# SCH_ECU_Standalone_V2_1.net
KiCad netlist of a schematic drawn in EasyEDA
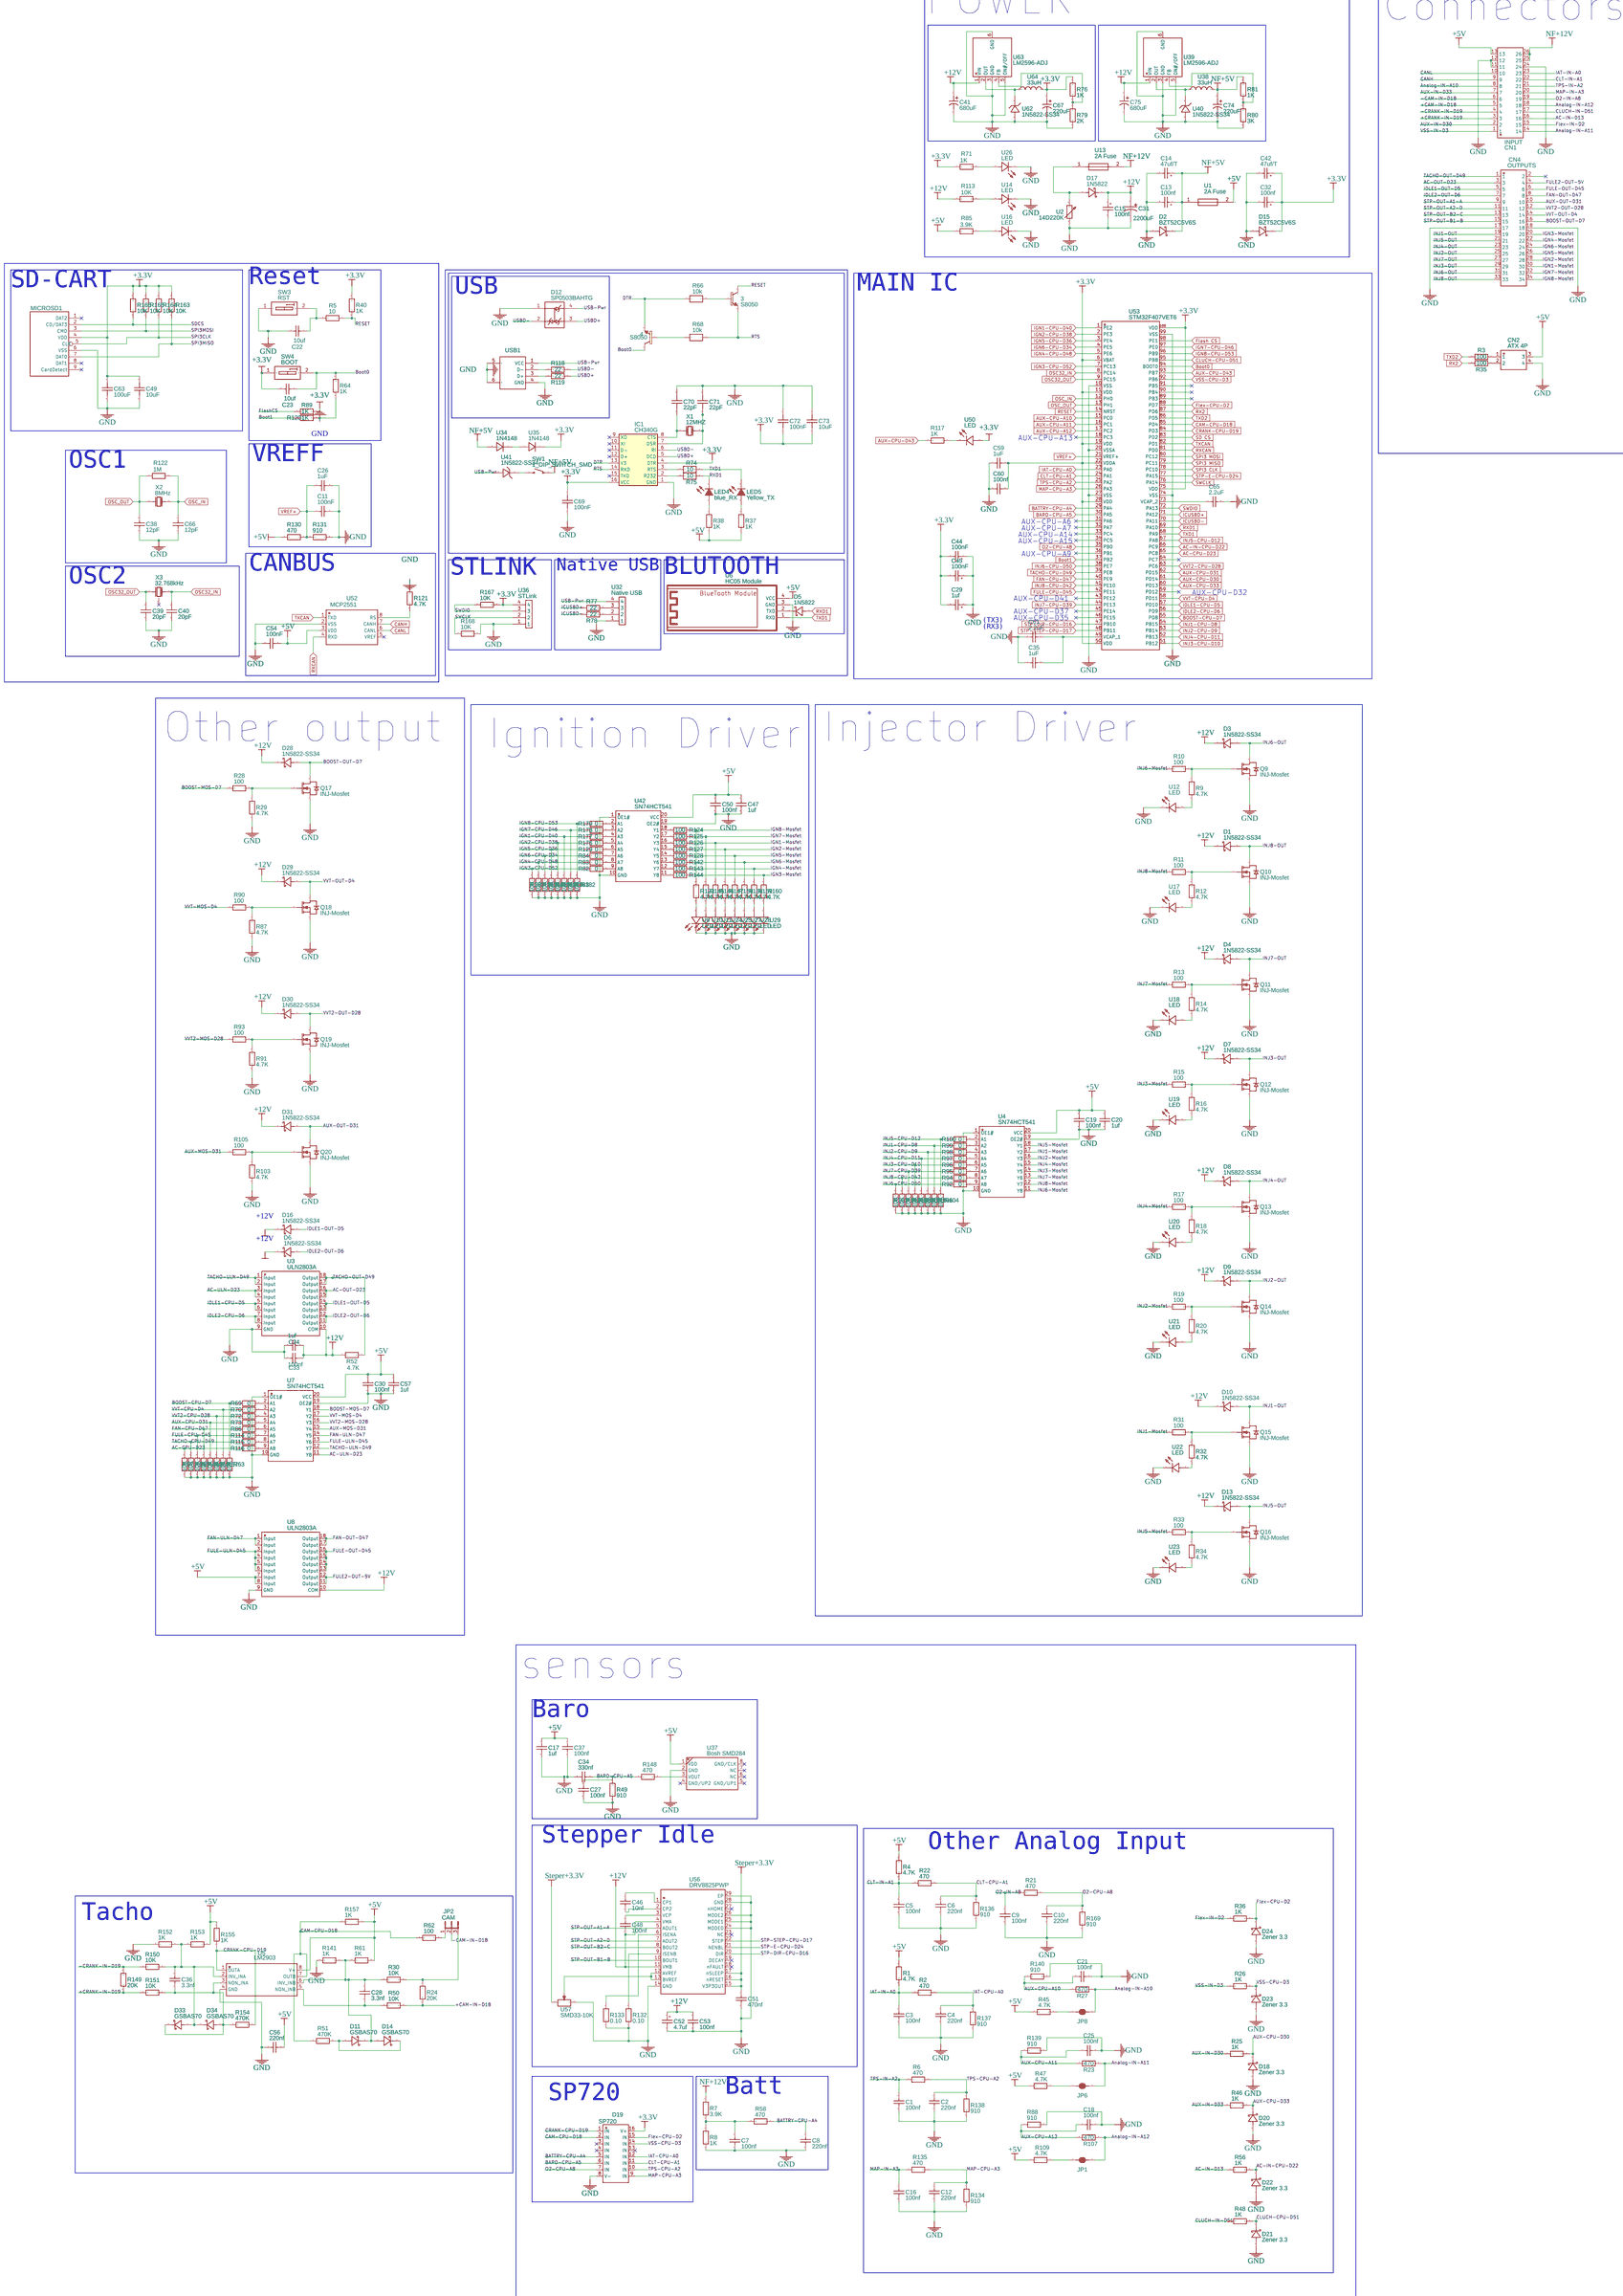
[diagram p0: schematic sheet]

(export (version "E")
  (design (tool "Eeschema 10.0.6"))
  (components
    (comp (ref "3") (value "S8050") (libsource (lib "") (part "J3Y_S8050_SMD_NPN_TRANSISTOR_1")))
    (comp (ref "4") (value "S8050") (libsource (lib "") (part "J3Y_S8050_SMD_NPN_TRANSISTOR")))
    (comp (ref "C1")
      (value "100nf")
      (fields (field (name "Manufacturer Part") "C0805X103K251T") (field (name "Manufacturer") "IHHEC(禾伸堂)"))
      (libsource (lib "") (part "C0805X103K251T"))
    )
    (comp (ref "C2")
      (value "220nf")
      (fields (field (name "Manufacturer Part") "C0805X103K251T") (field (name "Manufacturer") "IHHEC(禾伸堂)"))
      (libsource (lib "") (part "C0805X103K251T"))
    )
    (comp (ref "C3")
      (value "100nf")
      (fields (field (name "Manufacturer Part") "C0805X103K251T") (field (name "Manufacturer") "IHHEC(禾伸堂)"))
      (libsource (lib "") (part "C0805X103K251T"))
    )
    (comp (ref "C4")
      (value "220nf")
      (fields (field (name "Manufacturer Part") "C0805X103K251T") (field (name "Manufacturer") "IHHEC(禾伸堂)"))
      (libsource (lib "") (part "C0805X103K251T"))
    )
    (comp (ref "C5")
      (value "100nf")
      (fields (field (name "Manufacturer Part") "C0805X103K251T") (field (name "Manufacturer") "IHHEC(禾伸堂)"))
      (libsource (lib "") (part "C0805X103K251T"))
    )
    (comp (ref "C6")
      (value "220nf")
      (fields (field (name "Manufacturer Part") "C0805X103K251T") (field (name "Manufacturer") "IHHEC(禾伸堂)"))
      (libsource (lib "") (part "C0805X103K251T"))
    )
    (comp (ref "C7")
      (value "100nf")
      (fields (field (name "Manufacturer Part") "C0805X103K251T") (field (name "Manufacturer") "IHHEC(禾伸堂)"))
      (libsource (lib "") (part "C0805X103K251T"))
    )
    (comp (ref "C8")
      (value "220nf")
      (fields (field (name "Manufacturer Part") "C0805X103K251T") (field (name "Manufacturer") "IHHEC(禾伸堂)"))
      (libsource (lib "") (part "C0805X103K251T"))
    )
    (comp (ref "C9")
      (value "100nf")
      (fields (field (name "Manufacturer Part") "C0805X103K251T") (field (name "Manufacturer") "IHHEC(禾伸堂)"))
      (libsource (lib "") (part "C0805X103K251T"))
    )
    (comp (ref "C10")
      (value "220nf")
      (fields (field (name "Manufacturer Part") "C0805X103K251T") (field (name "Manufacturer") "IHHEC(禾伸堂)"))
      (libsource (lib "") (part "C0805X103K251T"))
    )
    (comp (ref "C11")
      (value "100nF")
      (fields (field (name "Manufacturer Part") "C0805X103K251T") (field (name "Manufacturer") "IHHEC(禾伸堂)"))
      (libsource (lib "") (part "C0805X103K251T_2"))
    )
    (comp (ref "C12")
      (value "220nf")
      (fields (field (name "Manufacturer Part") "C0805X103K251T") (field (name "Manufacturer") "IHHEC(禾伸堂)"))
      (libsource (lib "") (part "C0805X103K251T"))
    )
    (comp (ref "C13")
      (value "100nf")
      (fields (field (name "Manufacturer Part") "RMC25124.7K1%N") (field (name "Manufacturer") "Tyohm"))
      (libsource (lib "") (part "C SMD (2512 - 0805)"))
    )
    (comp (ref "C14")
      (value "47uf/T")
      (fields (field (name "Manufacturer Part") "RMC25124.7K1%N") (field (name "Manufacturer") "Tyohm"))
      (libsource (lib "") (part "C SMD (2512 - 0805)"))
    )
    (comp (ref "C15")
      (value "100nf")
      (fields (field (name "Manufacturer Part") "RMC25124.7K1%N") (field (name "Manufacturer") "Tyohm"))
      (libsource (lib "") (part "C SMD (2512 - 0805)_1"))
    )
    (comp (ref "C16")
      (value "100nf")
      (fields (field (name "Manufacturer Part") "C0805X103K251T") (field (name "Manufacturer") "IHHEC(禾伸堂)"))
      (libsource (lib "") (part "C0805X103K251T"))
    )
    (comp (ref "C17")
      (value "1uf")
      (fields (field (name "Manufacturer Part") "C0805X103K251T") (field (name "Manufacturer") "IHHEC(禾伸堂)"))
      (libsource (lib "") (part "C0805X103K251T"))
    )
    (comp (ref "C18")
      (value "100nf")
      (fields (field (name "Manufacturer Part") "C0805X103K251T") (field (name "Manufacturer") "IHHEC(禾伸堂)"))
      (libsource (lib "") (part "C0805X103K251T_2"))
    )
    (comp (ref "C19")
      (value "100nf")
      (fields (field (name "Manufacturer Part") "C0805X103K251T") (field (name "Manufacturer") "IHHEC(禾伸堂)"))
      (libsource (lib "") (part "C0805X103K251T"))
    )
    (comp (ref "C20")
      (value "1uf")
      (fields (field (name "Manufacturer Part") "C0805X103K251T") (field (name "Manufacturer") "IHHEC(禾伸堂)"))
      (libsource (lib "") (part "C0805X103K251T"))
    )
    (comp (ref "C21")
      (value "100nf")
      (fields (field (name "Manufacturer Part") "C0805X103K251T") (field (name "Manufacturer") "IHHEC(禾伸堂)"))
      (libsource (lib "") (part "C0805X103K251T_2"))
    )
    (comp (ref "C22")
      (value "10uf")
      (fields (field (name "Manufacturer Part") "C0805X103K251T") (field (name "Manufacturer") "IHHEC(禾伸堂)"))
      (libsource (lib "") (part "C0805X103K251T_1"))
    )
    (comp (ref "C23")
      (value "10uf")
      (fields (field (name "Manufacturer Part") "C0805X103K251T") (field (name "Manufacturer") "IHHEC(禾伸堂)"))
      (libsource (lib "") (part "C0805X103K251T_1"))
    )
    (comp (ref "C24")
      (value "1uf")
      (fields (field (name "Manufacturer Part") "C0805X103K251T") (field (name "Manufacturer") "IHHEC(禾伸堂)"))
      (libsource (lib "") (part "C0805X103K251T_1"))
    )
    (comp (ref "C25")
      (value "100nf")
      (fields (field (name "Manufacturer Part") "C0805X103K251T") (field (name "Manufacturer") "IHHEC(禾伸堂)"))
      (libsource (lib "") (part "C0805X103K251T_2"))
    )
    (comp (ref "C26")
      (value "1uF")
      (fields (field (name "Manufacturer Part") "C0805X103K251T") (field (name "Manufacturer") "IHHEC(禾伸堂)"))
      (libsource (lib "") (part "C0805X103K251T_2"))
    )
    (comp (ref "C27")
      (value "100nf")
      (fields (field (name "Manufacturer Part") "C0805X103K251T") (field (name "Manufacturer") "IHHEC(禾伸堂)"))
      (libsource (lib "") (part "C0805X103K251T"))
    )
    (comp (ref "C28")
      (value "3.3nf")
      (fields (field (name "Manufacturer Part") "C0805X103K251T") (field (name "Manufacturer") "IHHEC(禾伸堂)"))
      (libsource (lib "") (part "C0805X103K251T"))
    )
    (comp (ref "C29")
      (value "1uf")
      (fields (field (name "Manufacturer Part") "RMC25124.7K1%N") (field (name "Manufacturer") "Tyohm"))
      (libsource (lib "") (part "C SMD (2512 - 0805)"))
    )
    (comp (ref "C30")
      (value "100nf")
      (fields (field (name "Manufacturer Part") "C0805X103K251T") (field (name "Manufacturer") "IHHEC(禾伸堂)"))
      (libsource (lib "") (part "C0805X103K251T"))
    )
    (comp (ref "C31")
      (value "2200uF")
      (fields
        (field (name "Manufacturer Part") "25YXG2200MEFCG412.5X35")
        (field (name "Manufacturer") "rubycon(红宝石)")
      )
      (libsource (lib "") (part "25YXG2200MEFCG412.5X35"))
    )
    (comp (ref "C32")
      (value "100nf")
      (fields (field (name "Manufacturer Part") "RMC25124.7K1%N") (field (name "Manufacturer") "Tyohm"))
      (libsource (lib "") (part "C SMD (2512 - 0805)"))
    )
    (comp (ref "C33")
      (value "100nf")
      (fields (field (name "Manufacturer Part") "C0805X103K251T") (field (name "Manufacturer") "IHHEC(禾伸堂)"))
      (libsource (lib "") (part "C0805X103K251T_1"))
    )
    (comp (ref "C34")
      (value "330nf")
      (fields (field (name "Manufacturer Part") "C0805X103K251T") (field (name "Manufacturer") "IHHEC(禾伸堂)"))
      (libsource (lib "") (part "C0805X103K251T_1"))
    )
    (comp (ref "C35")
      (value "1uF")
      (fields (field (name "Manufacturer Part") "C0805X103K251T") (field (name "Manufacturer") "IHHEC(禾伸堂)"))
      (libsource (lib "") (part "C0805X103K251T_2"))
    )
    (comp (ref "C36")
      (value "3.3nf")
      (fields (field (name "Manufacturer Part") "C0805X103K251T") (field (name "Manufacturer") "IHHEC(禾伸堂)"))
      (libsource (lib "") (part "C0805X103K251T"))
    )
    (comp (ref "C37")
      (value "100nf")
      (fields (field (name "Manufacturer Part") "C0805X103K251T") (field (name "Manufacturer") "IHHEC(禾伸堂)"))
      (libsource (lib "") (part "C0805X103K251T"))
    )
    (comp (ref "C38")
      (value "12pF")
      (fields (field (name "Manufacturer Part") "C0805X103K251T") (field (name "Manufacturer") "IHHEC(禾伸堂)"))
      (libsource (lib "") (part "C0805X103K251T_3"))
    )
    (comp (ref "C39")
      (value "20pF")
      (fields (field (name "Manufacturer Part") "C0805X103K251T") (field (name "Manufacturer") "IHHEC(禾伸堂)"))
      (libsource (lib "") (part "C0805X103K251T_3"))
    )
    (comp (ref "C40")
      (value "20pF")
      (fields (field (name "Manufacturer Part") "C0805X103K251T") (field (name "Manufacturer") "IHHEC(禾伸堂)"))
      (libsource (lib "") (part "C0805X103K251T_3"))
    )
    (comp (ref "C41")
      (value "680uF")
      (fields
        (field (name "Manufacturer Part") "MVK16V100UF6.3*6")
        (field (name "Manufacturer") "SAMYOUNG(韩国三莹)")
      )
      (libsource (lib "") (part "CAP 6.3 &#126; 0.8 DIP 25v"))
    )
    (comp (ref "C42")
      (value "47uf/T")
      (fields (field (name "Manufacturer Part") "RMC25124.7K1%N") (field (name "Manufacturer") "Tyohm"))
      (libsource (lib "") (part "C SMD (2512 - 0805)"))
    )
    (comp (ref "C44")
      (value "100nF")
      (fields (field (name "Manufacturer Part") "RMC25124.7K1%N") (field (name "Manufacturer") "Tyohm"))
      (libsource (lib "") (part "C SMD (2512 - 0805)"))
    )
    (comp (ref "C45")
      (value "100nF")
      (fields (field (name "Manufacturer Part") "RMC25124.7K1%N") (field (name "Manufacturer") "Tyohm"))
      (libsource (lib "") (part "C SMD (2512 - 0805)"))
    )
    (comp (ref "C46")
      (value "10nf")
      (fields (field (name "Manufacturer Part") "C0805X103K251T") (field (name "Manufacturer") "IHHEC(禾伸堂)"))
      (libsource (lib "") (part "C0805X103K251T"))
    )
    (comp (ref "C47")
      (value "1uf")
      (fields (field (name "Manufacturer Part") "C0805X103K251T") (field (name "Manufacturer") "IHHEC(禾伸堂)"))
      (libsource (lib "") (part "C0805X103K251T"))
    )
    (comp (ref "C48")
      (value "100nf")
      (fields (field (name "Manufacturer Part") "C0805X103K251T") (field (name "Manufacturer") "IHHEC(禾伸堂)"))
      (libsource (lib "") (part "C0805X103K251T"))
    )
    (comp (ref "C49")
      (value "10uF")
      (fields
        (field (name "Manufacturer Part") "C0805C682KMRECAUTO7210")
        (field (name "Manufacturer") "KEMET(基美)")
      )
      (libsource (lib "") (part "C0805C682KMRECAUTO7210"))
    )
    (comp (ref "C50")
      (value "100nf")
      (fields (field (name "Manufacturer Part") "C0805X103K251T") (field (name "Manufacturer") "IHHEC(禾伸堂)"))
      (libsource (lib "") (part "C0805X103K251T"))
    )
    (comp (ref "C51")
      (value "470nf")
      (fields (field (name "Manufacturer Part") "C0805X103K251T") (field (name "Manufacturer") "IHHEC(禾伸堂)"))
      (libsource (lib "") (part "C0805X103K251T"))
    )
    (comp (ref "C52")
      (value "4.7uf")
      (fields (field (name "Manufacturer Part") "RMC25124.7K1%N") (field (name "Manufacturer") "Tyohm"))
      (libsource (lib "") (part "C SMD (2512 - 0805)_1"))
    )
    (comp (ref "C53")
      (value "100nf")
      (fields (field (name "Manufacturer Part") "C0805X103K251T") (field (name "Manufacturer") "IHHEC(禾伸堂)"))
      (libsource (lib "") (part "C0805X103K251T"))
    )
    (comp (ref "C54")
      (value "100nF")
      (fields (field (name "Manufacturer Part") "C0805X103K251T") (field (name "Manufacturer") "IHHEC(禾伸堂)"))
      (libsource (lib "") (part "C0805X103K251T_1"))
    )
    (comp (ref "C56")
      (value "220nf")
      (fields (field (name "Manufacturer Part") "C0805X103K251T") (field (name "Manufacturer") "IHHEC(禾伸堂)"))
      (libsource (lib "") (part "C0805X103K251T_2"))
    )
    (comp (ref "C57")
      (value "1uf")
      (fields (field (name "Manufacturer Part") "C0805X103K251T") (field (name "Manufacturer") "IHHEC(禾伸堂)"))
      (libsource (lib "") (part "C0805X103K251T"))
    )
    (comp (ref "C59")
      (value "1uF")
      (fields (field (name "Manufacturer Part") "C0805X103K251T") (field (name "Manufacturer") "IHHEC(禾伸堂)"))
      (libsource (lib "") (part "C0805X103K251T_2"))
    )
    (comp (ref "C60")
      (value "100nf")
      (fields (field (name "Manufacturer Part") "C0805X103K251T") (field (name "Manufacturer") "IHHEC(禾伸堂)"))
      (libsource (lib "") (part "C0805X103K251T_2"))
    )
    (comp (ref "C61")
      (value "2.2uF")
      (fields (field (name "Manufacturer Part") "C0805X103K251T") (field (name "Manufacturer") "IHHEC(禾伸堂)"))
      (libsource (lib "") (part "C0805X103K251T_2"))
    )
    (comp (ref "C63")
      (value "100uF")
      (fields
        (field (name "Manufacturer Part") "C0805C682KMRECAUTO7210")
        (field (name "Manufacturer") "KEMET(基美)")
      )
      (libsource (lib "") (part "C0805C682KMRECAUTO7210"))
    )
    (comp (ref "C65")
      (value "2.2uF")
      (fields (field (name "Manufacturer Part") "C0805X103K251T") (field (name "Manufacturer") "IHHEC(禾伸堂)"))
      (libsource (lib "") (part "C0805X103K251T_2"))
    )
    (comp (ref "C66")
      (value "12pF")
      (fields (field (name "Manufacturer Part") "C0805X103K251T") (field (name "Manufacturer") "IHHEC(禾伸堂)"))
      (libsource (lib "") (part "C0805X103K251T_3"))
    )
    (comp (ref "C67")
      (value "220uF")
      (fields
        (field (name "Manufacturer Part") "MVK16V100UF6.3*6")
        (field (name "Manufacturer") "SAMYOUNG(韩国三莹)")
      )
      (libsource (lib "") (part "CAP 6.3 &#126; 0.8 DIP 25v"))
    )
    (comp (ref "C69")
      (value "100nF")
      (fields
        (field (name "Manufacturer Part") "C0805C682KMRECAUTO7210")
        (field (name "Manufacturer") "KEMET(基美)")
      )
      (libsource (lib "") (part "C0805C682KMRECAUTO7210_1"))
    )
    (comp (ref "C70")
      (value "22pF")
      (fields
        (field (name "Manufacturer Part") "C0805C682KMRECAUTO7210")
        (field (name "Manufacturer") "KEMET(基美)")
      )
      (libsource (lib "") (part "C0805C682KMRECAUTO7210_1"))
    )
    (comp (ref "C71")
      (value "22pF")
      (fields
        (field (name "Manufacturer Part") "C0805C682KMRECAUTO7210")
        (field (name "Manufacturer") "KEMET(基美)")
      )
      (libsource (lib "") (part "C0805C682KMRECAUTO7210_1"))
    )
    (comp (ref "C72")
      (value "100nF")
      (fields
        (field (name "Manufacturer Part") "C0805C682KMRECAUTO7210")
        (field (name "Manufacturer") "KEMET(基美)")
      )
      (libsource (lib "") (part "C0805C682KMRECAUTO7210_1"))
    )
    (comp (ref "C73")
      (value "10uF")
      (fields
        (field (name "Manufacturer Part") "C0805C682KMRECAUTO7210")
        (field (name "Manufacturer") "KEMET(基美)")
      )
      (libsource (lib "") (part "C0805C682KMRECAUTO7210_1"))
    )
    (comp (ref "C74")
      (value "220uF")
      (fields
        (field (name "Manufacturer Part") "MVK16V100UF6.3*6")
        (field (name "Manufacturer") "SAMYOUNG(韩国三莹)")
      )
      (libsource (lib "") (part "CAP 6.3 &#126; 0.8 DIP 25v"))
    )
    (comp (ref "C75")
      (value "680uF")
      (fields
        (field (name "Manufacturer Part") "MVK16V100UF6.3*6")
        (field (name "Manufacturer") "SAMYOUNG(韩国三莹)")
      )
      (libsource (lib "") (part "CAP 6.3 &#126; 0.8 DIP 25v"))
    )
    (comp (ref "CN1")
      (value "INPUT")
      (fields (field (name "Manufacturer Part") "MX23A26NF1") (field (name "Manufacturer") "JAE(日本航空电子)"))
      (libsource (lib "") (part "MX23A26NF1"))
    )
    (comp (ref "CN2")
      (value "ATX 4P")
      (fields (field (name "Manufacturer Part") "C4201WR-2x2P") (field (name "Manufacturer") "CJT(长江连接器)"))
      (libsource (lib "") (part "C4201WR-2X2P"))
    )
    (comp (ref "CN4")
      (value "OUTPUTS")
      (fields (field (name "Manufacturer Part") "MX23A34NF1") (field (name "Manufacturer") "JAE(日本航空电子)"))
      (libsource (lib "") (part "MX23A34NF1"))
    )
    (comp (ref "D1")
      (value "1N5822-SS34")
      (fields (field (name "Manufacturer Part") "1N5819HW") (field (name "Manufacturer") "TECH PUBLIC(台舟)"))
      (libsource (lib "") (part "DIOD SOD-123_2"))
    )
    (comp (ref "D2")
      (value "BZT52C5V6S")
      (fields (field (name "Manufacturer Part") "1N5819HW") (field (name "Manufacturer") "TECH PUBLIC(台舟)"))
      (libsource (lib "") (part "DIOD SOD-123_1"))
    )
    (comp (ref "D3")
      (value "1N5822-SS34")
      (fields (field (name "Manufacturer Part") "1N5819HW") (field (name "Manufacturer") "TECH PUBLIC(台舟)"))
      (libsource (lib "") (part "DIOD SOD-123_2"))
    )
    (comp (ref "D4")
      (value "1N5822-SS34")
      (fields (field (name "Manufacturer Part") "1N5819HW") (field (name "Manufacturer") "TECH PUBLIC(台舟)"))
      (libsource (lib "") (part "DIOD SOD-123_2"))
    )
    (comp (ref "D5")
      (value "1N5822")
      (fields (field (name "Manufacturer Part") "1N5819HW") (field (name "Manufacturer") "TECH PUBLIC(台舟)"))
      (libsource (lib "") (part "DIOD SOD-123_2"))
    )
    (comp (ref "D6")
      (value "1N5822-SS34")
      (fields (field (name "Manufacturer Part") "1N5819HW") (field (name "Manufacturer") "TECH PUBLIC(台舟)"))
      (libsource (lib "") (part "DIOD SOD-123_2"))
    )
    (comp (ref "D7")
      (value "1N5822-SS34")
      (fields (field (name "Manufacturer Part") "1N5819HW") (field (name "Manufacturer") "TECH PUBLIC(台舟)"))
      (libsource (lib "") (part "DIOD SOD-123_2"))
    )
    (comp (ref "D8")
      (value "1N5822-SS34")
      (fields (field (name "Manufacturer Part") "1N5819HW") (field (name "Manufacturer") "TECH PUBLIC(台舟)"))
      (libsource (lib "") (part "DIOD SOD-123_2"))
    )
    (comp (ref "D9")
      (value "1N5822-SS34")
      (fields (field (name "Manufacturer Part") "1N5819HW") (field (name "Manufacturer") "TECH PUBLIC(台舟)"))
      (libsource (lib "") (part "DIOD SOD-123_2"))
    )
    (comp (ref "D10")
      (value "1N5822-SS34")
      (fields (field (name "Manufacturer Part") "1N5819HW") (field (name "Manufacturer") "TECH PUBLIC(台舟)"))
      (libsource (lib "") (part "DIOD SOD-123_2"))
    )
    (comp (ref "D11")
      (value "GSBAS70")
      (fields (field (name "Manufacturer Part") "GSBAS70WS") (field (name "Manufacturer") "GOOD-ARK(固锝)"))
      (libsource (lib "") (part "GSBAS70WS_1"))
    )
    (comp (ref "D12")
      (value "SP0503BAHTG")
      (fields (field (name "Manufacturer") "Littelfuse"))
      (libsource (lib "") (part "SP0503BAHTG"))
    )
    (comp (ref "D13")
      (value "1N5822-SS34")
      (fields (field (name "Manufacturer Part") "1N5819HW") (field (name "Manufacturer") "TECH PUBLIC(台舟)"))
      (libsource (lib "") (part "DIOD SOD-123_2"))
    )
    (comp (ref "D14")
      (value "GSBAS70")
      (fields (field (name "Manufacturer Part") "GSBAS70WS") (field (name "Manufacturer") "GOOD-ARK(固锝)"))
      (libsource (lib "") (part "GSBAS70WS_1"))
    )
    (comp (ref "D15")
      (value "BZT52C5V6S")
      (fields (field (name "Manufacturer Part") "1N5819HW") (field (name "Manufacturer") "TECH PUBLIC(台舟)"))
      (libsource (lib "") (part "DIOD SOD-123_1"))
    )
    (comp (ref "D16")
      (value "1N5822-SS34")
      (fields (field (name "Manufacturer Part") "1N5819HW") (field (name "Manufacturer") "TECH PUBLIC(台舟)"))
      (libsource (lib "") (part "DIOD SOD-123_2"))
    )
    (comp (ref "D17")
      (value "1N5822")
      (fields (field (name "Manufacturer Part") "1N5819HW") (field (name "Manufacturer") "TECH PUBLIC(台舟)"))
      (libsource (lib "") (part "DIOD SOD-123_1"))
    )
    (comp (ref "D18")
      (value "Zener 3.3")
      (fields (field (name "Manufacturer Part") "1N5819HW") (field (name "Manufacturer") "TECH PUBLIC(台舟)"))
      (libsource (lib "") (part "DIOD SOD-123"))
    )
    (comp (ref "D19")
      (value "SP720")
      (fields (field (name "Manufacturer Part") "SP720ABTG") (field (name "Manufacturer") "Littelfuse"))
      (libsource (lib "") (part "SP720ABTG"))
    )
    (comp (ref "D20")
      (value "Zener 3.3")
      (fields (field (name "Manufacturer Part") "1N5819HW") (field (name "Manufacturer") "TECH PUBLIC(台舟)"))
      (libsource (lib "") (part "DIOD SOD-123"))
    )
    (comp (ref "D21")
      (value "Zener 3.3")
      (fields (field (name "Manufacturer Part") "1N5819HW") (field (name "Manufacturer") "TECH PUBLIC(台舟)"))
      (libsource (lib "") (part "DIOD SOD-123"))
    )
    (comp (ref "D22")
      (value "Zener 3.3")
      (fields (field (name "Manufacturer Part") "1N5819HW") (field (name "Manufacturer") "TECH PUBLIC(台舟)"))
      (libsource (lib "") (part "DIOD SOD-123"))
    )
    (comp (ref "D23")
      (value "Zener 3.3")
      (fields (field (name "Manufacturer Part") "1N5819HW") (field (name "Manufacturer") "TECH PUBLIC(台舟)"))
      (libsource (lib "") (part "DIOD SOD-123"))
    )
    (comp (ref "D24")
      (value "Zener 3.3")
      (fields (field (name "Manufacturer Part") "1N5819HW") (field (name "Manufacturer") "TECH PUBLIC(台舟)"))
      (libsource (lib "") (part "DIOD SOD-123"))
    )
    (comp (ref "D28")
      (value "1N5822-SS34")
      (fields (field (name "Manufacturer Part") "1N5819HW") (field (name "Manufacturer") "TECH PUBLIC(台舟)"))
      (libsource (lib "") (part "DIOD SOD-123_2"))
    )
    (comp (ref "D29")
      (value "1N5822-SS34")
      (fields (field (name "Manufacturer Part") "1N5819HW") (field (name "Manufacturer") "TECH PUBLIC(台舟)"))
      (libsource (lib "") (part "DIOD SOD-123_2"))
    )
    (comp (ref "D30")
      (value "1N5822-SS34")
      (fields (field (name "Manufacturer Part") "1N5819HW") (field (name "Manufacturer") "TECH PUBLIC(台舟)"))
      (libsource (lib "") (part "DIOD SOD-123_2"))
    )
    (comp (ref "D31")
      (value "1N5822-SS34")
      (fields (field (name "Manufacturer Part") "1N5819HW") (field (name "Manufacturer") "TECH PUBLIC(台舟)"))
      (libsource (lib "") (part "DIOD SOD-123_2"))
    )
    (comp (ref "D33")
      (value "GSBAS70")
      (fields (field (name "Manufacturer Part") "GSBAS70WS") (field (name "Manufacturer") "GOOD-ARK(固锝)"))
      (libsource (lib "") (part "GSBAS70WS"))
    )
    (comp (ref "D34")
      (value "GSBAS70")
      (fields (field (name "Manufacturer Part") "GSBAS70WS") (field (name "Manufacturer") "GOOD-ARK(固锝)"))
      (libsource (lib "") (part "GSBAS70WS"))
    )
    (comp (ref "IC1")
      (value "CH340G")
      (fields (field (name "Manufacturer") "WCH"))
      (libsource (lib "") (part "Unknown_885_-515"))
    )
    (comp (ref "JP1") (value "Pull-Up") (libsource (lib "") (part "SOLDERJUMPER-OLDNO")))
    (comp (ref "JP2") (value "CAM") (libsource (lib "") (part "JUMPER 3X1 (PIN= 2.54) SMD")))
    (comp (ref "JP6") (value "Pull-Up") (libsource (lib "") (part "SOLDERJUMPER-OLDNO")))
    (comp (ref "JP8") (value "Pull-Up") (libsource (lib "") (part "SOLDERJUMPER-OLDNO")))
    (comp (ref "LED4")
      (value "blue_RX")
      (fields (field (name "Manufacturer Part") "0805-1-YGC/FID"))
      (libsource (lib "") (part "0805-1-YGC/FID"))
    )
    (comp (ref "LED5")
      (value "Yellow_TX")
      (fields (field (name "Manufacturer Part") "0805-1-YGC/FID"))
      (libsource (lib "") (part "0805-1-YGC/FID"))
    )
    (comp (ref "MICROSD1")
      (value "MicroSD_Slot")
      (fields (field (name "Manufacturer Part") "MicroSD Slot"))
      (libsource (lib "") (part "Unknown_-5_-740"))
    )
    (comp (ref "Q9")
      (value "INJ-Mosfet")
      (fields
        (field (name "Manufacturer Part") "PHD45N03LTA-VB")
        (field (name "Manufacturer") "VBsemi(微碧半导体)")
      )
      (libsource (lib "") (part "PHD45N03LTA"))
    )
    (comp (ref "Q10")
      (value "INJ-Mosfet")
      (fields
        (field (name "Manufacturer Part") "PHD45N03LTA-VB")
        (field (name "Manufacturer") "VBsemi(微碧半导体)")
      )
      (libsource (lib "") (part "PHD45N03LTA"))
    )
    (comp (ref "Q11")
      (value "INJ-Mosfet")
      (fields
        (field (name "Manufacturer Part") "PHD45N03LTA-VB")
        (field (name "Manufacturer") "VBsemi(微碧半导体)")
      )
      (libsource (lib "") (part "PHD45N03LTA"))
    )
    (comp (ref "Q12")
      (value "INJ-Mosfet")
      (fields
        (field (name "Manufacturer Part") "PHD45N03LTA-VB")
        (field (name "Manufacturer") "VBsemi(微碧半导体)")
      )
      (libsource (lib "") (part "PHD45N03LTA"))
    )
    (comp (ref "Q13")
      (value "INJ-Mosfet")
      (fields
        (field (name "Manufacturer Part") "PHD45N03LTA-VB")
        (field (name "Manufacturer") "VBsemi(微碧半导体)")
      )
      (libsource (lib "") (part "PHD45N03LTA"))
    )
    (comp (ref "Q14")
      (value "INJ-Mosfet")
      (fields
        (field (name "Manufacturer Part") "PHD45N03LTA-VB")
        (field (name "Manufacturer") "VBsemi(微碧半导体)")
      )
      (libsource (lib "") (part "PHD45N03LTA"))
    )
    (comp (ref "Q15")
      (value "INJ-Mosfet")
      (fields
        (field (name "Manufacturer Part") "PHD45N03LTA-VB")
        (field (name "Manufacturer") "VBsemi(微碧半导体)")
      )
      (libsource (lib "") (part "PHD45N03LTA"))
    )
    (comp (ref "Q16")
      (value "INJ-Mosfet")
      (fields
        (field (name "Manufacturer Part") "PHD45N03LTA-VB")
        (field (name "Manufacturer") "VBsemi(微碧半导体)")
      )
      (libsource (lib "") (part "PHD45N03LTA"))
    )
    (comp (ref "Q17")
      (value "INJ-Mosfet")
      (fields
        (field (name "Manufacturer Part") "PHD45N03LTA-VB")
        (field (name "Manufacturer") "VBsemi(微碧半导体)")
      )
      (libsource (lib "") (part "PHD45N03LTA"))
    )
    (comp (ref "Q18")
      (value "INJ-Mosfet")
      (fields
        (field (name "Manufacturer Part") "PHD45N03LTA-VB")
        (field (name "Manufacturer") "VBsemi(微碧半导体)")
      )
      (libsource (lib "") (part "PHD45N03LTA"))
    )
    (comp (ref "Q19")
      (value "INJ-Mosfet")
      (fields
        (field (name "Manufacturer Part") "PHD45N03LTA-VB")
        (field (name "Manufacturer") "VBsemi(微碧半导体)")
      )
      (libsource (lib "") (part "PHD45N03LTA"))
    )
    (comp (ref "Q20")
      (value "INJ-Mosfet")
      (fields
        (field (name "Manufacturer Part") "PHD45N03LTA-VB")
        (field (name "Manufacturer") "VBsemi(微碧半导体)")
      )
      (libsource (lib "") (part "PHD45N03LTA"))
    )
    (comp (ref "R1")
      (value "4.7K")
      (fields
        (field (name "Manufacturer Part") "AECR0805F9K10K9")
        (field (name "Manufacturer") "ResistorToday")
      )
      (libsource (lib "") (part "AECR0805F_3"))
    )
    (comp (ref "R2")
      (value "470")
      (fields
        (field (name "Manufacturer Part") "AECR0805F9K10K9")
        (field (name "Manufacturer") "ResistorToday")
      )
      (libsource (lib "") (part "AECR0805F"))
    )
    (comp (ref "R3")
      (value "100")
      (fields
        (field (name "Manufacturer Part") "AECR0805F9K10K9")
        (field (name "Manufacturer") "ResistorToday")
      )
      (libsource (lib "") (part "AECR0805F"))
    )
    (comp (ref "R4")
      (value "4.7K")
      (fields
        (field (name "Manufacturer Part") "AECR0805F9K10K9")
        (field (name "Manufacturer") "ResistorToday")
      )
      (libsource (lib "") (part "AECR0805F_3"))
    )
    (comp (ref "R5")
      (value "10")
      (fields
        (field (name "Manufacturer Part") "AECR0805F9K10K9")
        (field (name "Manufacturer") "ResistorToday")
      )
      (libsource (lib "") (part "AECR0805F"))
    )
    (comp (ref "R6")
      (value "470")
      (fields
        (field (name "Manufacturer Part") "AECR0805F9K10K9")
        (field (name "Manufacturer") "ResistorToday")
      )
      (libsource (lib "") (part "AECR0805F"))
    )
    (comp (ref "R7")
      (value "3.9K")
      (fields
        (field (name "Manufacturer Part") "AECR0805F9K10K9")
        (field (name "Manufacturer") "ResistorToday")
      )
      (libsource (lib "") (part "AECR0805F_1"))
    )
    (comp (ref "R8")
      (value "1K")
      (fields
        (field (name "Manufacturer Part") "AECR0805F9K10K9")
        (field (name "Manufacturer") "ResistorToday")
      )
      (libsource (lib "") (part "AECR0805F_1"))
    )
    (comp (ref "R9")
      (value "4.7K")
      (fields
        (field (name "Manufacturer Part") "AECR0805F9K10K9")
        (field (name "Manufacturer") "ResistorToday")
      )
      (libsource (lib "") (part "AECR0805F_1"))
    )
    (comp (ref "R10")
      (value "100")
      (fields
        (field (name "Manufacturer Part") "AECR0805F9K10K9")
        (field (name "Manufacturer") "ResistorToday")
      )
      (libsource (lib "") (part "AECR0805F"))
    )
    (comp (ref "R11")
      (value "100")
      (fields
        (field (name "Manufacturer Part") "AECR0805F9K10K9")
        (field (name "Manufacturer") "ResistorToday")
      )
      (libsource (lib "") (part "AECR0805F"))
    )
    (comp (ref "R12")
      (value "4.7K")
      (fields
        (field (name "Manufacturer Part") "AECR0805F9K10K9")
        (field (name "Manufacturer") "ResistorToday")
      )
      (libsource (lib "") (part "AECR0805F_1"))
    )
    (comp (ref "R13")
      (value "100")
      (fields
        (field (name "Manufacturer Part") "AECR0805F9K10K9")
        (field (name "Manufacturer") "ResistorToday")
      )
      (libsource (lib "") (part "AECR0805F"))
    )
    (comp (ref "R14")
      (value "4.7K")
      (fields
        (field (name "Manufacturer Part") "AECR0805F9K10K9")
        (field (name "Manufacturer") "ResistorToday")
      )
      (libsource (lib "") (part "AECR0805F_1"))
    )
    (comp (ref "R15")
      (value "100")
      (fields
        (field (name "Manufacturer Part") "AECR0805F9K10K9")
        (field (name "Manufacturer") "ResistorToday")
      )
      (libsource (lib "") (part "AECR0805F"))
    )
    (comp (ref "R16")
      (value "4.7K")
      (fields
        (field (name "Manufacturer Part") "AECR0805F9K10K9")
        (field (name "Manufacturer") "ResistorToday")
      )
      (libsource (lib "") (part "AECR0805F_1"))
    )
    (comp (ref "R17")
      (value "100")
      (fields
        (field (name "Manufacturer Part") "AECR0805F9K10K9")
        (field (name "Manufacturer") "ResistorToday")
      )
      (libsource (lib "") (part "AECR0805F"))
    )
    (comp (ref "R18")
      (value "4.7K")
      (fields
        (field (name "Manufacturer Part") "AECR0805F9K10K9")
        (field (name "Manufacturer") "ResistorToday")
      )
      (libsource (lib "") (part "AECR0805F_1"))
    )
    (comp (ref "R19")
      (value "100")
      (fields
        (field (name "Manufacturer Part") "AECR0805F9K10K9")
        (field (name "Manufacturer") "ResistorToday")
      )
      (libsource (lib "") (part "AECR0805F"))
    )
    (comp (ref "R20")
      (value "4.7K")
      (fields
        (field (name "Manufacturer Part") "AECR0805F9K10K9")
        (field (name "Manufacturer") "ResistorToday")
      )
      (libsource (lib "") (part "AECR0805F_1"))
    )
    (comp (ref "R21")
      (value "470")
      (fields
        (field (name "Manufacturer Part") "AECR0805F9K10K9")
        (field (name "Manufacturer") "ResistorToday")
      )
      (libsource (lib "") (part "AECR0805F"))
    )
    (comp (ref "R22")
      (value "470")
      (fields
        (field (name "Manufacturer Part") "AECR0805F9K10K9")
        (field (name "Manufacturer") "ResistorToday")
      )
      (libsource (lib "") (part "AECR0805F"))
    )
    (comp (ref "R23")
      (value "470")
      (fields
        (field (name "Manufacturer Part") "AECR0805F9K10K9")
        (field (name "Manufacturer") "ResistorToday")
      )
      (libsource (lib "") (part "AECR0805F"))
    )
    (comp (ref "R24")
      (value "20K")
      (fields
        (field (name "Manufacturer Part") "AECR0805F9K10K9")
        (field (name "Manufacturer") "ResistorToday")
      )
      (libsource (lib "") (part "AECR0805F_3"))
    )
    (comp (ref "R25")
      (value "1K")
      (fields
        (field (name "Manufacturer Part") "AECR0805F9K10K9")
        (field (name "Manufacturer") "ResistorToday")
      )
      (libsource (lib "") (part "AECR0805F_2"))
    )
    (comp (ref "R26")
      (value "1K")
      (fields
        (field (name "Manufacturer Part") "AECR0805F9K10K9")
        (field (name "Manufacturer") "ResistorToday")
      )
      (libsource (lib "") (part "AECR0805F_2"))
    )
    (comp (ref "R27")
      (value "470")
      (fields
        (field (name "Manufacturer Part") "AECR0805F9K10K9")
        (field (name "Manufacturer") "ResistorToday")
      )
      (libsource (lib "") (part "AECR0805F"))
    )
    (comp (ref "R28")
      (value "100")
      (fields
        (field (name "Manufacturer Part") "AECR0805F9K10K9")
        (field (name "Manufacturer") "ResistorToday")
      )
      (libsource (lib "") (part "AECR0805F"))
    )
    (comp (ref "R29")
      (value "4.7K")
      (fields
        (field (name "Manufacturer Part") "AECR0805F9K10K9")
        (field (name "Manufacturer") "ResistorToday")
      )
      (libsource (lib "") (part "AECR0805F_3"))
    )
    (comp (ref "R30")
      (value "10K")
      (fields
        (field (name "Manufacturer Part") "AECR0805F9K10K9")
        (field (name "Manufacturer") "ResistorToday")
      )
      (libsource (lib "") (part "AECR0805F_2"))
    )
    (comp (ref "R31")
      (value "100")
      (fields
        (field (name "Manufacturer Part") "AECR0805F9K10K9")
        (field (name "Manufacturer") "ResistorToday")
      )
      (libsource (lib "") (part "AECR0805F"))
    )
    (comp (ref "R32")
      (value "4.7K")
      (fields
        (field (name "Manufacturer Part") "AECR0805F9K10K9")
        (field (name "Manufacturer") "ResistorToday")
      )
      (libsource (lib "") (part "AECR0805F_1"))
    )
    (comp (ref "R33")
      (value "100")
      (fields
        (field (name "Manufacturer Part") "AECR0805F9K10K9")
        (field (name "Manufacturer") "ResistorToday")
      )
      (libsource (lib "") (part "AECR0805F"))
    )
    (comp (ref "R34")
      (value "4.7K")
      (fields
        (field (name "Manufacturer Part") "AECR0805F9K10K9")
        (field (name "Manufacturer") "ResistorToday")
      )
      (libsource (lib "") (part "AECR0805F_1"))
    )
    (comp (ref "R35")
      (value "100")
      (fields
        (field (name "Manufacturer Part") "AECR0805F9K10K9")
        (field (name "Manufacturer") "ResistorToday")
      )
      (libsource (lib "") (part "AECR0805F"))
    )
    (comp (ref "R36")
      (value "1K")
      (fields
        (field (name "Manufacturer Part") "AECR0805F9K10K9")
        (field (name "Manufacturer") "ResistorToday")
      )
      (libsource (lib "") (part "AECR0805F_2"))
    )
    (comp (ref "R37")
      (value "1K")
      (fields (field (name "Manufacturer Part") "RC0805FR-072K74L") (field (name "Manufacturer") "YAGEO"))
      (libsource (lib "") (part "RC0805FR-072K74L"))
    )
    (comp (ref "R38")
      (value "1K")
      (fields (field (name "Manufacturer Part") "RC0805FR-072K74L") (field (name "Manufacturer") "YAGEO"))
      (libsource (lib "") (part "RC0805FR-072K74L"))
    )
    (comp (ref "R40")
      (value "1K")
      (fields
        (field (name "Manufacturer Part") "AECR0805F9K10K9")
        (field (name "Manufacturer") "ResistorToday")
      )
      (libsource (lib "") (part "AECR0805F_1"))
    )
    (comp (ref "R41")
      (value "10K")
      (fields
        (field (name "Manufacturer Part") "AECR0805F9K10K9")
        (field (name "Manufacturer") "ResistorToday")
      )
      (libsource (lib "") (part "AECR0805F_1"))
    )
    (comp (ref "R42")
      (value "10K")
      (fields
        (field (name "Manufacturer Part") "AECR0805F9K10K9")
        (field (name "Manufacturer") "ResistorToday")
      )
      (libsource (lib "") (part "AECR0805F_1"))
    )
    (comp (ref "R43")
      (value "10K")
      (fields
        (field (name "Manufacturer Part") "AECR0805F9K10K9")
        (field (name "Manufacturer") "ResistorToday")
      )
      (libsource (lib "") (part "AECR0805F_1"))
    )
    (comp (ref "R45")
      (value "4.7K")
      (fields
        (field (name "Manufacturer Part") "AECR0805F9K10K9")
        (field (name "Manufacturer") "ResistorToday")
      )
      (libsource (lib "") (part "AECR0805F_2"))
    )
    (comp (ref "R46")
      (value "1K")
      (fields
        (field (name "Manufacturer Part") "AECR0805F9K10K9")
        (field (name "Manufacturer") "ResistorToday")
      )
      (libsource (lib "") (part "AECR0805F_2"))
    )
    (comp (ref "R47")
      (value "4.7K")
      (fields
        (field (name "Manufacturer Part") "AECR0805F9K10K9")
        (field (name "Manufacturer") "ResistorToday")
      )
      (libsource (lib "") (part "AECR0805F_2"))
    )
    (comp (ref "R48")
      (value "1K")
      (fields
        (field (name "Manufacturer Part") "AECR0805F9K10K9")
        (field (name "Manufacturer") "ResistorToday")
      )
      (libsource (lib "") (part "AECR0805F_2"))
    )
    (comp (ref "R49")
      (value "910")
      (fields
        (field (name "Manufacturer Part") "AECR0805F9K10K9")
        (field (name "Manufacturer") "ResistorToday")
      )
      (libsource (lib "") (part "AECR0805F_3"))
    )
    (comp (ref "R50")
      (value "10K")
      (fields
        (field (name "Manufacturer Part") "AECR0805F9K10K9")
        (field (name "Manufacturer") "ResistorToday")
      )
      (libsource (lib "") (part "AECR0805F_2"))
    )
    (comp (ref "R51")
      (value "470K")
      (fields
        (field (name "Manufacturer Part") "AECR0805F9K10K9")
        (field (name "Manufacturer") "ResistorToday")
      )
      (libsource (lib "") (part "AECR0805F_2"))
    )
    (comp (ref "R52")
      (value "4.7K")
      (fields
        (field (name "Manufacturer Part") "AECR0805F9K10K9")
        (field (name "Manufacturer") "ResistorToday")
      )
      (libsource (lib "") (part "AECR0805F_2"))
    )
    (comp (ref "R54")
      (value "10K")
      (fields
        (field (name "Manufacturer Part") "AECR0805F9K10K9")
        (field (name "Manufacturer") "ResistorToday")
      )
      (libsource (lib "") (part "AECR0805F_1"))
    )
    (comp (ref "R56")
      (value "1K")
      (fields
        (field (name "Manufacturer Part") "AECR0805F9K10K9")
        (field (name "Manufacturer") "ResistorToday")
      )
      (libsource (lib "") (part "AECR0805F_2"))
    )
    (comp (ref "R57")
      (value "10K")
      (fields
        (field (name "Manufacturer Part") "AECR0805F9K10K9")
        (field (name "Manufacturer") "ResistorToday")
      )
      (libsource (lib "") (part "AECR0805F_1"))
    )
    (comp (ref "R58")
      (value "470")
      (fields
        (field (name "Manufacturer Part") "AECR0805F9K10K9")
        (field (name "Manufacturer") "ResistorToday")
      )
      (libsource (lib "") (part "AECR0805F"))
    )
    (comp (ref "R61")
      (value "1K")
      (fields
        (field (name "Manufacturer Part") "AECR0805F9K10K9")
        (field (name "Manufacturer") "ResistorToday")
      )
      (libsource (lib "") (part "AECR0805F"))
    )
    (comp (ref "R62")
      (value "100")
      (fields
        (field (name "Manufacturer Part") "AECR0805F9K10K9")
        (field (name "Manufacturer") "ResistorToday")
      )
      (libsource (lib "") (part "AECR0805F_2"))
    )
    (comp (ref "R63")
      (value "10K")
      (fields
        (field (name "Manufacturer Part") "AECR0805F9K10K9")
        (field (name "Manufacturer") "ResistorToday")
      )
      (libsource (lib "") (part "AECR0805F_1"))
    )
    (comp (ref "R64")
      (value "1K")
      (fields
        (field (name "Manufacturer Part") "AECR0805F9K10K9")
        (field (name "Manufacturer") "ResistorToday")
      )
      (libsource (lib "") (part "AECR0805F_1"))
    )
    (comp (ref "R65")
      (value "10K")
      (fields
        (field (name "Manufacturer Part") "AECR0805F9K10K9")
        (field (name "Manufacturer") "ResistorToday")
      )
      (libsource (lib "") (part "AECR0805F_1"))
    )
    (comp (ref "R66") (value "10k") (libsource (lib "") (part "Res_0805(1/8W)_EU")))
    (comp (ref "R67")
      (value "10K")
      (fields
        (field (name "Manufacturer Part") "AECR0805F9K10K9")
        (field (name "Manufacturer") "ResistorToday")
      )
      (libsource (lib "") (part "AECR0805F_1"))
    )
    (comp (ref "R68") (value "10k") (libsource (lib "") (part "Res_0805(1/8W)_EU")))
    (comp (ref "R69")
      (value "0")
      (fields
        (field (name "Manufacturer Part") "AECR0805F9K10K9")
        (field (name "Manufacturer") "ResistorToday")
      )
      (libsource (lib "") (part "AECR0805F_2"))
    )
    (comp (ref "R70")
      (value "0")
      (fields
        (field (name "Manufacturer Part") "AECR0805F9K10K9")
        (field (name "Manufacturer") "ResistorToday")
      )
      (libsource (lib "") (part "AECR0805F_2"))
    )
    (comp (ref "R71")
      (value "1K")
      (fields
        (field (name "Manufacturer Part") "AECR0805F9K10K9")
        (field (name "Manufacturer") "ResistorToday")
      )
      (libsource (lib "") (part "AECR0805F_2"))
    )
    (comp (ref "R72")
      (value "0")
      (fields
        (field (name "Manufacturer Part") "AECR0805F9K10K9")
        (field (name "Manufacturer") "ResistorToday")
      )
      (libsource (lib "") (part "AECR0805F_2"))
    )
    (comp (ref "R73")
      (value "0")
      (fields
        (field (name "Manufacturer Part") "AECR0805F9K10K9")
        (field (name "Manufacturer") "ResistorToday")
      )
      (libsource (lib "") (part "AECR0805F_2"))
    )
    (comp (ref "R74") (value "10") (libsource (lib "") (part "Res_0805(1/8W)_EU")))
    (comp (ref "R75") (value "10") (libsource (lib "") (part "Res_0805(1/8W)_EU")))
    (comp (ref "R76")
      (value "1K")
      (fields
        (field (name "Manufacturer Part") "AECR0805F9K10K9")
        (field (name "Manufacturer") "ResistorToday")
      )
      (libsource (lib "") (part "AECR0805F_1"))
    )
    (comp (ref "R77")
      (value "22")
      (fields
        (field (name "Manufacturer Part") "AECR0805F9K10K9")
        (field (name "Manufacturer") "ResistorToday")
      )
      (libsource (lib "") (part "AECR0805F_2"))
    )
    (comp (ref "R78")
      (value "22")
      (fields
        (field (name "Manufacturer Part") "AECR0805F9K10K9")
        (field (name "Manufacturer") "ResistorToday")
      )
      (libsource (lib "") (part "AECR0805F_2"))
    )
    (comp (ref "R79")
      (value "2K")
      (fields
        (field (name "Manufacturer Part") "AECR0805F9K10K9")
        (field (name "Manufacturer") "ResistorToday")
      )
      (libsource (lib "") (part "AECR0805F_1"))
    )
    (comp (ref "R80")
      (value "3K")
      (fields
        (field (name "Manufacturer Part") "AECR0805F9K10K9")
        (field (name "Manufacturer") "ResistorToday")
      )
      (libsource (lib "") (part "AECR0805F_1"))
    )
    (comp (ref "R81")
      (value "1K")
      (fields
        (field (name "Manufacturer Part") "AECR0805F9K10K9")
        (field (name "Manufacturer") "ResistorToday")
      )
      (libsource (lib "") (part "AECR0805F_1"))
    )
    (comp (ref "R82")
      (value "0")
      (fields
        (field (name "Manufacturer Part") "AECR0805F9K10K9")
        (field (name "Manufacturer") "ResistorToday")
      )
      (libsource (lib "") (part "AECR0805F_2"))
    )
    (comp (ref "R83")
      (value "0")
      (fields
        (field (name "Manufacturer Part") "AECR0805F9K10K9")
        (field (name "Manufacturer") "ResistorToday")
      )
      (libsource (lib "") (part "AECR0805F_2"))
    )
    (comp (ref "R84")
      (value "0")
      (fields
        (field (name "Manufacturer Part") "AECR0805F9K10K9")
        (field (name "Manufacturer") "ResistorToday")
      )
      (libsource (lib "") (part "AECR0805F_2"))
    )
    (comp (ref "R85")
      (value "3.9K")
      (fields
        (field (name "Manufacturer Part") "AECR0805F9K10K9")
        (field (name "Manufacturer") "ResistorToday")
      )
      (libsource (lib "") (part "AECR0805F_2"))
    )
    (comp (ref "R86")
      (value "0")
      (fields
        (field (name "Manufacturer Part") "AECR0805F9K10K9")
        (field (name "Manufacturer") "ResistorToday")
      )
      (libsource (lib "") (part "AECR0805F_2"))
    )
    (comp (ref "R87")
      (value "4.7K")
      (fields
        (field (name "Manufacturer Part") "AECR0805F9K10K9")
        (field (name "Manufacturer") "ResistorToday")
      )
      (libsource (lib "") (part "AECR0805F_3"))
    )
    (comp (ref "R88")
      (value "910")
      (fields
        (field (name "Manufacturer Part") "AECR0805F9K10K9")
        (field (name "Manufacturer") "ResistorToday")
      )
      (libsource (lib "") (part "AECR0805F_2"))
    )
    (comp (ref "R89")
      (value "1K")
      (fields
        (field (name "Manufacturer Part") "AECR0805F9K10K9")
        (field (name "Manufacturer") "ResistorToday")
      )
      (libsource (lib "") (part "AECR0805F"))
    )
    (comp (ref "R90")
      (value "100")
      (fields
        (field (name "Manufacturer Part") "AECR0805F9K10K9")
        (field (name "Manufacturer") "ResistorToday")
      )
      (libsource (lib "") (part "AECR0805F"))
    )
    (comp (ref "R91")
      (value "4.7K")
      (fields
        (field (name "Manufacturer Part") "AECR0805F9K10K9")
        (field (name "Manufacturer") "ResistorToday")
      )
      (libsource (lib "") (part "AECR0805F_3"))
    )
    (comp (ref "R92")
      (value "0")
      (fields
        (field (name "Manufacturer Part") "AECR0805F9K10K9")
        (field (name "Manufacturer") "ResistorToday")
      )
      (libsource (lib "") (part "AECR0805F_2"))
    )
    (comp (ref "R93")
      (value "100")
      (fields
        (field (name "Manufacturer Part") "AECR0805F9K10K9")
        (field (name "Manufacturer") "ResistorToday")
      )
      (libsource (lib "") (part "AECR0805F"))
    )
    (comp (ref "R94")
      (value "0")
      (fields
        (field (name "Manufacturer Part") "AECR0805F9K10K9")
        (field (name "Manufacturer") "ResistorToday")
      )
      (libsource (lib "") (part "AECR0805F_2"))
    )
    (comp (ref "R95")
      (value "0")
      (fields
        (field (name "Manufacturer Part") "AECR0805F9K10K9")
        (field (name "Manufacturer") "ResistorToday")
      )
      (libsource (lib "") (part "AECR0805F_2"))
    )
    (comp (ref "R96")
      (value "0")
      (fields
        (field (name "Manufacturer Part") "AECR0805F9K10K9")
        (field (name "Manufacturer") "ResistorToday")
      )
      (libsource (lib "") (part "AECR0805F_2"))
    )
    (comp (ref "R97")
      (value "0")
      (fields
        (field (name "Manufacturer Part") "AECR0805F9K10K9")
        (field (name "Manufacturer") "ResistorToday")
      )
      (libsource (lib "") (part "AECR0805F_2"))
    )
    (comp (ref "R98")
      (value "0")
      (fields
        (field (name "Manufacturer Part") "AECR0805F9K10K9")
        (field (name "Manufacturer") "ResistorToday")
      )
      (libsource (lib "") (part "AECR0805F_2"))
    )
    (comp (ref "R99")
      (value "0")
      (fields
        (field (name "Manufacturer Part") "AECR0805F9K10K9")
        (field (name "Manufacturer") "ResistorToday")
      )
      (libsource (lib "") (part "AECR0805F_2"))
    )
    (comp (ref "R100")
      (value "0")
      (fields
        (field (name "Manufacturer Part") "AECR0805F9K10K9")
        (field (name "Manufacturer") "ResistorToday")
      )
      (libsource (lib "") (part "AECR0805F_2"))
    )
    (comp (ref "R101")
      (value "10K")
      (fields
        (field (name "Manufacturer Part") "AECR0805F9K10K9")
        (field (name "Manufacturer") "ResistorToday")
      )
      (libsource (lib "") (part "AECR0805F_1"))
    )
    (comp (ref "R102")
      (value "10K")
      (fields
        (field (name "Manufacturer Part") "AECR0805F9K10K9")
        (field (name "Manufacturer") "ResistorToday")
      )
      (libsource (lib "") (part "AECR0805F_1"))
    )
    (comp (ref "R103")
      (value "4.7K")
      (fields
        (field (name "Manufacturer Part") "AECR0805F9K10K9")
        (field (name "Manufacturer") "ResistorToday")
      )
      (libsource (lib "") (part "AECR0805F_3"))
    )
    (comp (ref "R104")
      (value "10K")
      (fields
        (field (name "Manufacturer Part") "AECR0805F9K10K9")
        (field (name "Manufacturer") "ResistorToday")
      )
      (libsource (lib "") (part "AECR0805F_1"))
    )
    (comp (ref "R105")
      (value "100")
      (fields
        (field (name "Manufacturer Part") "AECR0805F9K10K9")
        (field (name "Manufacturer") "ResistorToday")
      )
      (libsource (lib "") (part "AECR0805F"))
    )
    (comp (ref "R106")
      (value "10K")
      (fields
        (field (name "Manufacturer Part") "AECR0805F9K10K9")
        (field (name "Manufacturer") "ResistorToday")
      )
      (libsource (lib "") (part "AECR0805F_1"))
    )
    (comp (ref "R107")
      (value "470")
      (fields
        (field (name "Manufacturer Part") "AECR0805F9K10K9")
        (field (name "Manufacturer") "ResistorToday")
      )
      (libsource (lib "") (part "AECR0805F"))
    )
    (comp (ref "R108")
      (value "10K")
      (fields
        (field (name "Manufacturer Part") "AECR0805F9K10K9")
        (field (name "Manufacturer") "ResistorToday")
      )
      (libsource (lib "") (part "AECR0805F_1"))
    )
    (comp (ref "R109")
      (value "4.7K")
      (fields
        (field (name "Manufacturer Part") "AECR0805F9K10K9")
        (field (name "Manufacturer") "ResistorToday")
      )
      (libsource (lib "") (part "AECR0805F_2"))
    )
    (comp (ref "R110")
      (value "10K")
      (fields
        (field (name "Manufacturer Part") "AECR0805F9K10K9")
        (field (name "Manufacturer") "ResistorToday")
      )
      (libsource (lib "") (part "AECR0805F_1"))
    )
    (comp (ref "R111")
      (value "10K")
      (fields
        (field (name "Manufacturer Part") "AECR0805F9K10K9")
        (field (name "Manufacturer") "ResistorToday")
      )
      (libsource (lib "") (part "AECR0805F_1"))
    )
    (comp (ref "R112")
      (value "10K")
      (fields
        (field (name "Manufacturer Part") "AECR0805F9K10K9")
        (field (name "Manufacturer") "ResistorToday")
      )
      (libsource (lib "") (part "AECR0805F_1"))
    )
    (comp (ref "R113")
      (value "10K")
      (fields
        (field (name "Manufacturer Part") "AECR0805F9K10K9")
        (field (name "Manufacturer") "ResistorToday")
      )
      (libsource (lib "") (part "AECR0805F_2"))
    )
    (comp (ref "R114")
      (value "0")
      (fields
        (field (name "Manufacturer Part") "AECR0805F9K10K9")
        (field (name "Manufacturer") "ResistorToday")
      )
      (libsource (lib "") (part "AECR0805F_2"))
    )
    (comp (ref "R115")
      (value "0")
      (fields
        (field (name "Manufacturer Part") "AECR0805F9K10K9")
        (field (name "Manufacturer") "ResistorToday")
      )
      (libsource (lib "") (part "AECR0805F_2"))
    )
    (comp (ref "R116")
      (value "0")
      (fields
        (field (name "Manufacturer Part") "AECR0805F9K10K9")
        (field (name "Manufacturer") "ResistorToday")
      )
      (libsource (lib "") (part "AECR0805F_2"))
    )
    (comp (ref "R117")
      (value "1K")
      (fields
        (field (name "Manufacturer Part") "AECR0805F9K10K9")
        (field (name "Manufacturer") "ResistorToday")
      )
      (libsource (lib "") (part "AECR0805F"))
    )
    (comp (ref "R118")
      (value "22")
      (fields
        (field (name "Manufacturer Part") "AECR0805F9K10K9")
        (field (name "Manufacturer") "ResistorToday")
      )
      (libsource (lib "") (part "AECR0805F_2"))
    )
    (comp (ref "R119")
      (value "22")
      (fields
        (field (name "Manufacturer Part") "AECR0805F9K10K9")
        (field (name "Manufacturer") "ResistorToday")
      )
      (libsource (lib "") (part "AECR0805F_2"))
    )
    (comp (ref "R120")
      (value "1K")
      (fields
        (field (name "Manufacturer Part") "AECR0805F9K10K9")
        (field (name "Manufacturer") "ResistorToday")
      )
      (libsource (lib "") (part "AECR0805F"))
    )
    (comp (ref "R121")
      (value "4.7K")
      (fields
        (field (name "Manufacturer Part") "AECR0805F9K10K9")
        (field (name "Manufacturer") "ResistorToday")
      )
      (libsource (lib "") (part "AECR0805F_1"))
    )
    (comp (ref "R122")
      (value "1M")
      (fields
        (field (name "Manufacturer Part") "AECR0805F9K10K9")
        (field (name "Manufacturer") "ResistorToday")
      )
      (libsource (lib "") (part "AECR0805F_2"))
    )
    (comp (ref "R123")
      (value "4.7K")
      (fields
        (field (name "Manufacturer Part") "AECR0805F9K10K9")
        (field (name "Manufacturer") "ResistorToday")
      )
      (libsource (lib "") (part "AECR0805F_1"))
    )
    (comp (ref "R124")
      (value "100")
      (fields
        (field (name "Manufacturer Part") "AECR0805F9K10K9")
        (field (name "Manufacturer") "ResistorToday")
      )
      (libsource (lib "") (part "AECR0805F"))
    )
    (comp (ref "R125")
      (value "100")
      (fields
        (field (name "Manufacturer Part") "AECR0805F9K10K9")
        (field (name "Manufacturer") "ResistorToday")
      )
      (libsource (lib "") (part "AECR0805F"))
    )
    (comp (ref "R126")
      (value "100")
      (fields
        (field (name "Manufacturer Part") "AECR0805F9K10K9")
        (field (name "Manufacturer") "ResistorToday")
      )
      (libsource (lib "") (part "AECR0805F"))
    )
    (comp (ref "R127")
      (value "100")
      (fields
        (field (name "Manufacturer Part") "AECR0805F9K10K9")
        (field (name "Manufacturer") "ResistorToday")
      )
      (libsource (lib "") (part "AECR0805F"))
    )
    (comp (ref "R128")
      (value "100")
      (fields
        (field (name "Manufacturer Part") "AECR0805F9K10K9")
        (field (name "Manufacturer") "ResistorToday")
      )
      (libsource (lib "") (part "AECR0805F"))
    )
    (comp (ref "R129")
      (value "0")
      (fields
        (field (name "Manufacturer Part") "AECR0805F9K10K9")
        (field (name "Manufacturer") "ResistorToday")
      )
      (libsource (lib "") (part "AECR0805F_2"))
    )
    (comp (ref "R130")
      (value "470")
      (fields
        (field (name "Manufacturer Part") "AECR0805F9K10K9")
        (field (name "Manufacturer") "ResistorToday")
      )
      (libsource (lib "") (part "AECR0805F"))
    )
    (comp (ref "R131")
      (value "910")
      (fields
        (field (name "Manufacturer Part") "AECR0805F9K10K9")
        (field (name "Manufacturer") "ResistorToday")
      )
      (libsource (lib "") (part "AECR0805F"))
    )
    (comp (ref "R132")
      (value "0.10")
      (fields
        (field (name "Manufacturer Part") "AECR0805F9K10K9")
        (field (name "Manufacturer") "ResistorToday")
      )
      (libsource (lib "") (part "AECR0805F_1"))
    )
    (comp (ref "R133")
      (value "0.10")
      (fields
        (field (name "Manufacturer Part") "AECR0805F9K10K9")
        (field (name "Manufacturer") "ResistorToday")
      )
      (libsource (lib "") (part "AECR0805F_1"))
    )
    (comp (ref "R134")
      (value "910")
      (fields
        (field (name "Manufacturer Part") "AECR0805F9K10K9")
        (field (name "Manufacturer") "ResistorToday")
      )
      (libsource (lib "") (part "AECR0805F_3"))
    )
    (comp (ref "R135")
      (value "470")
      (fields
        (field (name "Manufacturer Part") "AECR0805F9K10K9")
        (field (name "Manufacturer") "ResistorToday")
      )
      (libsource (lib "") (part "AECR0805F"))
    )
    (comp (ref "R136")
      (value "910")
      (fields
        (field (name "Manufacturer Part") "AECR0805F9K10K9")
        (field (name "Manufacturer") "ResistorToday")
      )
      (libsource (lib "") (part "AECR0805F_3"))
    )
    (comp (ref "R137")
      (value "910")
      (fields
        (field (name "Manufacturer Part") "AECR0805F9K10K9")
        (field (name "Manufacturer") "ResistorToday")
      )
      (libsource (lib "") (part "AECR0805F_3"))
    )
    (comp (ref "R138")
      (value "910")
      (fields
        (field (name "Manufacturer Part") "AECR0805F9K10K9")
        (field (name "Manufacturer") "ResistorToday")
      )
      (libsource (lib "") (part "AECR0805F_3"))
    )
    (comp (ref "R139")
      (value "910")
      (fields
        (field (name "Manufacturer Part") "AECR0805F9K10K9")
        (field (name "Manufacturer") "ResistorToday")
      )
      (libsource (lib "") (part "AECR0805F_2"))
    )
    (comp (ref "R140")
      (value "910")
      (fields
        (field (name "Manufacturer Part") "AECR0805F9K10K9")
        (field (name "Manufacturer") "ResistorToday")
      )
      (libsource (lib "") (part "AECR0805F_2"))
    )
    (comp (ref "R141")
      (value "1K")
      (fields
        (field (name "Manufacturer Part") "AECR0805F9K10K9")
        (field (name "Manufacturer") "ResistorToday")
      )
      (libsource (lib "") (part "AECR0805F"))
    )
    (comp (ref "R142")
      (value "100")
      (fields
        (field (name "Manufacturer Part") "AECR0805F9K10K9")
        (field (name "Manufacturer") "ResistorToday")
      )
      (libsource (lib "") (part "AECR0805F"))
    )
    (comp (ref "R143")
      (value "100")
      (fields
        (field (name "Manufacturer Part") "AECR0805F9K10K9")
        (field (name "Manufacturer") "ResistorToday")
      )
      (libsource (lib "") (part "AECR0805F"))
    )
    (comp (ref "R144")
      (value "100")
      (fields
        (field (name "Manufacturer Part") "AECR0805F9K10K9")
        (field (name "Manufacturer") "ResistorToday")
      )
      (libsource (lib "") (part "AECR0805F"))
    )
    (comp (ref "R145")
      (value "4.7K")
      (fields
        (field (name "Manufacturer Part") "AECR0805F9K10K9")
        (field (name "Manufacturer") "ResistorToday")
      )
      (libsource (lib "") (part "AECR0805F_1"))
    )
    (comp (ref "R146")
      (value "4.7K")
      (fields
        (field (name "Manufacturer Part") "AECR0805F9K10K9")
        (field (name "Manufacturer") "ResistorToday")
      )
      (libsource (lib "") (part "AECR0805F_1"))
    )
    (comp (ref "R147")
      (value "4.7K")
      (fields
        (field (name "Manufacturer Part") "AECR0805F9K10K9")
        (field (name "Manufacturer") "ResistorToday")
      )
      (libsource (lib "") (part "AECR0805F_1"))
    )
    (comp (ref "R148")
      (value "470")
      (fields
        (field (name "Manufacturer Part") "AECR0805F9K10K9")
        (field (name "Manufacturer") "ResistorToday")
      )
      (libsource (lib "") (part "AECR0805F_2"))
    )
    (comp (ref "R149")
      (value "20K")
      (fields
        (field (name "Manufacturer Part") "AECR0805F9K10K9")
        (field (name "Manufacturer") "ResistorToday")
      )
      (libsource (lib "") (part "AECR0805F_1"))
    )
    (comp (ref "R150")
      (value "10K")
      (fields
        (field (name "Manufacturer Part") "AECR0805F9K10K9")
        (field (name "Manufacturer") "ResistorToday")
      )
      (libsource (lib "") (part "AECR0805F"))
    )
    (comp (ref "R151")
      (value "10K")
      (fields
        (field (name "Manufacturer Part") "AECR0805F9K10K9")
        (field (name "Manufacturer") "ResistorToday")
      )
      (libsource (lib "") (part "AECR0805F"))
    )
    (comp (ref "R152")
      (value "1K")
      (fields
        (field (name "Manufacturer Part") "AECR0805F9K10K9")
        (field (name "Manufacturer") "ResistorToday")
      )
      (libsource (lib "") (part "AECR0805F"))
    )
    (comp (ref "R153")
      (value "1K")
      (fields
        (field (name "Manufacturer Part") "AECR0805F9K10K9")
        (field (name "Manufacturer") "ResistorToday")
      )
      (libsource (lib "") (part "AECR0805F"))
    )
    (comp (ref "R154")
      (value "470K")
      (fields
        (field (name "Manufacturer Part") "AECR0805F9K10K9")
        (field (name "Manufacturer") "ResistorToday")
      )
      (libsource (lib "") (part "AECR0805F"))
    )
    (comp (ref "R155")
      (value "1K")
      (fields
        (field (name "Manufacturer Part") "AECR0805F9K10K9")
        (field (name "Manufacturer") "ResistorToday")
      )
      (libsource (lib "") (part "AECR0805F_3"))
    )
    (comp (ref "R156")
      (value "4.7K")
      (fields
        (field (name "Manufacturer Part") "AECR0805F9K10K9")
        (field (name "Manufacturer") "ResistorToday")
      )
      (libsource (lib "") (part "AECR0805F_1"))
    )
    (comp (ref "R157")
      (value "1K")
      (fields
        (field (name "Manufacturer Part") "AECR0805F9K10K9")
        (field (name "Manufacturer") "ResistorToday")
      )
      (libsource (lib "") (part "AECR0805F"))
    )
    (comp (ref "R158")
      (value "4.7K")
      (fields
        (field (name "Manufacturer Part") "AECR0805F9K10K9")
        (field (name "Manufacturer") "ResistorToday")
      )
      (libsource (lib "") (part "AECR0805F_1"))
    )
    (comp (ref "R159")
      (value "4.7K")
      (fields
        (field (name "Manufacturer Part") "AECR0805F9K10K9")
        (field (name "Manufacturer") "ResistorToday")
      )
      (libsource (lib "") (part "AECR0805F_1"))
    )
    (comp (ref "R160")
      (value "4.7K")
      (fields
        (field (name "Manufacturer Part") "AECR0805F9K10K9")
        (field (name "Manufacturer") "ResistorToday")
      )
      (libsource (lib "") (part "AECR0805F_1"))
    )
    (comp (ref "R163")
      (value "10K")
      (fields (field (name "Manufacturer Part") "500M"))
      (libsource (lib "") (part "500M"))
    )
    (comp (ref "R164")
      (value "10K")
      (fields (field (name "Manufacturer Part") "500M"))
      (libsource (lib "") (part "500M"))
    )
    (comp (ref "R165")
      (value "10K")
      (fields (field (name "Manufacturer Part") "500M"))
      (libsource (lib "") (part "500M"))
    )
    (comp (ref "R166")
      (value "10K")
      (fields (field (name "Manufacturer Part") "500M"))
      (libsource (lib "") (part "500M"))
    )
    (comp (ref "R167")
      (value "10K")
      (fields
        (field (name "Manufacturer Part") "AECR0805F9K10K9")
        (field (name "Manufacturer") "ResistorToday")
      )
      (libsource (lib "") (part "AECR0805F_2"))
    )
    (comp (ref "R168")
      (value "10K")
      (fields
        (field (name "Manufacturer Part") "AECR0805F9K10K9")
        (field (name "Manufacturer") "ResistorToday")
      )
      (libsource (lib "") (part "AECR0805F"))
    )
    (comp (ref "R169")
      (value "910")
      (fields
        (field (name "Manufacturer Part") "AECR0805F9K10K9")
        (field (name "Manufacturer") "ResistorToday")
      )
      (libsource (lib "") (part "AECR0805F_3"))
    )
    (comp (ref "R176")
      (value "0")
      (fields
        (field (name "Manufacturer Part") "AECR0805F9K10K9")
        (field (name "Manufacturer") "ResistorToday")
      )
      (libsource (lib "") (part "AECR0805F_2"))
    )
    (comp (ref "R177")
      (value "0")
      (fields
        (field (name "Manufacturer Part") "AECR0805F9K10K9")
        (field (name "Manufacturer") "ResistorToday")
      )
      (libsource (lib "") (part "AECR0805F_2"))
    )
    (comp (ref "R178")
      (value "0")
      (fields
        (field (name "Manufacturer Part") "AECR0805F9K10K9")
        (field (name "Manufacturer") "ResistorToday")
      )
      (libsource (lib "") (part "AECR0805F_2"))
    )
    (comp (ref "R179")
      (value "0")
      (fields
        (field (name "Manufacturer Part") "AECR0805F9K10K9")
        (field (name "Manufacturer") "ResistorToday")
      )
      (libsource (lib "") (part "AECR0805F_2"))
    )
    (comp (ref "R180")
      (value "10K")
      (fields
        (field (name "Manufacturer Part") "AECR0805F9K10K9")
        (field (name "Manufacturer") "ResistorToday")
      )
      (libsource (lib "") (part "AECR0805F_1"))
    )
    (comp (ref "R181")
      (value "10K")
      (fields
        (field (name "Manufacturer Part") "AECR0805F9K10K9")
        (field (name "Manufacturer") "ResistorToday")
      )
      (libsource (lib "") (part "AECR0805F_1"))
    )
    (comp (ref "R182")
      (value "10K")
      (fields
        (field (name "Manufacturer Part") "AECR0805F9K10K9")
        (field (name "Manufacturer") "ResistorToday")
      )
      (libsource (lib "") (part "AECR0805F_1"))
    )
    (comp (ref "R183")
      (value "10K")
      (fields
        (field (name "Manufacturer Part") "AECR0805F9K10K9")
        (field (name "Manufacturer") "ResistorToday")
      )
      (libsource (lib "") (part "AECR0805F_1"))
    )
    (comp (ref "R184")
      (value "10K")
      (fields
        (field (name "Manufacturer Part") "AECR0805F9K10K9")
        (field (name "Manufacturer") "ResistorToday")
      )
      (libsource (lib "") (part "AECR0805F_1"))
    )
    (comp (ref "R185")
      (value "10K")
      (fields
        (field (name "Manufacturer Part") "AECR0805F9K10K9")
        (field (name "Manufacturer") "ResistorToday")
      )
      (libsource (lib "") (part "AECR0805F_1"))
    )
    (comp (ref "R186")
      (value "10K")
      (fields
        (field (name "Manufacturer Part") "AECR0805F9K10K9")
        (field (name "Manufacturer") "ResistorToday")
      )
      (libsource (lib "") (part "AECR0805F_1"))
    )
    (comp (ref "R187")
      (value "10K")
      (fields
        (field (name "Manufacturer Part") "AECR0805F9K10K9")
        (field (name "Manufacturer") "ResistorToday")
      )
      (libsource (lib "") (part "AECR0805F_1"))
    )
    (comp (ref "SW1") (value "1_DIP_SWITCH_SMD") (libsource (lib "") (part "1_DIP_SWITCH_SMD")))
    (comp (ref "SW3")
      (value "RST")
      (fields (field (name "Manufacturer Part") "BDSwitch-2pin-1CH-1r27-SMD-V"))
      (libsource (lib "") (part "BDSWITCH-2PIN-1CH-1R27-SMD-V"))
    )
    (comp (ref "SW4")
      (value "BOOT")
      (fields (field (name "Manufacturer Part") "BDSwitch-2pin-1CH-1r27-SMD-V"))
      (libsource (lib "") (part "BDSWITCH-2PIN-1CH-1R27-SMD-V"))
    )
    (comp (ref "U1") (value "2A Fuse") (libsource (lib "") (part "Car fuse mini")))
    (comp (ref "U2")
      (value "14D220K")
      (fields (field (name "Manufacturer") "HEL"))
      (libsource (lib "") (part "14D220K"))
    )
    (comp (ref "U3")
      (value "ULN2803A")
      (fields (field (name "Manufacturer") "UMW(Youtai Semiconductor Co., Ltd.)"))
      (libsource (lib "") (part "ULN2803A_C845537"))
    )
    (comp (ref "U4")
      (value "SN74HCT541")
      (fields (field (name "Manufacturer Part") "SN74HCT541DWE4") (field (name "Manufacturer") "TI(德州仪器)"))
      (libsource (lib "") (part "SN74HCT541DWE4"))
    )
    (comp (ref "U5")
      (value "LM2903")
      (fields (field (name "Manufacturer Part") "LM2903M/NOPB") (field (name "Manufacturer") "TI(德州仪器)"))
      (libsource (lib "") (part "LM2903M/NOPB"))
    )
    (comp (ref "U6") (value "HC05 Module") (libsource (lib "") (part "HC05 Module")))
    (comp (ref "U7")
      (value "SN74HCT541")
      (fields (field (name "Manufacturer Part") "SN74HCT541DWE4") (field (name "Manufacturer") "TI(德州仪器)"))
      (libsource (lib "") (part "SN74HCT541DWE4"))
    )
    (comp (ref "U8")
      (value "ULN2803A")
      (fields (field (name "Manufacturer") "UMW(Youtai Semiconductor Co., Ltd.)"))
      (libsource (lib "") (part "ULN2803A_C845537"))
    )
    (comp (ref "U9")
      (value "LED")
      (fields (field (name "Manufacturer Part") "0805 SF-Red"))
      (libsource (lib "") (part "0805 SF-RED_2"))
    )
    (comp (ref "U10")
      (value "LED")
      (fields (field (name "Manufacturer Part") "0805 SF-Red"))
      (libsource (lib "") (part "0805 SF-RED_2"))
    )
    (comp (ref "U11")
      (value "LED")
      (fields (field (name "Manufacturer Part") "0805 SF-Red"))
      (libsource (lib "") (part "0805 SF-RED_2"))
    )
    (comp (ref "U12")
      (value "LED")
      (fields (field (name "Manufacturer Part") "0805 SF-Red"))
      (libsource (lib "") (part "0805 SF-RED"))
    )
    (comp (ref "U13") (value "2A Fuse") (libsource (lib "") (part "Car fuse mini")))
    (comp (ref "U14")
      (value "LED")
      (fields (field (name "Manufacturer Part") "0805 SF-Red"))
      (libsource (lib "") (part "0805 SF-RED_1"))
    )
    (comp (ref "U16")
      (value "LED")
      (fields (field (name "Manufacturer Part") "0805 SF-Red"))
      (libsource (lib "") (part "0805 SF-RED_1"))
    )
    (comp (ref "U17")
      (value "LED")
      (fields (field (name "Manufacturer Part") "0805 SF-Red"))
      (libsource (lib "") (part "0805 SF-RED"))
    )
    (comp (ref "U18")
      (value "LED")
      (fields (field (name "Manufacturer Part") "0805 SF-Red"))
      (libsource (lib "") (part "0805 SF-RED"))
    )
    (comp (ref "U19")
      (value "LED")
      (fields (field (name "Manufacturer Part") "0805 SF-Red"))
      (libsource (lib "") (part "0805 SF-RED"))
    )
    (comp (ref "U20")
      (value "LED")
      (fields (field (name "Manufacturer Part") "0805 SF-Red"))
      (libsource (lib "") (part "0805 SF-RED"))
    )
    (comp (ref "U21")
      (value "LED")
      (fields (field (name "Manufacturer Part") "0805 SF-Red"))
      (libsource (lib "") (part "0805 SF-RED"))
    )
    (comp (ref "U22")
      (value "LED")
      (fields (field (name "Manufacturer Part") "0805 SF-Red"))
      (libsource (lib "") (part "0805 SF-RED"))
    )
    (comp (ref "U23")
      (value "LED")
      (fields (field (name "Manufacturer Part") "0805 SF-Red"))
      (libsource (lib "") (part "0805 SF-RED"))
    )
    (comp (ref "U24")
      (value "LED")
      (fields (field (name "Manufacturer Part") "0805 SF-Red"))
      (libsource (lib "") (part "0805 SF-RED_2"))
    )
    (comp (ref "U25")
      (value "LED")
      (fields (field (name "Manufacturer Part") "0805 SF-Red"))
      (libsource (lib "") (part "0805 SF-RED_2"))
    )
    (comp (ref "U26")
      (value "LED")
      (fields (field (name "Manufacturer Part") "0805 SF-Red"))
      (libsource (lib "") (part "0805 SF-RED_1"))
    )
    (comp (ref "U27")
      (value "LED")
      (fields (field (name "Manufacturer Part") "0805 SF-Red"))
      (libsource (lib "") (part "0805 SF-RED_2"))
    )
    (comp (ref "U28")
      (value "LED")
      (fields (field (name "Manufacturer Part") "0805 SF-Red"))
      (libsource (lib "") (part "0805 SF-RED_2"))
    )
    (comp (ref "U29")
      (value "LED")
      (fields (field (name "Manufacturer Part") "0805 SF-Red"))
      (libsource (lib "") (part "0805 SF-RED_2"))
    )
    (comp (ref "U32")
      (value "Native USB")
      (fields (field (name "Manufacturer Part") "Male Header 2 pin"))
      (libsource (lib "") (part "1X4 Header (Pin = 2.54)"))
    )
    (comp (ref "U34") (value "1N4148") (libsource (lib "") (part "1N4148_C9900015438")))
    (comp (ref "U35") (value "1N4148") (libsource (lib "") (part "1N4148_C9900015438")))
    (comp (ref "U36")
      (value "STLink")
      (fields (field (name "Manufacturer Part") "Male Header 2 pin"))
      (libsource (lib "") (part "1X4 Header (Pin = 2.54)"))
    )
    (comp (ref "U37")
      (value "Bosh SMD284")
      (fields (field (name "Manufacturer Part") "TC4424AVPA") (field (name "Manufacturer") "MICROCHIP(美国微芯)"))
      (libsource (lib "") (part "Bosh SMD284"))
    )
    (comp (ref "U38")
      (value "33uH")
      (fields (field (name "Manufacturer Part") "SMDRI125-330MT") (field (name "Manufacturer") "SXN(顺翔诺)"))
      (libsource (lib "") (part "SMDRI125-330MT"))
    )
    (comp (ref "U39")
      (value "LM2596-ADJ")
      (fields (field (name "Manufacturer Part") "LM2596GR-5.0") (field (name "Manufacturer") "HTC"))
      (libsource (lib "") (part "LM2596GR-5.0"))
    )
    (comp (ref "U40") (value "1N5822-SS34") (libsource (lib "") (part "1N5822-SS34_1")))
    (comp (ref "U41") (value "1N5822-SS34") (libsource (lib "") (part "1N5822-SS34")))
    (comp (ref "U42")
      (value "SN74HCT541")
      (fields (field (name "Manufacturer Part") "SN74HCT541DWE4") (field (name "Manufacturer") "TI(德州仪器)"))
      (libsource (lib "") (part "SN74HCT541DWE4"))
    )
    (comp (ref "U50")
      (value "LED")
      (fields (field (name "Manufacturer Part") "0805 SF-Red"))
      (libsource (lib "") (part "0805 SF-RED"))
    )
    (comp (ref "U52")
      (value "MCP2551")
      (fields (field (name "Manufacturer Part") "MCP2551T-I/SN") (field (name "Manufacturer") "MICROCHIP"))
      (libsource (lib "") (part "MCP2551T-I/SN"))
    )
    (comp (ref "U53")
      (value "STM32F407VET6")
      (fields (field (name "Manufacturer") "ST"))
      (libsource (lib "") (part "STM32F407VGT6"))
    )
    (comp (ref "U56")
      (value "DRV8825PWP")
      (fields (field (name "Manufacturer") "TI(德州仪器)"))
      (libsource (lib "") (part "DRV8825PWP"))
    )
    (comp (ref "U57") (value "SMD33-10K") (libsource (lib "") (part "SMD33-10K")))
    (comp (ref "U62") (value "1N5822-SS34") (libsource (lib "") (part "1N5822-SS34_1")))
    (comp (ref "U63")
      (value "LM2596-ADJ")
      (fields (field (name "Manufacturer Part") "LM2596GR-5.0") (field (name "Manufacturer") "HTC"))
      (libsource (lib "") (part "LM2596GR-5.0"))
    )
    (comp (ref "U64")
      (value "33uH")
      (fields (field (name "Manufacturer Part") "SMDRI125-330MT") (field (name "Manufacturer") "SXN(顺翔诺)"))
      (libsource (lib "") (part "SMDRI125-330MT"))
    )
    (comp (ref "USB1")
      (value "U241-041N-1BR85-1")
      (fields (field (name "Manufacturer") "XKB Enterprise"))
      (libsource (lib "") (part "U241-041N-1BR85-1"))
    )
    (comp (ref "X1")
      (value "12MHZ")
      (fields (field (name "Manufacturer Part") "XTAL-HC-49SMD"))
      (libsource (lib "") (part "XTAL-HC-49SMD"))
    )
    (comp (ref "X2")
      (value "8MHz")
      (fields
        (field (name "Manufacturer Part") "H6OEL89CSC-SUGYLC-8M")
        (field (name "Manufacturer") "YXC(扬兴晶振)")
      )
      (libsource (lib "") (part "H6OEL89CSC-SUGYLC-8M"))
    )
    (comp (ref "X3")
      (value "32.768kHz")
      (fields
        (field (name "Manufacturer Part") "TAXM32768K2BGDAZN2T")
        (field (name "Manufacturer") "YJX(雅晶鑫)")
      )
      (libsource (lib "") (part "TMXLi-206F 32.768KHZ 12.5PF 20PPM"))
    )
  )
  (nets
    (net (code "1") (name "+3.3V") (class "Default")
      (node (ref "C23") (pin "2") (pinfunction "2_2") (pintype "input"))
      (node (ref "C29") (pin "2") (pinfunction "2_2") (pintype "input"))
      (node (ref "C32") (pin "1") (pinfunction "1_1") (pintype "input"))
      (node (ref "C42") (pin "1") (pinfunction "1_1") (pintype "input"))
      (node (ref "C44") (pin "2") (pinfunction "2_2") (pintype "input"))
      (node (ref "C45") (pin "2") (pinfunction "2_2") (pintype "input"))
      (node (ref "C49") (pin "1") (pinfunction "1_1") (pintype "unspecified"))
      (node (ref "C59") (pin "2") (pinfunction "2_2") (pintype "input"))
      (node (ref "C60") (pin "2") (pinfunction "2_2") (pintype "input"))
      (node (ref "C63") (pin "1") (pinfunction "1_1") (pintype "unspecified"))
      (node (ref "C67") (pin "1") (pinfunction "1_1") (pintype "input"))
      (node (ref "C69") (pin "2") (pinfunction "2_2") (pintype "unspecified"))
      (node (ref "C72") (pin "1") (pinfunction "1_1") (pintype "unspecified"))
      (node (ref "C73") (pin "1") (pinfunction "1_1") (pintype "unspecified"))
      (node (ref "D15") (pin "1") (pinfunction "K_1") (pintype "unspecified"))
      (node (ref "D19") (pin "16") (pinfunction "V+_16") (pintype "unspecified"))
      (node (ref "IC1") (pin "16") (pinfunction "VCC_16") (pintype "unspecified"))
      (node (ref "IC1") (pin "4") (pinfunction "DTR_4") (pintype "unspecified"))
      (node (ref "MICROSD1") (pin "4") (pinfunction "VDD_4") (pintype "unspecified"))
      (node (ref "R163") (pin "2") (pinfunction "2_2") (pintype "unspecified"))
      (node (ref "R164") (pin "2") (pinfunction "2_2") (pintype "unspecified"))
      (node (ref "R165") (pin "2") (pinfunction "2_2") (pintype "unspecified"))
      (node (ref "R166") (pin "2") (pinfunction "2_2") (pintype "unspecified"))
      (node (ref "R167") (pin "2") (pinfunction "2_2") (pintype "unspecified"))
      (node (ref "R40") (pin "2") (pinfunction "2_2") (pintype "unspecified"))
      (node (ref "R71") (pin "1") (pinfunction "1_1") (pintype "unspecified"))
      (node (ref "R76") (pin "2") (pinfunction "2_2") (pintype "unspecified"))
      (node (ref "R89") (pin "1") (pinfunction "1_1") (pintype "unspecified"))
      (node (ref "SW4") (pin "1") (pinfunction "A1_1") (pintype "input"))
      (node (ref "U35") (pin "1") (pinfunction "1_1") (pintype "unspecified"))
      (node (ref "U36") (pin "4") (pinfunction "4_4") (pintype "unspecified"))
      (node (ref "U50") (pin "2") (pinfunction "A_2") (pintype "unspecified"))
      (node (ref "U53") (pin "100") (pinfunction "VDD_100") (pintype "unspecified"))
      (node (ref "U53") (pin "11") (pinfunction "VDD_11") (pintype "unspecified"))
      (node (ref "U53") (pin "19") (pinfunction "VDD_19") (pintype "unspecified"))
      (node (ref "U53") (pin "22") (pinfunction "VDDA_22") (pintype "unspecified"))
      (node (ref "U53") (pin "28") (pinfunction "VDD_28") (pintype "unspecified"))
      (node (ref "U53") (pin "50") (pinfunction "VDD_50") (pintype "unspecified"))
      (node (ref "U53") (pin "6") (pinfunction "VBAT_6") (pintype "unspecified"))
      (node (ref "U53") (pin "75") (pinfunction "VDD_75") (pintype "unspecified"))
      (node (ref "U64") (pin "2") (pinfunction "2_2") (pintype "unspecified"))
    )
    (net (code "2") (name "+5V") (class "Default")
      (node (ref "C17") (pin "1") (pinfunction "1_1") (pintype "input"))
      (node (ref "C19") (pin "1") (pinfunction "1_1") (pintype "input"))
      (node (ref "C20") (pin "1") (pinfunction "1_1") (pintype "input"))
      (node (ref "C30") (pin "1") (pinfunction "1_1") (pintype "input"))
      (node (ref "C37") (pin "1") (pinfunction "1_1") (pintype "input"))
      (node (ref "C47") (pin "1") (pinfunction "1_1") (pintype "input"))
      (node (ref "C50") (pin "1") (pinfunction "1_1") (pintype "input"))
      (node (ref "C54") (pin "1") (pinfunction "1_1") (pintype "input"))
      (node (ref "C56") (pin "2") (pinfunction "2_2") (pintype "input"))
      (node (ref "C57") (pin "1") (pinfunction "1_1") (pintype "input"))
      (node (ref "CN1") (pin "13") (pinfunction "13_13") (pintype "unspecified"))
      (node (ref "CN2") (pin "3") (pinfunction "3_3") (pintype "unspecified"))
      (node (ref "R1") (pin "1") (pinfunction "1_1") (pintype "unspecified"))
      (node (ref "R109") (pin "1") (pinfunction "1_1") (pintype "unspecified"))
      (node (ref "R130") (pin "2") (pinfunction "2_2") (pintype "unspecified"))
      (node (ref "R153") (pin "1") (pinfunction "1_1") (pintype "unspecified"))
      (node (ref "R155") (pin "1") (pinfunction "1_1") (pintype "unspecified"))
      (node (ref "R157") (pin "1") (pinfunction "1_1") (pintype "unspecified"))
      (node (ref "R37") (pin "1") (pinfunction "1_1") (pintype "input"))
      (node (ref "R38") (pin "1") (pinfunction "1_1") (pintype "input"))
      (node (ref "R4") (pin "1") (pinfunction "1_1") (pintype "unspecified"))
      (node (ref "R45") (pin "1") (pinfunction "1_1") (pintype "unspecified"))
      (node (ref "R47") (pin "1") (pinfunction "1_1") (pintype "unspecified"))
      (node (ref "R61") (pin "1") (pinfunction "1_1") (pintype "unspecified"))
      (node (ref "R85") (pin "1") (pinfunction "1_1") (pintype "unspecified"))
      (node (ref "U1") (pin "2") (pinfunction "2_2") (pintype "unspecified"))
      (node (ref "U37") (pin "1") (pinfunction "VDD_1") (pintype "unspecified"))
      (node (ref "U4") (pin "20") (pinfunction "VCC_20") (pintype "unspecified"))
      (node (ref "U42") (pin "20") (pinfunction "VCC_20") (pintype "unspecified"))
      (node (ref "U5") (pin "8") (pinfunction "V+_8") (pintype "unspecified"))
      (node (ref "U52") (pin "3") (pinfunction "VDD_3") (pintype "unspecified"))
      (node (ref "U6") (pin "4") (pinfunction "VCC_4") (pintype "passive"))
      (node (ref "U7") (pin "20") (pinfunction "VCC_20") (pintype "unspecified"))
      (node (ref "U8") (pin "7") (pinfunction "Input_7") (pintype "unspecified"))
      (node (ref "U8") (pin "8") (pinfunction "Input_8") (pintype "unspecified"))
    )
    (net (code "3") (name "+12V") (class "Default")
      (node (ref "C15") (pin "1") (pinfunction "1_1") (pintype "input"))
      (node (ref "C24") (pin "1") (pinfunction "1_1") (pintype "input"))
      (node (ref "C31") (pin "1") (pinfunction "1_1") (pintype "unspecified"))
      (node (ref "C33") (pin "1") (pinfunction "1_1") (pintype "input"))
      (node (ref "C41") (pin "1") (pinfunction "1_1") (pintype "input"))
      (node (ref "C48") (pin "2") (pinfunction "2_2") (pintype "input"))
      (node (ref "C52") (pin "1") (pinfunction "1_1") (pintype "input"))
      (node (ref "C53") (pin "1") (pinfunction "1_1") (pintype "input"))
      (node (ref "C75") (pin "1") (pinfunction "1_1") (pintype "input"))
      (node (ref "D1") (pin "1") (pinfunction "K_1") (pintype "unspecified"))
      (node (ref "D10") (pin "1") (pinfunction "K_1") (pintype "unspecified"))
      (node (ref "D13") (pin "1") (pinfunction "K_1") (pintype "unspecified"))
      (node (ref "D16") (pin "1") (pinfunction "K_1") (pintype "unspecified"))
      (node (ref "D17") (pin "1") (pinfunction "K_1") (pintype "unspecified"))
      (node (ref "D28") (pin "1") (pinfunction "K_1") (pintype "unspecified"))
      (node (ref "D29") (pin "1") (pinfunction "K_1") (pintype "unspecified"))
      (node (ref "D3") (pin "1") (pinfunction "K_1") (pintype "unspecified"))
      (node (ref "D30") (pin "1") (pinfunction "K_1") (pintype "unspecified"))
      (node (ref "D31") (pin "1") (pinfunction "K_1") (pintype "unspecified"))
      (node (ref "D4") (pin "1") (pinfunction "K_1") (pintype "unspecified"))
      (node (ref "D6") (pin "1") (pinfunction "K_1") (pintype "unspecified"))
      (node (ref "D7") (pin "1") (pinfunction "K_1") (pintype "unspecified"))
      (node (ref "D8") (pin "1") (pinfunction "K_1") (pintype "unspecified"))
      (node (ref "D9") (pin "1") (pinfunction "K_1") (pintype "unspecified"))
      (node (ref "R113") (pin "1") (pinfunction "1_1") (pintype "unspecified"))
      (node (ref "R52") (pin "1") (pinfunction "1_1") (pintype "unspecified"))
      (node (ref "U3") (pin "10") (pinfunction "COM_10") (pintype "unspecified"))
      (node (ref "U39") (pin "1") (pinfunction "VIN_1") (pintype "unspecified"))
      (node (ref "U56") (pin "11") (pinfunction "VMB_11") (pintype "unspecified"))
      (node (ref "U56") (pin "4") (pinfunction "VMA_4") (pintype "unspecified"))
      (node (ref "U63") (pin "1") (pinfunction "VIN_1") (pintype "unspecified"))
      (node (ref "U8") (pin "10") (pinfunction "COM_10") (pintype "unspecified"))
    )
    (net (code "4") (name "/+CAM-IN-D18") (class "Default")
      (node (ref "CN1") (pin "5") (pinfunction "5_5") (pintype "unspecified"))
      (node (ref "R24") (pin "2") (pinfunction "2_2") (pintype "unspecified"))
      (node (ref "R50") (pin "2") (pinfunction "2_2") (pintype "unspecified"))
    )
    (net (code "5") (name "/+CRANK-IN-D19") (class "Default")
      (node (ref "CN1") (pin "3") (pinfunction "3_3") (pintype "unspecified"))
      (node (ref "R149") (pin "1") (pinfunction "1_1") (pintype "unspecified"))
      (node (ref "R151") (pin "2") (pinfunction "2_2") (pintype "unspecified"))
    )
    (net (code "6") (name "/-CAM-IN-D18") (class "Default")
      (node (ref "CN1") (pin "6") (pinfunction "6_6") (pintype "unspecified"))
      (node (ref "JP2") (pin "2") (pinfunction "2_2") (pintype "unspecified"))
    )
    (net (code "7") (name "/-CRANK-IN-D19") (class "Default")
      (node (ref "CN1") (pin "4") (pinfunction "4_4") (pintype "unspecified"))
      (node (ref "R149") (pin "2") (pinfunction "2_2") (pintype "unspecified"))
      (node (ref "R150") (pin "2") (pinfunction "2_2") (pintype "unspecified"))
    )
    (net (code "8") (name "/AC-IN-D13") (class "Default")
      (node (ref "CN1") (pin "16") (pinfunction "16_16") (pintype "unspecified"))
      (node (ref "R56") (pin "1") (pinfunction "1_1") (pintype "unspecified"))
    )
    (net (code "9") (name "/AC-OUT-D23") (class "Default")
      (node (ref "CN4") (pin "3") (pinfunction "3_3") (pintype "unspecified"))
      (node (ref "U3") (pin "15") (pinfunction "Output_15") (pintype "unspecified"))
      (node (ref "U3") (pin "16") (pinfunction "Output_16") (pintype "unspecified"))
    )
    (net (code "10") (name "/AC-ULN-D23") (class "Default")
      (node (ref "U3") (pin "3") (pinfunction "Input_3") (pintype "unspecified"))
      (node (ref "U3") (pin "4") (pinfunction "Input_4") (pintype "unspecified"))
      (node (ref "U7") (pin "11") (pinfunction "Y8_11") (pintype "unspecified"))
    )
    (net (code "11") (name "/AUX-IN-D30") (class "Default")
      (node (ref "CN1") (pin "2") (pinfunction "2_2") (pintype "unspecified"))
      (node (ref "R25") (pin "1") (pinfunction "1_1") (pintype "unspecified"))
    )
    (net (code "12") (name "/AUX-IN-D33") (class "Default")
      (node (ref "CN1") (pin "7") (pinfunction "7_7") (pintype "unspecified"))
      (node (ref "R46") (pin "1") (pinfunction "1_1") (pintype "unspecified"))
    )
    (net (code "13") (name "/AUX-MOS-D31") (class "Default")
      (node (ref "R105") (pin "2") (pinfunction "2_2") (pintype "unspecified"))
      (node (ref "U7") (pin "15") (pinfunction "Y4_15") (pintype "unspecified"))
    )
    (net (code "14") (name "/AUX-OUT-D31") (class "Default")
      (node (ref "CN4") (pin "10") (pinfunction "10_10") (pintype "unspecified"))
      (node (ref "D31") (pin "2") (pinfunction "A_2") (pintype "unspecified"))
      (node (ref "Q20") (pin "2") (pinfunction "D_2") (pintype "unspecified"))
    )
    (net (code "15") (name "/Analog-IN-A10") (class "Default")
      (node (ref "CN1") (pin "8") (pinfunction "8_8") (pintype "unspecified"))
      (node (ref "JP8") (pin "2") (pinfunction "2_2") (pintype "unspecified"))
      (node (ref "R27") (pin "1") (pinfunction "1_1") (pintype "unspecified"))
    )
    (net (code "16") (name "/Analog-IN-A11") (class "Default")
      (node (ref "CN1") (pin "14") (pinfunction "14_14") (pintype "unspecified"))
      (node (ref "JP6") (pin "2") (pinfunction "2_2") (pintype "unspecified"))
      (node (ref "R23") (pin "1") (pinfunction "1_1") (pintype "unspecified"))
    )
    (net (code "17") (name "/Analog-IN-A12") (class "Default")
      (node (ref "CN1") (pin "18") (pinfunction "18_18") (pintype "unspecified"))
      (node (ref "JP1") (pin "2") (pinfunction "2_2") (pintype "unspecified"))
      (node (ref "R107") (pin "1") (pinfunction "1_1") (pintype "unspecified"))
    )
    (net (code "18") (name "/BOOST-MOS-D7") (class "Default")
      (node (ref "R28") (pin "2") (pinfunction "2_2") (pintype "unspecified"))
      (node (ref "U7") (pin "18") (pinfunction "Y1_18") (pintype "unspecified"))
    )
    (net (code "19") (name "/BOOST-OUT-D7") (class "Default")
      (node (ref "CN4") (pin "16") (pinfunction "16_16") (pintype "unspecified"))
      (node (ref "D28") (pin "2") (pinfunction "A_2") (pintype "unspecified"))
      (node (ref "Q17") (pin "2") (pinfunction "D_2") (pintype "unspecified"))
    )
    (net (code "20") (name "/CLT-IN-A1") (class "Default")
      (node (ref "C5") (pin "1") (pinfunction "1_1") (pintype "input"))
      (node (ref "CN1") (pin "22") (pinfunction "22_22") (pintype "unspecified"))
      (node (ref "R22") (pin "2") (pinfunction "2_2") (pintype "unspecified"))
      (node (ref "R4") (pin "2") (pinfunction "2_2") (pintype "unspecified"))
    )
    (net (code "21") (name "/CLUCH-IN-D51") (class "Default")
      (node (ref "CN1") (pin "17") (pinfunction "17_17") (pintype "unspecified"))
      (node (ref "R48") (pin "1") (pinfunction "1_1") (pintype "unspecified"))
    )
    (net (code "22") (name "/DTR") (class "Default")
      (node (ref "4") (pin "3") (pinfunction "E_3") (pintype "bidirectional"))
      (node (ref "IC1") (pin "13") (pinfunction "V3_13") (pintype "unspecified"))
      (node (ref "R66") (pin "1") (pinfunction "1_1") (pintype "unspecified"))
    )
    (net (code "23") (name "/FAN-OUT-D47") (class "Default")
      (node (ref "CN4") (pin "8") (pinfunction "8_8") (pintype "unspecified"))
      (node (ref "U8") (pin "17") (pinfunction "Output_17") (pintype "unspecified"))
      (node (ref "U8") (pin "18") (pinfunction "Output_18") (pintype "unspecified"))
    )
    (net (code "24") (name "/FAN-ULN-D47") (class "Default")
      (node (ref "U7") (pin "14") (pinfunction "Y5_14") (pintype "unspecified"))
      (node (ref "U8") (pin "1") (pinfunction "Input_1") (pintype "unspecified"))
      (node (ref "U8") (pin "2") (pinfunction "Input_2") (pintype "unspecified"))
    )
    (net (code "25") (name "/FULE-OUT-D45") (class "Default")
      (node (ref "CN4") (pin "6") (pinfunction "6_6") (pintype "unspecified"))
      (node (ref "U8") (pin "13") (pinfunction "Output_13") (pintype "unspecified"))
      (node (ref "U8") (pin "14") (pinfunction "Output_14") (pintype "unspecified"))
      (node (ref "U8") (pin "15") (pinfunction "Output_15") (pintype "unspecified"))
      (node (ref "U8") (pin "16") (pinfunction "Output_16") (pintype "unspecified"))
    )
    (net (code "26") (name "/FULE-ULN-D45") (class "Default")
      (node (ref "U7") (pin "13") (pinfunction "Y6_13") (pintype "unspecified"))
      (node (ref "U8") (pin "3") (pinfunction "Input_3") (pintype "unspecified"))
      (node (ref "U8") (pin "4") (pinfunction "Input_4") (pintype "unspecified"))
      (node (ref "U8") (pin "5") (pinfunction "Input_5") (pintype "unspecified"))
      (node (ref "U8") (pin "6") (pinfunction "Input_6") (pintype "unspecified"))
    )
    (net (code "27") (name "/FULE2-OUT-5V") (class "Default")
      (node (ref "CN4") (pin "4") (pinfunction "4_4") (pintype "unspecified"))
      (node (ref "U8") (pin "11") (pinfunction "Output_11") (pintype "unspecified"))
      (node (ref "U8") (pin "12") (pinfunction "Output_12") (pintype "unspecified"))
    )
    (net (code "28") (name "/FlashCS") (class "Default")
      (node (ref "R89") (pin "2") (pinfunction "2_2") (pintype "unspecified"))
    )
    (net (code "29") (name "/Flex-IN-D2") (class "Default")
      (node (ref "CN1") (pin "15") (pinfunction "15_15") (pintype "unspecified"))
      (node (ref "R36") (pin "1") (pinfunction "1_1") (pintype "unspecified"))
    )
    (net (code "30") (name "/IAT-IN-A0") (class "Default")
      (node (ref "C3") (pin "1") (pinfunction "1_1") (pintype "input"))
      (node (ref "CN1") (pin "23") (pinfunction "23_23") (pintype "unspecified"))
      (node (ref "R1") (pin "2") (pinfunction "2_2") (pintype "unspecified"))
      (node (ref "R2") (pin "2") (pinfunction "2_2") (pintype "unspecified"))
    )
    (net (code "31") (name "/IDLE1-OUT-D5") (class "Default")
      (node (ref "CN4") (pin "5") (pinfunction "5_5") (pintype "unspecified"))
      (node (ref "D16") (pin "2") (pinfunction "A_2") (pintype "unspecified"))
      (node (ref "U3") (pin "13") (pinfunction "Output_13") (pintype "unspecified"))
      (node (ref "U3") (pin "14") (pinfunction "Output_14") (pintype "unspecified"))
    )
    (net (code "32") (name "/IDLE2-OUT-D6") (class "Default")
      (node (ref "CN4") (pin "7") (pinfunction "7_7") (pintype "unspecified"))
      (node (ref "D6") (pin "2") (pinfunction "A_2") (pintype "unspecified"))
      (node (ref "U3") (pin "11") (pinfunction "Output_11") (pintype "unspecified"))
      (node (ref "U3") (pin "12") (pinfunction "Output_12") (pintype "unspecified"))
    )
    (net (code "33") (name "/IGN1-Mosfet") (class "Default")
      (node (ref "CN4") (pin "30") (pinfunction "30_30") (pintype "unspecified"))
      (node (ref "R126") (pin "1") (pinfunction "1_1") (pintype "unspecified"))
      (node (ref "R146") (pin "2") (pinfunction "2_2") (pintype "unspecified"))
    )
    (net (code "34") (name "/IGN2-Mosfet") (class "Default")
      (node (ref "CN4") (pin "28") (pinfunction "28_28") (pintype "unspecified"))
      (node (ref "R127") (pin "1") (pinfunction "1_1") (pintype "unspecified"))
      (node (ref "R147") (pin "2") (pinfunction "2_2") (pintype "unspecified"))
    )
    (net (code "35") (name "/IGN3-Mosfet") (class "Default")
      (node (ref "CN4") (pin "20") (pinfunction "20_20") (pintype "unspecified"))
      (node (ref "R144") (pin "1") (pinfunction "1_1") (pintype "unspecified"))
      (node (ref "R160") (pin "2") (pinfunction "2_2") (pintype "unspecified"))
    )
    (net (code "36") (name "/IGN4-Mosfet") (class "Default")
      (node (ref "CN4") (pin "22") (pinfunction "22_22") (pintype "unspecified"))
      (node (ref "R143") (pin "1") (pinfunction "1_1") (pintype "unspecified"))
      (node (ref "R159") (pin "2") (pinfunction "2_2") (pintype "unspecified"))
    )
    (net (code "37") (name "/IGN5-Mosfet") (class "Default")
      (node (ref "CN4") (pin "26") (pinfunction "26_26") (pintype "unspecified"))
      (node (ref "R128") (pin "1") (pinfunction "1_1") (pintype "unspecified"))
      (node (ref "R156") (pin "2") (pinfunction "2_2") (pintype "unspecified"))
    )
    (net (code "38") (name "/IGN6-Mosfet") (class "Default")
      (node (ref "CN4") (pin "24") (pinfunction "24_24") (pintype "unspecified"))
      (node (ref "R142") (pin "1") (pinfunction "1_1") (pintype "unspecified"))
      (node (ref "R158") (pin "2") (pinfunction "2_2") (pintype "unspecified"))
    )
    (net (code "39") (name "/IGN7-Mosfet") (class "Default")
      (node (ref "CN4") (pin "32") (pinfunction "32_32") (pintype "unspecified"))
      (node (ref "R125") (pin "1") (pinfunction "1_1") (pintype "unspecified"))
      (node (ref "R145") (pin "2") (pinfunction "2_2") (pintype "unspecified"))
    )
    (net (code "40") (name "/IGN8-Mosfet") (class "Default")
      (node (ref "CN4") (pin "34") (pinfunction "34_34") (pintype "unspecified"))
      (node (ref "R123") (pin "2") (pinfunction "2_2") (pintype "unspecified"))
      (node (ref "R124") (pin "1") (pinfunction "1_1") (pintype "unspecified"))
    )
    (net (code "41") (name "/INJ1-Mosfet") (class "Default")
      (node (ref "R31") (pin "2") (pinfunction "2_2") (pintype "unspecified"))
      (node (ref "U4") (pin "17") (pinfunction "Y2_17") (pintype "unspecified"))
    )
    (net (code "42") (name "/INJ1-OUT") (class "Default")
      (node (ref "CN4") (pin "19") (pinfunction "19_19") (pintype "unspecified"))
      (node (ref "D10") (pin "2") (pinfunction "A_2") (pintype "unspecified"))
      (node (ref "Q15") (pin "2") (pinfunction "D_2") (pintype "unspecified"))
    )
    (net (code "43") (name "/INJ2-Mosfet") (class "Default")
      (node (ref "R19") (pin "2") (pinfunction "2_2") (pintype "unspecified"))
      (node (ref "U4") (pin "16") (pinfunction "Y3_16") (pintype "unspecified"))
    )
    (net (code "44") (name "/INJ2-OUT") (class "Default")
      (node (ref "CN4") (pin "25") (pinfunction "25_25") (pintype "unspecified"))
      (node (ref "D9") (pin "2") (pinfunction "A_2") (pintype "unspecified"))
      (node (ref "Q14") (pin "2") (pinfunction "D_2") (pintype "unspecified"))
    )
    (net (code "45") (name "/INJ3-Mosfet") (class "Default")
      (node (ref "R15") (pin "2") (pinfunction "2_2") (pintype "unspecified"))
      (node (ref "U4") (pin "14") (pinfunction "Y5_14") (pintype "unspecified"))
    )
    (net (code "46") (name "/INJ3-OUT") (class "Default")
      (node (ref "CN4") (pin "29") (pinfunction "29_29") (pintype "unspecified"))
      (node (ref "D7") (pin "2") (pinfunction "A_2") (pintype "unspecified"))
      (node (ref "Q12") (pin "2") (pinfunction "D_2") (pintype "unspecified"))
    )
    (net (code "47") (name "/INJ4-Mosfet") (class "Default")
      (node (ref "R17") (pin "2") (pinfunction "2_2") (pintype "unspecified"))
      (node (ref "U4") (pin "15") (pinfunction "Y4_15") (pintype "unspecified"))
    )
    (net (code "48") (name "/INJ4-OUT") (class "Default")
      (node (ref "CN4") (pin "23") (pinfunction "23_23") (pintype "unspecified"))
      (node (ref "D8") (pin "2") (pinfunction "A_2") (pintype "unspecified"))
      (node (ref "Q13") (pin "2") (pinfunction "D_2") (pintype "unspecified"))
    )
    (net (code "49") (name "/INJ5-Mosfet") (class "Default")
      (node (ref "R33") (pin "2") (pinfunction "2_2") (pintype "unspecified"))
      (node (ref "U4") (pin "18") (pinfunction "Y1_18") (pintype "unspecified"))
    )
    (net (code "50") (name "/INJ5-OUT") (class "Default")
      (node (ref "CN4") (pin "21") (pinfunction "21_21") (pintype "unspecified"))
      (node (ref "D13") (pin "2") (pinfunction "A_2") (pintype "unspecified"))
      (node (ref "Q16") (pin "2") (pinfunction "D_2") (pintype "unspecified"))
    )
    (net (code "51") (name "/INJ6-Mosfet") (class "Default")
      (node (ref "R10") (pin "2") (pinfunction "2_2") (pintype "unspecified"))
      (node (ref "U4") (pin "11") (pinfunction "Y8_11") (pintype "unspecified"))
    )
    (net (code "52") (name "/INJ6-OUT") (class "Default")
      (node (ref "CN4") (pin "31") (pinfunction "31_31") (pintype "unspecified"))
      (node (ref "D3") (pin "2") (pinfunction "A_2") (pintype "unspecified"))
      (node (ref "Q9") (pin "2") (pinfunction "D_2") (pintype "unspecified"))
    )
    (net (code "53") (name "/INJ7-Mosfet") (class "Default")
      (node (ref "R13") (pin "2") (pinfunction "2_2") (pintype "unspecified"))
      (node (ref "U4") (pin "13") (pinfunction "Y6_13") (pintype "unspecified"))
    )
    (net (code "54") (name "/INJ7-OUT") (class "Default")
      (node (ref "CN4") (pin "27") (pinfunction "27_27") (pintype "unspecified"))
      (node (ref "D4") (pin "2") (pinfunction "A_2") (pintype "unspecified"))
      (node (ref "Q11") (pin "2") (pinfunction "D_2") (pintype "unspecified"))
    )
    (net (code "55") (name "/INJ8-Mosfet") (class "Default")
      (node (ref "R11") (pin "2") (pinfunction "2_2") (pintype "unspecified"))
      (node (ref "U4") (pin "12") (pinfunction "Y7_12") (pintype "unspecified"))
    )
    (net (code "56") (name "/INJ8-OUT") (class "Default")
      (node (ref "CN4") (pin "33") (pinfunction "33_33") (pintype "unspecified"))
      (node (ref "D1") (pin "2") (pinfunction "A_2") (pintype "unspecified"))
      (node (ref "Q10") (pin "2") (pinfunction "D_2") (pintype "unspecified"))
    )
    (net (code "57") (name "/MAP-IN-A3") (class "Default")
      (node (ref "C16") (pin "1") (pinfunction "1_1") (pintype "input"))
      (node (ref "CN1") (pin "20") (pinfunction "20_20") (pintype "unspecified"))
      (node (ref "R135") (pin "2") (pinfunction "2_2") (pintype "unspecified"))
    )
    (net (code "58") (name "/O2-IN-A8") (class "Default")
      (node (ref "C9") (pin "1") (pinfunction "1_1") (pintype "input"))
      (node (ref "CN1") (pin "19") (pinfunction "19_19") (pintype "unspecified"))
      (node (ref "R21") (pin "2") (pinfunction "2_2") (pintype "unspecified"))
    )
    (net (code "59") (name "/RTS") (class "Default")
      (node (ref "3") (pin "3") (pinfunction "E_3") (pintype "bidirectional"))
      (node (ref "IC1") (pin "14") (pinfunction "RXD_14") (pintype "unspecified"))
      (node (ref "R68") (pin "2") (pinfunction "2_2") (pintype "unspecified"))
    )
    (net (code "60") (name "/SDCS") (class "Default")
      (node (ref "MICROSD1") (pin "2") (pinfunction "CD/DAT3_2") (pintype "unspecified"))
      (node (ref "R166") (pin "1") (pinfunction "1_1") (pintype "unspecified"))
    )
    (net (code "61") (name "/SPI3CLK") (class "Default")
      (node (ref "MICROSD1") (pin "5") (pinfunction "CLK_5") (pintype "unspecified"))
      (node (ref "R164") (pin "1") (pinfunction "1_1") (pintype "unspecified"))
    )
    (net (code "62") (name "/SPI3MISO") (class "Default")
      (node (ref "MICROSD1") (pin "7") (pinfunction "DAT0_7") (pintype "unspecified"))
      (node (ref "R163") (pin "1") (pinfunction "1_1") (pintype "unspecified"))
    )
    (net (code "63") (name "/SPI3MOSI") (class "Default")
      (node (ref "MICROSD1") (pin "3") (pinfunction "CMD_3") (pintype "unspecified"))
      (node (ref "R165") (pin "1") (pinfunction "1_1") (pintype "unspecified"))
    )
    (net (code "64") (name "/STP-OUT-A1-A") (class "Default")
      (node (ref "CN4") (pin "9") (pinfunction "9_9") (pintype "unspecified"))
      (node (ref "U56") (pin "5") (pinfunction "AOUT1_5") (pintype "unspecified"))
    )
    (net (code "65") (name "/STP-OUT-A2-D") (class "Default")
      (node (ref "CN4") (pin "11") (pinfunction "11_11") (pintype "unspecified"))
      (node (ref "U56") (pin "7") (pinfunction "AOUT2_7") (pintype "unspecified"))
    )
    (net (code "66") (name "/STP-OUT-B1-B") (class "Default")
      (node (ref "CN4") (pin "15") (pinfunction "15_15") (pintype "unspecified"))
      (node (ref "U56") (pin "10") (pinfunction "BOUT1_10") (pintype "unspecified"))
    )
    (net (code "67") (name "/STP-OUT-B2-C") (class "Default")
      (node (ref "CN4") (pin "13") (pinfunction "13_13") (pintype "unspecified"))
      (node (ref "U56") (pin "8") (pinfunction "BOUT2_8") (pintype "unspecified"))
    )
    (net (code "68") (name "/TACHO-OUT-D49") (class "Default")
      (node (ref "CN4") (pin "1") (pinfunction "1_1") (pintype "unspecified"))
      (node (ref "R52") (pin "2") (pinfunction "2_2") (pintype "unspecified"))
      (node (ref "U3") (pin "17") (pinfunction "Output_17") (pintype "unspecified"))
      (node (ref "U3") (pin "18") (pinfunction "Output_18") (pintype "unspecified"))
    )
    (net (code "69") (name "/TACHO-ULN-D49") (class "Default")
      (node (ref "U3") (pin "1") (pinfunction "Input_1") (pintype "unspecified"))
      (node (ref "U3") (pin "2") (pinfunction "Input_2") (pintype "unspecified"))
      (node (ref "U7") (pin "12") (pinfunction "Y7_12") (pintype "unspecified"))
    )
    (net (code "70") (name "/TPS-IN-A2") (class "Default")
      (node (ref "C1") (pin "1") (pinfunction "1_1") (pintype "input"))
      (node (ref "CN1") (pin "21") (pinfunction "21_21") (pintype "unspecified"))
      (node (ref "R6") (pin "2") (pinfunction "2_2") (pintype "unspecified"))
    )
    (net (code "71") (name "/USB-Pwr") (class "Default")
      (node (ref "D12") (pin "4") (pinfunction "4_4") (pintype "input"))
      (node (ref "U32") (pin "4") (pinfunction "4_4") (pintype "unspecified"))
      (node (ref "U41") (pin "2") (pinfunction "A_2") (pintype "unspecified"))
      (node (ref "USB1") (pin "1") (pinfunction "VCC_1") (pintype "input"))
    )
    (net (code "72") (name "/USBD+") (class "Default")
      (node (ref "D12") (pin "3") (pinfunction "3_3") (pintype "input"))
      (node (ref "IC1") (pin "5") (pinfunction "DCD_5") (pintype "unspecified"))
      (node (ref "R119") (pin "2") (pinfunction "2_2") (pintype "unspecified"))
    )
    (net (code "73") (name "/USBD-") (class "Default")
      (node (ref "D12") (pin "2") (pinfunction "2_2") (pintype "input"))
      (node (ref "IC1") (pin "6") (pinfunction "RI_6") (pintype "unspecified"))
      (node (ref "R118") (pin "2") (pinfunction "2_2") (pintype "unspecified"))
    )
    (net (code "74") (name "/VSS-IN-D3") (class "Default")
      (node (ref "CN1") (pin "1") (pinfunction "1_1") (pintype "unspecified"))
      (node (ref "R26") (pin "1") (pinfunction "1_1") (pintype "unspecified"))
    )
    (net (code "75") (name "/VVT-MOS-D4") (class "Default")
      (node (ref "R90") (pin "2") (pinfunction "2_2") (pintype "unspecified"))
      (node (ref "U7") (pin "17") (pinfunction "Y2_17") (pintype "unspecified"))
    )
    (net (code "76") (name "/VVT-OUT-D4") (class "Default")
      (node (ref "CN4") (pin "14") (pinfunction "14_14") (pintype "unspecified"))
      (node (ref "D29") (pin "2") (pinfunction "A_2") (pintype "unspecified"))
      (node (ref "Q18") (pin "2") (pinfunction "D_2") (pintype "unspecified"))
    )
    (net (code "77") (name "/VVT2-MOS-D28") (class "Default")
      (node (ref "R93") (pin "2") (pinfunction "2_2") (pintype "unspecified"))
      (node (ref "U7") (pin "16") (pinfunction "Y3_16") (pintype "unspecified"))
    )
    (net (code "78") (name "/VVT2-OUT-D28") (class "Default")
      (node (ref "CN4") (pin "12") (pinfunction "12_12") (pintype "unspecified"))
      (node (ref "D30") (pin "2") (pinfunction "A_2") (pintype "unspecified"))
      (node (ref "Q19") (pin "2") (pinfunction "D_2") (pintype "unspecified"))
    )
    (net (code "79") (name "AC-CPU-D23") (class "Default")
      (node (ref "R116") (pin "1") (pinfunction "1_1") (pintype "unspecified"))
      (node (ref "R67") (pin "2") (pinfunction "2_2") (pintype "unspecified"))
      (node (ref "U53") (pin "65") (pinfunction "PC8_65") (pintype "unspecified"))
    )
    (net (code "80") (name "AC-IN-CPU-D22") (class "Default")
      (node (ref "D22") (pin "1") (pinfunction "K_1") (pintype "unspecified"))
      (node (ref "R56") (pin "2") (pinfunction "2_2") (pintype "unspecified"))
      (node (ref "U53") (pin "66") (pinfunction "PC9_66") (pintype "unspecified"))
    )
    (net (code "81") (name "AUX-CPU-A10") (class "Default")
      (node (ref "C21") (pin "1") (pinfunction "1_1") (pintype "input"))
      (node (ref "R140") (pin "1") (pinfunction "1_1") (pintype "unspecified"))
      (node (ref "R27") (pin "2") (pinfunction "2_2") (pintype "unspecified"))
      (node (ref "U53") (pin "15") (pinfunction "PC0_15") (pintype "unspecified"))
    )
    (net (code "82") (name "AUX-CPU-A11") (class "Default")
      (node (ref "C25") (pin "1") (pinfunction "1_1") (pintype "input"))
      (node (ref "R139") (pin "1") (pinfunction "1_1") (pintype "unspecified"))
      (node (ref "R23") (pin "2") (pinfunction "2_2") (pintype "unspecified"))
      (node (ref "U53") (pin "16") (pinfunction "PC1_16") (pintype "unspecified"))
    )
    (net (code "83") (name "AUX-CPU-A12") (class "Default")
      (node (ref "C18") (pin "1") (pinfunction "1_1") (pintype "input"))
      (node (ref "R107") (pin "2") (pinfunction "2_2") (pintype "unspecified"))
      (node (ref "R88") (pin "1") (pinfunction "1_1") (pintype "unspecified"))
      (node (ref "U53") (pin "17") (pinfunction "PC2_17") (pintype "unspecified"))
    )
    (net (code "84") (name "AUX-CPU-D30") (class "Default")
      (node (ref "D18") (pin "1") (pinfunction "K_1") (pintype "unspecified"))
      (node (ref "R25") (pin "2") (pinfunction "2_2") (pintype "unspecified"))
      (node (ref "U53") (pin "61") (pinfunction "PD14_61") (pintype "unspecified"))
    )
    (net (code "85") (name "AUX-CPU-D31") (class "Default")
      (node (ref "R42") (pin "2") (pinfunction "2_2") (pintype "unspecified"))
      (node (ref "R73") (pin "1") (pinfunction "1_1") (pintype "unspecified"))
      (node (ref "U53") (pin "62") (pinfunction "PD15_62") (pintype "unspecified"))
    )
    (net (code "86") (name "AUX-CPU-D33") (class "Default")
      (node (ref "D20") (pin "1") (pinfunction "K_1") (pintype "unspecified"))
      (node (ref "R46") (pin "2") (pinfunction "2_2") (pintype "unspecified"))
      (node (ref "U53") (pin "60") (pinfunction "PD13_60") (pintype "unspecified"))
    )
    (net (code "87") (name "AUX-CPU-D43") (class "Default")
      (node (ref "R117") (pin "2") (pinfunction "2_2") (pintype "unspecified"))
      (node (ref "U53") (pin "93") (pinfunction "PB7_93") (pintype "unspecified"))
    )
    (net (code "88") (name "BARO-CPU-A5") (class "Default")
      (node (ref "C27") (pin "1") (pinfunction "1_1") (pintype "input"))
      (node (ref "C34") (pin "1") (pinfunction "1_1") (pintype "input"))
      (node (ref "D19") (pin "6") (pinfunction "IN_6") (pintype "unspecified"))
      (node (ref "R148") (pin "1") (pinfunction "1_1") (pintype "unspecified"))
      (node (ref "R49") (pin "1") (pinfunction "1_1") (pintype "unspecified"))
      (node (ref "U53") (pin "30") (pinfunction "PA5_30") (pintype "unspecified"))
    )
    (net (code "89") (name "BATTRY-CPU-A4") (class "Default")
      (node (ref "C8") (pin "1") (pinfunction "1_1") (pintype "input"))
      (node (ref "D19") (pin "5") (pinfunction "IN_5") (pintype "unspecified"))
      (node (ref "R58") (pin "1") (pinfunction "1_1") (pintype "unspecified"))
      (node (ref "U53") (pin "29") (pinfunction "PA4_29") (pintype "unspecified"))
    )
    (net (code "90") (name "BOOST-CPU-D7") (class "Default")
      (node (ref "R63") (pin "2") (pinfunction "2_2") (pintype "unspecified"))
      (node (ref "R69") (pin "1") (pinfunction "1_1") (pintype "unspecified"))
      (node (ref "U53") (pin "55") (pinfunction "PD8_55") (pintype "unspecified"))
    )
    (net (code "91") (name "Boot0") (class "Default")
      (node (ref "4") (pin "2") (pinfunction "C_2") (pintype "bidirectional"))
      (node (ref "C23") (pin "1") (pinfunction "1_1") (pintype "input"))
      (node (ref "R64") (pin "2") (pinfunction "2_2") (pintype "unspecified"))
      (node (ref "SW4") (pin "2") (pinfunction "B1_2") (pintype "input"))
      (node (ref "U53") (pin "94") (pinfunction "BOOT0_94") (pintype "unspecified"))
    )
    (net (code "92") (name "Boot1") (class "Default")
      (node (ref "R120") (pin "2") (pinfunction "2_2") (pintype "unspecified"))
      (node (ref "U53") (pin "37") (pinfunction "PB2_37") (pintype "unspecified"))
    )
    (net (code "93") (name "CAM-CPU-D18") (class "Default")
      (node (ref "D19") (pin "2") (pinfunction "IN_2") (pintype "unspecified"))
      (node (ref "R157") (pin "2") (pinfunction "2_2") (pintype "unspecified"))
      (node (ref "R51") (pin "1") (pinfunction "1_1") (pintype "unspecified"))
      (node (ref "R62") (pin "1") (pinfunction "1_1") (pintype "unspecified"))
      (node (ref "U5") (pin "7") (pinfunction "OUTB_7") (pintype "unspecified"))
      (node (ref "U53") (pin "85") (pinfunction "PD4_85") (pintype "unspecified"))
    )
    (net (code "94") (name "CANH") (class "Default")
      (node (ref "CN1") (pin "9") (pinfunction "9_9") (pintype "unspecified"))
      (node (ref "U52") (pin "7") (pinfunction "CANH_7") (pintype "unspecified"))
    )
    (net (code "95") (name "CANL") (class "Default")
      (node (ref "CN1") (pin "10") (pinfunction "10_10") (pintype "unspecified"))
      (node (ref "U52") (pin "6") (pinfunction "CANL_6") (pintype "unspecified"))
    )
    (net (code "96") (name "CLT-CPU-A1") (class "Default")
      (node (ref "C6") (pin "1") (pinfunction "1_1") (pintype "input"))
      (node (ref "D19") (pin "11") (pinfunction "IN_11") (pintype "unspecified"))
      (node (ref "R136") (pin "1") (pinfunction "1_1") (pintype "unspecified"))
      (node (ref "R22") (pin "1") (pinfunction "1_1") (pintype "unspecified"))
      (node (ref "U53") (pin "24") (pinfunction "PA1_24") (pintype "unspecified"))
    )
    (net (code "97") (name "CLUCH-CPU-D51") (class "Default")
      (node (ref "D21") (pin "1") (pinfunction "K_1") (pintype "unspecified"))
      (node (ref "R48") (pin "2") (pinfunction "2_2") (pintype "unspecified"))
      (node (ref "U53") (pin "95") (pinfunction "PB8_95") (pintype "unspecified"))
    )
    (net (code "98") (name "CRANK-CPU-D19") (class "Default")
      (node (ref "D19") (pin "1") (pinfunction "IN_1") (pintype "unspecified"))
      (node (ref "R154") (pin "1") (pinfunction "1_1") (pintype "unspecified"))
      (node (ref "R155") (pin "2") (pinfunction "2_2") (pintype "unspecified"))
      (node (ref "U5") (pin "1") (pinfunction "OUTA_1") (pintype "unspecified"))
      (node (ref "U53") (pin "84") (pinfunction "PD3_84") (pintype "unspecified"))
    )
    (net (code "99") (name "FAN-CPU-D47") (class "Default")
      (node (ref "R43") (pin "2") (pinfunction "2_2") (pintype "unspecified"))
      (node (ref "R86") (pin "1") (pinfunction "1_1") (pintype "unspecified"))
      (node (ref "U53") (pin "40") (pinfunction "PE9_40") (pintype "unspecified"))
    )
    (net (code "100") (name "FULE-CPU-D45") (class "Default")
      (node (ref "R114") (pin "1") (pinfunction "1_1") (pintype "unspecified"))
      (node (ref "R54") (pin "2") (pinfunction "2_2") (pintype "unspecified"))
      (node (ref "U53") (pin "42") (pinfunction "PE11_42") (pintype "unspecified"))
    )
    (net (code "101") (name "Flash CS") (class "Default")
      (node (ref "U53") (pin "98") (pinfunction "PE1_98") (pintype "unspecified"))
    )
    (net (code "102") (name "Flex-CPU-D2") (class "Default")
      (node (ref "D19") (pin "15") (pinfunction "IN_15") (pintype "unspecified"))
      (node (ref "D24") (pin "1") (pinfunction "K_1") (pintype "unspecified"))
      (node (ref "R36") (pin "2") (pinfunction "2_2") (pintype "unspecified"))
      (node (ref "U53") (pin "88") (pinfunction "PD7_88") (pintype "unspecified"))
    )
    (net (code "103") (name "GND") (class "Default")
      (node (ref "C1") (pin "2") (pinfunction "2_2") (pintype "input"))
      (node (ref "C10") (pin "2") (pinfunction "2_2") (pintype "input"))
      (node (ref "C11") (pin "2") (pinfunction "2_2") (pintype "input"))
      (node (ref "C12") (pin "2") (pinfunction "2_2") (pintype "input"))
      (node (ref "C13") (pin "2") (pinfunction "2_2") (pintype "input"))
      (node (ref "C14") (pin "2") (pinfunction "2_2") (pintype "input"))
      (node (ref "C15") (pin "2") (pinfunction "2_2") (pintype "input"))
      (node (ref "C16") (pin "2") (pinfunction "2_2") (pintype "input"))
      (node (ref "C17") (pin "2") (pinfunction "2_2") (pintype "input"))
      (node (ref "C18") (pin "2") (pinfunction "2_2") (pintype "input"))
      (node (ref "C19") (pin "2") (pinfunction "2_2") (pintype "input"))
      (node (ref "C2") (pin "2") (pinfunction "2_2") (pintype "input"))
      (node (ref "C20") (pin "2") (pinfunction "2_2") (pintype "input"))
      (node (ref "C21") (pin "2") (pinfunction "2_2") (pintype "input"))
      (node (ref "C22") (pin "2") (pinfunction "2_2") (pintype "input"))
      (node (ref "C24") (pin "2") (pinfunction "2_2") (pintype "input"))
      (node (ref "C25") (pin "2") (pinfunction "2_2") (pintype "input"))
      (node (ref "C26") (pin "2") (pinfunction "2_2") (pintype "input"))
      (node (ref "C27") (pin "2") (pinfunction "2_2") (pintype "input"))
      (node (ref "C29") (pin "1") (pinfunction "1_1") (pintype "input"))
      (node (ref "C3") (pin "2") (pinfunction "2_2") (pintype "input"))
      (node (ref "C30") (pin "2") (pinfunction "2_2") (pintype "input"))
      (node (ref "C31") (pin "2") (pinfunction "2_2") (pintype "unspecified"))
      (node (ref "C32") (pin "2") (pinfunction "2_2") (pintype "input"))
      (node (ref "C33") (pin "2") (pinfunction "2_2") (pintype "input"))
      (node (ref "C34") (pin "2") (pinfunction "2_2") (pintype "input"))
      (node (ref "C35") (pin "1") (pinfunction "1_1") (pintype "input"))
      (node (ref "C37") (pin "2") (pinfunction "2_2") (pintype "input"))
      (node (ref "C38") (pin "1") (pinfunction "1_1") (pintype "input"))
      (node (ref "C39") (pin "1") (pinfunction "1_1") (pintype "input"))
      (node (ref "C4") (pin "2") (pinfunction "2_2") (pintype "input"))
      (node (ref "C40") (pin "1") (pinfunction "1_1") (pintype "input"))
      (node (ref "C41") (pin "2") (pinfunction "2_2") (pintype "input"))
      (node (ref "C42") (pin "2") (pinfunction "2_2") (pintype "input"))
      (node (ref "C44") (pin "1") (pinfunction "1_1") (pintype "input"))
      (node (ref "C45") (pin "1") (pinfunction "1_1") (pintype "input"))
      (node (ref "C47") (pin "2") (pinfunction "2_2") (pintype "input"))
      (node (ref "C49") (pin "2") (pinfunction "2_2") (pintype "unspecified"))
      (node (ref "C5") (pin "2") (pinfunction "2_2") (pintype "input"))
      (node (ref "C50") (pin "2") (pinfunction "2_2") (pintype "input"))
      (node (ref "C51") (pin "2") (pinfunction "2_2") (pintype "input"))
      (node (ref "C52") (pin "2") (pinfunction "2_2") (pintype "input"))
      (node (ref "C53") (pin "2") (pinfunction "2_2") (pintype "input"))
      (node (ref "C54") (pin "2") (pinfunction "2_2") (pintype "input"))
      (node (ref "C56") (pin "1") (pinfunction "1_1") (pintype "input"))
      (node (ref "C57") (pin "2") (pinfunction "2_2") (pintype "input"))
      (node (ref "C59") (pin "1") (pinfunction "1_1") (pintype "input"))
      (node (ref "C6") (pin "2") (pinfunction "2_2") (pintype "input"))
      (node (ref "C60") (pin "1") (pinfunction "1_1") (pintype "input"))
      (node (ref "C61") (pin "1") (pinfunction "1_1") (pintype "input"))
      (node (ref "C63") (pin "2") (pinfunction "2_2") (pintype "unspecified"))
      (node (ref "C65") (pin "2") (pinfunction "2_2") (pintype "input"))
      (node (ref "C66") (pin "1") (pinfunction "1_1") (pintype "input"))
      (node (ref "C67") (pin "2") (pinfunction "2_2") (pintype "input"))
      (node (ref "C69") (pin "1") (pinfunction "1_1") (pintype "unspecified"))
      (node (ref "C7") (pin "2") (pinfunction "2_2") (pintype "input"))
      (node (ref "C70") (pin "2") (pinfunction "2_2") (pintype "unspecified"))
      (node (ref "C71") (pin "2") (pinfunction "2_2") (pintype "unspecified"))
      (node (ref "C72") (pin "2") (pinfunction "2_2") (pintype "unspecified"))
      (node (ref "C73") (pin "2") (pinfunction "2_2") (pintype "unspecified"))
      (node (ref "C74") (pin "2") (pinfunction "2_2") (pintype "input"))
      (node (ref "C75") (pin "2") (pinfunction "2_2") (pintype "input"))
      (node (ref "C8") (pin "2") (pinfunction "2_2") (pintype "input"))
      (node (ref "C9") (pin "2") (pinfunction "2_2") (pintype "input"))
      (node (ref "CN1") (pin "11") (pinfunction "11_11") (pintype "unspecified"))
      (node (ref "CN1") (pin "12") (pinfunction "12_12") (pintype "unspecified"))
      (node (ref "CN1") (pin "24") (pinfunction "24_24") (pintype "unspecified"))
      (node (ref "CN2") (pin "4") (pinfunction "4_4") (pintype "unspecified"))
      (node (ref "CN4") (pin "17") (pinfunction "17_17") (pintype "unspecified"))
      (node (ref "CN4") (pin "18") (pinfunction "18_18") (pintype "unspecified"))
      (node (ref "D12") (pin "1") (pinfunction "1_1") (pintype "input"))
      (node (ref "D15") (pin "2") (pinfunction "A_2") (pintype "unspecified"))
      (node (ref "D18") (pin "2") (pinfunction "A_2") (pintype "unspecified"))
      (node (ref "D19") (pin "8") (pinfunction "V-_8") (pintype "unspecified"))
      (node (ref "D2") (pin "2") (pinfunction "A_2") (pintype "unspecified"))
      (node (ref "D20") (pin "2") (pinfunction "A_2") (pintype "unspecified"))
      (node (ref "D21") (pin "2") (pinfunction "A_2") (pintype "unspecified"))
      (node (ref "D22") (pin "2") (pinfunction "A_2") (pintype "unspecified"))
      (node (ref "D23") (pin "2") (pinfunction "A_2") (pintype "unspecified"))
      (node (ref "D24") (pin "2") (pinfunction "A_2") (pintype "unspecified"))
      (node (ref "IC1") (pin "1") (pinfunction "GND_1") (pintype "unspecified"))
      (node (ref "MICROSD1") (pin "6") (pinfunction "VSS_6") (pintype "unspecified"))
      (node (ref "Q10") (pin "3") (pinfunction "S_3") (pintype "unspecified"))
      (node (ref "Q11") (pin "3") (pinfunction "S_3") (pintype "unspecified"))
      (node (ref "Q12") (pin "3") (pinfunction "S_3") (pintype "unspecified"))
      (node (ref "Q13") (pin "3") (pinfunction "S_3") (pintype "unspecified"))
      (node (ref "Q14") (pin "3") (pinfunction "S_3") (pintype "unspecified"))
      (node (ref "Q15") (pin "3") (pinfunction "S_3") (pintype "unspecified"))
      (node (ref "Q16") (pin "3") (pinfunction "S_3") (pintype "unspecified"))
      (node (ref "Q17") (pin "3") (pinfunction "S_3") (pintype "unspecified"))
      (node (ref "Q18") (pin "3") (pinfunction "S_3") (pintype "unspecified"))
      (node (ref "Q19") (pin "3") (pinfunction "S_3") (pintype "unspecified"))
      (node (ref "Q20") (pin "3") (pinfunction "S_3") (pintype "unspecified"))
      (node (ref "Q9") (pin "3") (pinfunction "S_3") (pintype "unspecified"))
      (node (ref "R101") (pin "1") (pinfunction "1_1") (pintype "unspecified"))
      (node (ref "R102") (pin "1") (pinfunction "1_1") (pintype "unspecified"))
      (node (ref "R103") (pin "2") (pinfunction "2_2") (pintype "unspecified"))
      (node (ref "R104") (pin "1") (pinfunction "1_1") (pintype "unspecified"))
      (node (ref "R106") (pin "1") (pinfunction "1_1") (pintype "unspecified"))
      (node (ref "R108") (pin "1") (pinfunction "1_1") (pintype "unspecified"))
      (node (ref "R110") (pin "1") (pinfunction "1_1") (pintype "unspecified"))
      (node (ref "R111") (pin "1") (pinfunction "1_1") (pintype "unspecified"))
      (node (ref "R112") (pin "1") (pinfunction "1_1") (pintype "unspecified"))
      (node (ref "R120") (pin "1") (pinfunction "1_1") (pintype "unspecified"))
      (node (ref "R121") (pin "2") (pinfunction "2_2") (pintype "unspecified"))
      (node (ref "R131") (pin "1") (pinfunction "1_1") (pintype "unspecified"))
      (node (ref "R132") (pin "1") (pinfunction "1_1") (pintype "unspecified"))
      (node (ref "R133") (pin "1") (pinfunction "1_1") (pintype "unspecified"))
      (node (ref "R134") (pin "2") (pinfunction "2_2") (pintype "unspecified"))
      (node (ref "R136") (pin "2") (pinfunction "2_2") (pintype "unspecified"))
      (node (ref "R137") (pin "2") (pinfunction "2_2") (pintype "unspecified"))
      (node (ref "R138") (pin "2") (pinfunction "2_2") (pintype "unspecified"))
      (node (ref "R139") (pin "2") (pinfunction "2_2") (pintype "unspecified"))
      (node (ref "R140") (pin "2") (pinfunction "2_2") (pintype "unspecified"))
      (node (ref "R141") (pin "2") (pinfunction "2_2") (pintype "unspecified"))
      (node (ref "R152") (pin "2") (pinfunction "2_2") (pintype "unspecified"))
      (node (ref "R168") (pin "1") (pinfunction "1_1") (pintype "unspecified"))
      (node (ref "R169") (pin "2") (pinfunction "2_2") (pintype "unspecified"))
      (node (ref "R180") (pin "1") (pinfunction "1_1") (pintype "unspecified"))
      (node (ref "R181") (pin "1") (pinfunction "1_1") (pintype "unspecified"))
      (node (ref "R182") (pin "1") (pinfunction "1_1") (pintype "unspecified"))
      (node (ref "R183") (pin "1") (pinfunction "1_1") (pintype "unspecified"))
      (node (ref "R184") (pin "1") (pinfunction "1_1") (pintype "unspecified"))
      (node (ref "R185") (pin "1") (pinfunction "1_1") (pintype "unspecified"))
      (node (ref "R186") (pin "1") (pinfunction "1_1") (pintype "unspecified"))
      (node (ref "R187") (pin "1") (pinfunction "1_1") (pintype "unspecified"))
      (node (ref "R29") (pin "2") (pinfunction "2_2") (pintype "unspecified"))
      (node (ref "R41") (pin "1") (pinfunction "1_1") (pintype "unspecified"))
      (node (ref "R42") (pin "1") (pinfunction "1_1") (pintype "unspecified"))
      (node (ref "R43") (pin "1") (pinfunction "1_1") (pintype "unspecified"))
      (node (ref "R49") (pin "2") (pinfunction "2_2") (pintype "unspecified"))
      (node (ref "R54") (pin "1") (pinfunction "1_1") (pintype "unspecified"))
      (node (ref "R57") (pin "1") (pinfunction "1_1") (pintype "unspecified"))
      (node (ref "R63") (pin "1") (pinfunction "1_1") (pintype "unspecified"))
      (node (ref "R64") (pin "1") (pinfunction "1_1") (pintype "unspecified"))
      (node (ref "R65") (pin "1") (pinfunction "1_1") (pintype "unspecified"))
      (node (ref "R67") (pin "1") (pinfunction "1_1") (pintype "unspecified"))
      (node (ref "R79") (pin "1") (pinfunction "1_1") (pintype "unspecified"))
      (node (ref "R8") (pin "1") (pinfunction "1_1") (pintype "unspecified"))
      (node (ref "R80") (pin "1") (pinfunction "1_1") (pintype "unspecified"))
      (node (ref "R87") (pin "2") (pinfunction "2_2") (pintype "unspecified"))
      (node (ref "R88") (pin "2") (pinfunction "2_2") (pintype "unspecified"))
      (node (ref "R91") (pin "2") (pinfunction "2_2") (pintype "unspecified"))
      (node (ref "SW3") (pin "1") (pinfunction "A1_1") (pintype "input"))
      (node (ref "U10") (pin "1") (pinfunction "K_1") (pintype "unspecified"))
      (node (ref "U11") (pin "1") (pinfunction "K_1") (pintype "unspecified"))
      (node (ref "U12") (pin "1") (pinfunction "K_1") (pintype "unspecified"))
      (node (ref "U14") (pin "1") (pinfunction "K_1") (pintype "unspecified"))
      (node (ref "U16") (pin "1") (pinfunction "K_1") (pintype "unspecified"))
      (node (ref "U17") (pin "1") (pinfunction "K_1") (pintype "unspecified"))
      (node (ref "U18") (pin "1") (pinfunction "K_1") (pintype "unspecified"))
      (node (ref "U19") (pin "1") (pinfunction "K_1") (pintype "unspecified"))
      (node (ref "U2") (pin "1") (pinfunction "1_1") (pintype "unspecified"))
      (node (ref "U20") (pin "1") (pinfunction "K_1") (pintype "unspecified"))
      (node (ref "U21") (pin "1") (pinfunction "K_1") (pintype "unspecified"))
      (node (ref "U22") (pin "1") (pinfunction "K_1") (pintype "unspecified"))
      (node (ref "U23") (pin "1") (pinfunction "K_1") (pintype "unspecified"))
      (node (ref "U24") (pin "1") (pinfunction "K_1") (pintype "unspecified"))
      (node (ref "U25") (pin "1") (pinfunction "K_1") (pintype "unspecified"))
      (node (ref "U26") (pin "1") (pinfunction "K_1") (pintype "unspecified"))
      (node (ref "U27") (pin "1") (pinfunction "K_1") (pintype "unspecified"))
      (node (ref "U28") (pin "1") (pinfunction "K_1") (pintype "unspecified"))
      (node (ref "U29") (pin "1") (pinfunction "K_1") (pintype "unspecified"))
      (node (ref "U3") (pin "9") (pinfunction "GND_9") (pintype "unspecified"))
      (node (ref "U32") (pin "1") (pinfunction "1_1") (pintype "unspecified"))
      (node (ref "U36") (pin "1") (pinfunction "1_1") (pintype "unspecified"))
      (node (ref "U37") (pin "2") (pinfunction "GND_2") (pintype "unspecified"))
      (node (ref "U39") (pin "3") (pinfunction "GND_3") (pintype "unspecified"))
      (node (ref "U39") (pin "5") (pinfunction "ON#/OFF_5") (pintype "unspecified"))
      (node (ref "U39") (pin "6") (pinfunction "GND_6") (pintype "unspecified"))
      (node (ref "U4") (pin "1") (pinfunction "OE1#_1") (pintype "unspecified"))
      (node (ref "U4") (pin "10") (pinfunction "GND_10") (pintype "unspecified"))
      (node (ref "U4") (pin "19") (pinfunction "OE2#_19") (pintype "unspecified"))
      (node (ref "U40") (pin "2") (pinfunction "A_2") (pintype "unspecified"))
      (node (ref "U42") (pin "1") (pinfunction "OE1#_1") (pintype "unspecified"))
      (node (ref "U42") (pin "10") (pinfunction "GND_10") (pintype "unspecified"))
      (node (ref "U42") (pin "19") (pinfunction "OE2#_19") (pintype "unspecified"))
      (node (ref "U5") (pin "4") (pinfunction "GND_4") (pintype "unspecified"))
      (node (ref "U52") (pin "2") (pinfunction "VSS_2") (pintype "unspecified"))
      (node (ref "U53") (pin "10") (pinfunction "VSS_10") (pintype "unspecified"))
      (node (ref "U53") (pin "20") (pinfunction "VSSA_20") (pintype "unspecified"))
      (node (ref "U53") (pin "27") (pinfunction "VSS_27") (pintype "unspecified"))
      (node (ref "U53") (pin "74") (pinfunction "VSS_74") (pintype "unspecified"))
      (node (ref "U53") (pin "99") (pinfunction "VSS_99") (pintype "unspecified"))
      (node (ref "U56") (pin "14") (pinfunction "GND_14") (pintype "unspecified"))
      (node (ref "U56") (pin "24") (pinfunction "MODE0_24") (pintype "unspecified"))
      (node (ref "U56") (pin "25") (pinfunction "MODE1_25") (pintype "unspecified"))
      (node (ref "U56") (pin "26") (pinfunction "MODE2_26") (pintype "unspecified"))
      (node (ref "U56") (pin "28") (pinfunction "GND_28") (pintype "unspecified"))
      (node (ref "U56") (pin "29") (pinfunction "EP_29") (pintype "unspecified"))
      (node (ref "U57") (pin "3") (pinfunction "3_3") (pintype "input"))
      (node (ref "U6") (pin "3") (pinfunction "GND_3") (pintype "passive"))
      (node (ref "U62") (pin "2") (pinfunction "A_2") (pintype "unspecified"))
      (node (ref "U63") (pin "3") (pinfunction "GND_3") (pintype "unspecified"))
      (node (ref "U63") (pin "5") (pinfunction "ON#/OFF_5") (pintype "unspecified"))
      (node (ref "U63") (pin "6") (pinfunction "GND_6") (pintype "unspecified"))
      (node (ref "U7") (pin "1") (pinfunction "OE1#_1") (pintype "unspecified"))
      (node (ref "U7") (pin "10") (pinfunction "GND_10") (pintype "unspecified"))
      (node (ref "U7") (pin "19") (pinfunction "OE2#_19") (pintype "unspecified"))
      (node (ref "U8") (pin "9") (pinfunction "GND_9") (pintype "unspecified"))
      (node (ref "U9") (pin "1") (pinfunction "K_1") (pintype "unspecified"))
      (node (ref "USB1") (pin "4") (pinfunction "GND_4") (pintype "input"))
      (node (ref "USB1") (pin "5") (pinfunction "SH1_5") (pintype "unspecified"))
      (node (ref "USB1") (pin "6") (pinfunction "SH2_6") (pintype "unspecified"))
    )
    (net (code "104") (name "IAT-CPU-A0") (class "Default")
      (node (ref "C4") (pin "1") (pinfunction "1_1") (pintype "input"))
      (node (ref "D19") (pin "12") (pinfunction "IN_12") (pintype "unspecified"))
      (node (ref "R137") (pin "1") (pinfunction "1_1") (pintype "unspecified"))
      (node (ref "R2") (pin "1") (pinfunction "1_1") (pintype "unspecified"))
      (node (ref "U53") (pin "23") (pinfunction "PA0_23") (pintype "unspecified"))
    )
    (net (code "105") (name "ICUSBD+") (class "Default")
      (node (ref "R77") (pin "1") (pinfunction "1_1") (pintype "unspecified"))
      (node (ref "U53") (pin "71") (pinfunction "PA12_71") (pintype "unspecified"))
    )
    (net (code "106") (name "ICUSBD-") (class "Default")
      (node (ref "R78") (pin "1") (pinfunction "1_1") (pintype "unspecified"))
      (node (ref "U53") (pin "70") (pinfunction "PA11_70") (pintype "unspecified"))
    )
    (net (code "107") (name "IDLE1-CPU-D5") (class "Default")
      (node (ref "U3") (pin "5") (pinfunction "Input_5") (pintype "unspecified"))
      (node (ref "U3") (pin "6") (pinfunction "Input_6") (pintype "unspecified"))
      (node (ref "U53") (pin "57") (pinfunction "PD10_57") (pintype "unspecified"))
    )
    (net (code "108") (name "IDLE2-CPU-D6") (class "Default")
      (node (ref "U3") (pin "7") (pinfunction "Input_7") (pintype "unspecified"))
      (node (ref "U3") (pin "8") (pinfunction "Input_8") (pintype "unspecified"))
      (node (ref "U53") (pin "56") (pinfunction "PD9_56") (pintype "unspecified"))
    )
    (net (code "109") (name "IGN1-CPU-D40") (class "Default")
      (node (ref "R177") (pin "1") (pinfunction "1_1") (pintype "unspecified"))
      (node (ref "R187") (pin "2") (pinfunction "2_2") (pintype "unspecified"))
      (node (ref "U53") (pin "1") (pinfunction "PE2_1") (pintype "unspecified"))
    )
    (net (code "110") (name "IGN2-CPU-D38") (class "Default")
      (node (ref "R176") (pin "1") (pinfunction "1_1") (pintype "unspecified"))
      (node (ref "R186") (pin "2") (pinfunction "2_2") (pintype "unspecified"))
      (node (ref "U53") (pin "2") (pinfunction "PE3_2") (pintype "unspecified"))
    )
    (net (code "111") (name "IGN3-CPU-D52") (class "Default")
      (node (ref "R180") (pin "2") (pinfunction "2_2") (pintype "unspecified"))
      (node (ref "R82") (pin "1") (pinfunction "1_1") (pintype "unspecified"))
      (node (ref "U53") (pin "7") (pinfunction "PC13_7") (pintype "unspecified"))
    )
    (net (code "112") (name "IGN4-CPU-D48") (class "Default")
      (node (ref "R181") (pin "2") (pinfunction "2_2") (pintype "unspecified"))
      (node (ref "R83") (pin "1") (pinfunction "1_1") (pintype "unspecified"))
      (node (ref "U53") (pin "5") (pinfunction "PE6_5") (pintype "unspecified"))
    )
    (net (code "113") (name "IGN5-CPU-D36") (class "Default")
      (node (ref "R129") (pin "1") (pinfunction "1_1") (pintype "unspecified"))
      (node (ref "R185") (pin "2") (pinfunction "2_2") (pintype "unspecified"))
      (node (ref "U53") (pin "3") (pinfunction "PE4_3") (pintype "unspecified"))
    )
    (net (code "114") (name "IGN6-CPU-D34") (class "Default")
      (node (ref "R184") (pin "2") (pinfunction "2_2") (pintype "unspecified"))
      (node (ref "R84") (pin "1") (pinfunction "1_1") (pintype "unspecified"))
      (node (ref "U53") (pin "4") (pinfunction "PE5_4") (pintype "unspecified"))
    )
    (net (code "115") (name "IGN7-CPU-D46") (class "Default")
      (node (ref "R178") (pin "1") (pinfunction "1_1") (pintype "unspecified"))
      (node (ref "R183") (pin "2") (pinfunction "2_2") (pintype "unspecified"))
      (node (ref "U53") (pin "97") (pinfunction "PE0_97") (pintype "unspecified"))
    )
    (net (code "116") (name "IGN8-CPU-D53") (class "Default")
      (node (ref "R179") (pin "1") (pinfunction "1_1") (pintype "unspecified"))
      (node (ref "R182") (pin "2") (pinfunction "2_2") (pintype "unspecified"))
      (node (ref "U53") (pin "96") (pinfunction "PB9_96") (pintype "unspecified"))
    )
    (net (code "117") (name "INJ1-CPU-D8") (class "Default")
      (node (ref "R106") (pin "2") (pinfunction "2_2") (pintype "unspecified"))
      (node (ref "R99") (pin "1") (pinfunction "1_1") (pintype "unspecified"))
      (node (ref "U53") (pin "54") (pinfunction "PB15_54") (pintype "unspecified"))
    )
    (net (code "118") (name "INJ2-CPU-D9") (class "Default")
      (node (ref "R112") (pin "2") (pinfunction "2_2") (pintype "unspecified"))
      (node (ref "R98") (pin "1") (pinfunction "1_1") (pintype "unspecified"))
      (node (ref "U53") (pin "53") (pinfunction "PB14_53") (pintype "unspecified"))
    )
    (net (code "119") (name "INJ3-CPU-D10") (class "Default")
      (node (ref "R110") (pin "2") (pinfunction "2_2") (pintype "unspecified"))
      (node (ref "R96") (pin "1") (pinfunction "1_1") (pintype "unspecified"))
      (node (ref "U53") (pin "51") (pinfunction "PB12_51") (pintype "unspecified"))
    )
    (net (code "120") (name "INJ4-CPU-D11") (class "Default")
      (node (ref "R111") (pin "2") (pinfunction "2_2") (pintype "unspecified"))
      (node (ref "R97") (pin "1") (pinfunction "1_1") (pintype "unspecified"))
      (node (ref "U53") (pin "52") (pinfunction "PB13_52") (pintype "unspecified"))
    )
    (net (code "121") (name "INJ5-CPU-D12") (class "Default")
      (node (ref "R100") (pin "1") (pinfunction "1_1") (pintype "unspecified"))
      (node (ref "R104") (pin "2") (pinfunction "2_2") (pintype "unspecified"))
      (node (ref "U53") (pin "67") (pinfunction "PA8_67") (pintype "unspecified"))
    )
    (net (code "122") (name "INJ6-CPU-D50") (class "Default")
      (node (ref "R101") (pin "2") (pinfunction "2_2") (pintype "unspecified"))
      (node (ref "R92") (pin "1") (pinfunction "1_1") (pintype "unspecified"))
      (node (ref "U53") (pin "38") (pinfunction "PE7_38") (pintype "unspecified"))
    )
    (net (code "123") (name "INJ7-CPU-D39") (class "Default")
      (node (ref "R108") (pin "2") (pinfunction "2_2") (pintype "unspecified"))
      (node (ref "R95") (pin "1") (pinfunction "1_1") (pintype "unspecified"))
      (node (ref "U53") (pin "44") (pinfunction "PE13_44") (pintype "unspecified"))
    )
    (net (code "124") (name "INJ8-CPU-D42") (class "Default")
      (node (ref "R102") (pin "2") (pinfunction "2_2") (pintype "unspecified"))
      (node (ref "R94") (pin "1") (pinfunction "1_1") (pintype "unspecified"))
      (node (ref "U53") (pin "41") (pinfunction "PE10_41") (pintype "unspecified"))
    )
    (net (code "125") (name "MAP-CPU-A3") (class "Default")
      (node (ref "C12") (pin "1") (pinfunction "1_1") (pintype "input"))
      (node (ref "D19") (pin "9") (pinfunction "IN_9") (pintype "unspecified"))
      (node (ref "R134") (pin "1") (pinfunction "1_1") (pintype "unspecified"))
      (node (ref "R135") (pin "1") (pinfunction "1_1") (pintype "unspecified"))
      (node (ref "U53") (pin "26") (pinfunction "PA3_26") (pintype "unspecified"))
    )
    (net (code "126") (name "NF+5V") (class "Default")
      (node (ref "C13") (pin "1") (pinfunction "1_1") (pintype "input"))
      (node (ref "C14") (pin "1") (pinfunction "1_1") (pintype "input"))
      (node (ref "C74") (pin "1") (pinfunction "1_1") (pintype "input"))
      (node (ref "D2") (pin "1") (pinfunction "K_1") (pintype "unspecified"))
      (node (ref "R81") (pin "2") (pinfunction "2_2") (pintype "unspecified"))
      (node (ref "SW1") (pin "2") (pinfunction "2_2") (pintype "unspecified"))
      (node (ref "U1") (pin "1") (pinfunction "1_1") (pintype "unspecified"))
      (node (ref "U34") (pin "2") (pinfunction "2_2") (pintype "unspecified"))
      (node (ref "U38") (pin "2") (pinfunction "2_2") (pintype "unspecified"))
    )
    (net (code "127") (name "NF+12V") (class "Default")
      (node (ref "CN1") (pin "25") (pinfunction "25_25") (pintype "unspecified"))
      (node (ref "CN1") (pin "26") (pinfunction "26_26") (pintype "unspecified"))
      (node (ref "R7") (pin "2") (pinfunction "2_2") (pintype "unspecified"))
      (node (ref "U13") (pin "2") (pinfunction "2_2") (pintype "unspecified"))
    )
    (net (code "128") (name "Net-(3-B)") (class "Default")
      (node (ref "3") (pin "1") (pinfunction "B_1") (pintype "bidirectional"))
      (node (ref "R66") (pin "2") (pinfunction "2_2") (pintype "unspecified"))
    )
    (net (code "129") (name "Net-(4-B)") (class "Default")
      (node (ref "4") (pin "1") (pinfunction "B_1") (pintype "bidirectional"))
      (node (ref "R68") (pin "1") (pinfunction "1_1") (pintype "unspecified"))
    )
    (net (code "130") (name "Net-(C7-Pad1)") (class "Default")
      (node (ref "C7") (pin "1") (pinfunction "1_1") (pintype "input"))
      (node (ref "R58") (pin "2") (pinfunction "2_2") (pintype "unspecified"))
      (node (ref "R7") (pin "1") (pinfunction "1_1") (pintype "unspecified"))
      (node (ref "R8") (pin "2") (pinfunction "2_2") (pintype "unspecified"))
    )
    (net (code "131") (name "Net-(CN2-Pad1)") (class "Default")
      (node (ref "CN2") (pin "1") (pinfunction "1_1") (pintype "unspecified"))
      (node (ref "R3") (pin "1") (pinfunction "1_1") (pintype "unspecified"))
    )
    (net (code "132") (name "Net-(CN2-Pad2)") (class "Default")
      (node (ref "CN2") (pin "2") (pinfunction "2_2") (pintype "unspecified"))
      (node (ref "R35") (pin "1") (pinfunction "1_1") (pintype "unspecified"))
    )
    (net (code "133") (name "Net-(D5-K)") (class "Default")
      (node (ref "D5") (pin "1") (pinfunction "K_1") (pintype "unspecified"))
      (node (ref "U6") (pin "2") (pinfunction "TXD_2") (pintype "output"))
    )
    (net (code "134") (name "Net-(D11-A)") (class "Default")
      (node (ref "D11") (pin "1") (pinfunction "A_1") (pintype "unspecified"))
      (node (ref "D14") (pin "2") (pinfunction "K_2") (pintype "unspecified"))
      (node (ref "R51") (pin "2") (pinfunction "2_2") (pintype "unspecified"))
    )
    (net (code "135") (name "Net-(D11-K)") (class "Default")
      (node (ref "C28") (pin "1") (pinfunction "1_1") (pintype "input"))
      (node (ref "D11") (pin "2") (pinfunction "K_2") (pintype "unspecified"))
      (node (ref "D14") (pin "1") (pinfunction "A_1") (pintype "unspecified"))
      (node (ref "R141") (pin "1") (pinfunction "1_1") (pintype "unspecified"))
      (node (ref "R30") (pin "1") (pinfunction "1_1") (pintype "unspecified"))
      (node (ref "R61") (pin "2") (pinfunction "2_2") (pintype "unspecified"))
      (node (ref "U5") (pin "6") (pinfunction "INV_INB_6") (pintype "unspecified"))
    )
    (net (code "136") (name "Net-(D17-A)") (class "Default")
      (node (ref "D17") (pin "2") (pinfunction "A_2") (pintype "unspecified"))
      (node (ref "U13") (pin "1") (pinfunction "1_1") (pintype "unspecified"))
      (node (ref "U2") (pin "2") (pinfunction "2_2") (pintype "unspecified"))
    )
    (net (code "137") (name "Net-(D33-A)") (class "Default")
      (node (ref "C36") (pin "1") (pinfunction "1_1") (pintype "input"))
      (node (ref "D33") (pin "1") (pinfunction "A_1") (pintype "unspecified"))
      (node (ref "D34") (pin "2") (pinfunction "K_2") (pintype "unspecified"))
      (node (ref "R150") (pin "1") (pinfunction "1_1") (pintype "unspecified"))
      (node (ref "R152") (pin "1") (pinfunction "1_1") (pintype "unspecified"))
      (node (ref "R153") (pin "2") (pinfunction "2_2") (pintype "unspecified"))
      (node (ref "U5") (pin "2") (pinfunction "INV_INA_2") (pintype "unspecified"))
    )
    (net (code "138") (name "Net-(D33-K)") (class "Default")
      (node (ref "C36") (pin "2") (pinfunction "2_2") (pintype "input"))
      (node (ref "D33") (pin "2") (pinfunction "K_2") (pintype "unspecified"))
      (node (ref "D34") (pin "1") (pinfunction "A_1") (pintype "unspecified"))
      (node (ref "R151") (pin "1") (pinfunction "1_1") (pintype "unspecified"))
      (node (ref "R154") (pin "2") (pinfunction "2_2") (pintype "unspecified"))
      (node (ref "U5") (pin "3") (pinfunction "NON_INA_3") (pintype "unspecified"))
    )
    (net (code "139") (name "Net-(IC1-CTS)") (class "Default")
      (node (ref "C70") (pin "1") (pinfunction "1_1") (pintype "unspecified"))
      (node (ref "IC1") (pin "8") (pinfunction "CTS_8") (pintype "unspecified"))
      (node (ref "X1") (pin "1") (pinfunction "OSC1_1") (pintype "input"))
    )
    (net (code "140") (name "Net-(IC1-DSR)") (class "Default")
      (node (ref "C71") (pin "1") (pinfunction "1_1") (pintype "unspecified"))
      (node (ref "IC1") (pin "7") (pinfunction "DSR_7") (pintype "unspecified"))
      (node (ref "X1") (pin "2") (pinfunction "OSC2_2") (pintype "input"))
    )
    (net (code "141") (name "Net-(IC1-R232)") (class "Default")
      (node (ref "IC1") (pin "2") (pinfunction "R232_2") (pintype "unspecified"))
      (node (ref "R75") (pin "1") (pinfunction "1_1") (pintype "unspecified"))
    )
    (net (code "142") (name "Net-(IC1-RTS)") (class "Default")
      (node (ref "IC1") (pin "3") (pinfunction "RTS_3") (pintype "unspecified"))
      (node (ref "R74") (pin "1") (pinfunction "1_1") (pintype "unspecified"))
    )
    (net (code "143") (name "Net-(JP1-Pad1)") (class "Default")
      (node (ref "JP1") (pin "1") (pinfunction "1_1") (pintype "unspecified"))
      (node (ref "R109") (pin "2") (pinfunction "2_2") (pintype "unspecified"))
    )
    (net (code "144") (name "Net-(JP2-Pad1)") (class "Default")
      (node (ref "JP2") (pin "1") (pinfunction "1_1") (pintype "unspecified"))
      (node (ref "R62") (pin "2") (pinfunction "2_2") (pintype "unspecified"))
    )
    (net (code "145") (name "Net-(JP2-Pad3)") (class "Default")
      (node (ref "JP2") (pin "3") (pinfunction "3_3") (pintype "unspecified"))
      (node (ref "R24") (pin "1") (pinfunction "1_1") (pintype "unspecified"))
      (node (ref "R30") (pin "2") (pinfunction "2_2") (pintype "unspecified"))
    )
    (net (code "146") (name "Net-(JP6-Pad1)") (class "Default")
      (node (ref "JP6") (pin "1") (pinfunction "1_1") (pintype "unspecified"))
      (node (ref "R47") (pin "2") (pinfunction "2_2") (pintype "unspecified"))
    )
    (net (code "147") (name "Net-(JP8-Pad1)") (class "Default")
      (node (ref "JP8") (pin "1") (pinfunction "1_1") (pintype "unspecified"))
      (node (ref "R45") (pin "2") (pinfunction "2_2") (pintype "unspecified"))
    )
    (net (code "148") (name "Net-(LED4-A)") (class "Default")
      (node (ref "LED4") (pin "1") (pinfunction "A_1") (pintype "input"))
      (node (ref "R38") (pin "2") (pinfunction "2_2") (pintype "input"))
    )
    (net (code "149") (name "Net-(LED5-A)") (class "Default")
      (node (ref "LED5") (pin "1") (pinfunction "A_1") (pintype "input"))
      (node (ref "R37") (pin "2") (pinfunction "2_2") (pintype "input"))
    )
    (net (code "150") (name "Net-(Q9-G)") (class "Default")
      (node (ref "Q9") (pin "1") (pinfunction "G_1") (pintype "unspecified"))
      (node (ref "R10") (pin "1") (pinfunction "1_1") (pintype "unspecified"))
      (node (ref "R9") (pin "2") (pinfunction "2_2") (pintype "unspecified"))
    )
    (net (code "151") (name "Net-(Q10-G)") (class "Default")
      (node (ref "Q10") (pin "1") (pinfunction "G_1") (pintype "unspecified"))
      (node (ref "R11") (pin "1") (pinfunction "1_1") (pintype "unspecified"))
      (node (ref "R12") (pin "2") (pinfunction "2_2") (pintype "unspecified"))
    )
    (net (code "152") (name "Net-(Q11-G)") (class "Default")
      (node (ref "Q11") (pin "1") (pinfunction "G_1") (pintype "unspecified"))
      (node (ref "R13") (pin "1") (pinfunction "1_1") (pintype "unspecified"))
      (node (ref "R14") (pin "2") (pinfunction "2_2") (pintype "unspecified"))
    )
    (net (code "153") (name "Net-(Q12-G)") (class "Default")
      (node (ref "Q12") (pin "1") (pinfunction "G_1") (pintype "unspecified"))
      (node (ref "R15") (pin "1") (pinfunction "1_1") (pintype "unspecified"))
      (node (ref "R16") (pin "2") (pinfunction "2_2") (pintype "unspecified"))
    )
    (net (code "154") (name "Net-(Q13-G)") (class "Default")
      (node (ref "Q13") (pin "1") (pinfunction "G_1") (pintype "unspecified"))
      (node (ref "R17") (pin "1") (pinfunction "1_1") (pintype "unspecified"))
      (node (ref "R18") (pin "2") (pinfunction "2_2") (pintype "unspecified"))
    )
    (net (code "155") (name "Net-(Q14-G)") (class "Default")
      (node (ref "Q14") (pin "1") (pinfunction "G_1") (pintype "unspecified"))
      (node (ref "R19") (pin "1") (pinfunction "1_1") (pintype "unspecified"))
      (node (ref "R20") (pin "2") (pinfunction "2_2") (pintype "unspecified"))
    )
    (net (code "156") (name "Net-(Q15-G)") (class "Default")
      (node (ref "Q15") (pin "1") (pinfunction "G_1") (pintype "unspecified"))
      (node (ref "R31") (pin "1") (pinfunction "1_1") (pintype "unspecified"))
      (node (ref "R32") (pin "2") (pinfunction "2_2") (pintype "unspecified"))
    )
    (net (code "157") (name "Net-(Q16-G)") (class "Default")
      (node (ref "Q16") (pin "1") (pinfunction "G_1") (pintype "unspecified"))
      (node (ref "R33") (pin "1") (pinfunction "1_1") (pintype "unspecified"))
      (node (ref "R34") (pin "2") (pinfunction "2_2") (pintype "unspecified"))
    )
    (net (code "158") (name "Net-(Q17-G)") (class "Default")
      (node (ref "Q17") (pin "1") (pinfunction "G_1") (pintype "unspecified"))
      (node (ref "R28") (pin "1") (pinfunction "1_1") (pintype "unspecified"))
      (node (ref "R29") (pin "1") (pinfunction "1_1") (pintype "unspecified"))
    )
    (net (code "159") (name "Net-(Q18-G)") (class "Default")
      (node (ref "Q18") (pin "1") (pinfunction "G_1") (pintype "unspecified"))
      (node (ref "R87") (pin "1") (pinfunction "1_1") (pintype "unspecified"))
      (node (ref "R90") (pin "1") (pinfunction "1_1") (pintype "unspecified"))
    )
    (net (code "160") (name "Net-(Q19-G)") (class "Default")
      (node (ref "Q19") (pin "1") (pinfunction "G_1") (pintype "unspecified"))
      (node (ref "R91") (pin "1") (pinfunction "1_1") (pintype "unspecified"))
      (node (ref "R93") (pin "1") (pinfunction "1_1") (pintype "unspecified"))
    )
    (net (code "161") (name "Net-(Q20-G)") (class "Default")
      (node (ref "Q20") (pin "1") (pinfunction "G_1") (pintype "unspecified"))
      (node (ref "R103") (pin "1") (pinfunction "1_1") (pintype "unspecified"))
      (node (ref "R105") (pin "1") (pinfunction "1_1") (pintype "unspecified"))
    )
    (net (code "162") (name "Net-(R77-Pad2)") (class "Default")
      (node (ref "R77") (pin "2") (pinfunction "2_2") (pintype "unspecified"))
      (node (ref "U32") (pin "3") (pinfunction "3_3") (pintype "unspecified"))
    )
    (net (code "163") (name "Net-(R78-Pad2)") (class "Default")
      (node (ref "R78") (pin "2") (pinfunction "2_2") (pintype "unspecified"))
      (node (ref "U32") (pin "2") (pinfunction "2_2") (pintype "unspecified"))
    )
    (net (code "164") (name "Net-(SW3-B1)") (class "Default")
      (node (ref "C22") (pin "1") (pinfunction "1_1") (pintype "input"))
      (node (ref "R5") (pin "2") (pinfunction "2_2") (pintype "unspecified"))
      (node (ref "SW3") (pin "2") (pinfunction "B1_2") (pintype "input"))
    )
    (net (code "165") (name "Net-(U4-A1)") (class "Default")
      (node (ref "R100") (pin "2") (pinfunction "2_2") (pintype "unspecified"))
      (node (ref "U4") (pin "2") (pinfunction "A1_2") (pintype "unspecified"))
    )
    (net (code "166") (name "Net-(U4-A2)") (class "Default")
      (node (ref "R99") (pin "2") (pinfunction "2_2") (pintype "unspecified"))
      (node (ref "U4") (pin "3") (pinfunction "A2_3") (pintype "unspecified"))
    )
    (net (code "167") (name "Net-(U4-A3)") (class "Default")
      (node (ref "R98") (pin "2") (pinfunction "2_2") (pintype "unspecified"))
      (node (ref "U4") (pin "4") (pinfunction "A3_4") (pintype "unspecified"))
    )
    (net (code "168") (name "Net-(U4-A4)") (class "Default")
      (node (ref "R97") (pin "2") (pinfunction "2_2") (pintype "unspecified"))
      (node (ref "U4") (pin "5") (pinfunction "A4_5") (pintype "unspecified"))
    )
    (net (code "169") (name "Net-(U4-A5)") (class "Default")
      (node (ref "R96") (pin "2") (pinfunction "2_2") (pintype "unspecified"))
      (node (ref "U4") (pin "6") (pinfunction "A5_6") (pintype "unspecified"))
    )
    (net (code "170") (name "Net-(U4-A6)") (class "Default")
      (node (ref "R95") (pin "2") (pinfunction "2_2") (pintype "unspecified"))
      (node (ref "U4") (pin "7") (pinfunction "A6_7") (pintype "unspecified"))
    )
    (net (code "171") (name "Net-(U4-A7)") (class "Default")
      (node (ref "R94") (pin "2") (pinfunction "2_2") (pintype "unspecified"))
      (node (ref "U4") (pin "8") (pinfunction "A7_8") (pintype "unspecified"))
    )
    (net (code "172") (name "Net-(U4-A8)") (class "Default")
      (node (ref "R92") (pin "2") (pinfunction "2_2") (pintype "unspecified"))
      (node (ref "U4") (pin "9") (pinfunction "A8_9") (pintype "unspecified"))
    )
    (net (code "173") (name "Net-(U5-NON_INB)") (class "Default")
      (node (ref "C28") (pin "2") (pinfunction "2_2") (pintype "input"))
      (node (ref "R50") (pin "1") (pinfunction "1_1") (pintype "unspecified"))
      (node (ref "U5") (pin "5") (pinfunction "NON_INB_5") (pintype "unspecified"))
    )
    (net (code "174") (name "Net-(U7-A1)") (class "Default")
      (node (ref "R69") (pin "2") (pinfunction "2_2") (pintype "unspecified"))
      (node (ref "U7") (pin "2") (pinfunction "A1_2") (pintype "unspecified"))
    )
    (net (code "175") (name "Net-(U7-A2)") (class "Default")
      (node (ref "R70") (pin "2") (pinfunction "2_2") (pintype "unspecified"))
      (node (ref "U7") (pin "3") (pinfunction "A2_3") (pintype "unspecified"))
    )
    (net (code "176") (name "Net-(U7-A3)") (class "Default")
      (node (ref "R72") (pin "2") (pinfunction "2_2") (pintype "unspecified"))
      (node (ref "U7") (pin "4") (pinfunction "A3_4") (pintype "unspecified"))
    )
    (net (code "177") (name "Net-(U7-A4)") (class "Default")
      (node (ref "R73") (pin "2") (pinfunction "2_2") (pintype "unspecified"))
      (node (ref "U7") (pin "5") (pinfunction "A4_5") (pintype "unspecified"))
    )
    (net (code "178") (name "Net-(U7-A5)") (class "Default")
      (node (ref "R86") (pin "2") (pinfunction "2_2") (pintype "unspecified"))
      (node (ref "U7") (pin "6") (pinfunction "A5_6") (pintype "unspecified"))
    )
    (net (code "179") (name "Net-(U7-A6)") (class "Default")
      (node (ref "R114") (pin "2") (pinfunction "2_2") (pintype "unspecified"))
      (node (ref "U7") (pin "7") (pinfunction "A6_7") (pintype "unspecified"))
    )
    (net (code "180") (name "Net-(U7-A7)") (class "Default")
      (node (ref "R115") (pin "2") (pinfunction "2_2") (pintype "unspecified"))
      (node (ref "U7") (pin "8") (pinfunction "A7_8") (pintype "unspecified"))
    )
    (net (code "181") (name "Net-(U7-A8)") (class "Default")
      (node (ref "R116") (pin "2") (pinfunction "2_2") (pintype "unspecified"))
      (node (ref "U7") (pin "9") (pinfunction "A8_9") (pintype "unspecified"))
    )
    (net (code "182") (name "Net-(U9-A)") (class "Default")
      (node (ref "R123") (pin "1") (pinfunction "1_1") (pintype "unspecified"))
      (node (ref "U9") (pin "2") (pinfunction "A_2") (pintype "unspecified"))
    )
    (net (code "183") (name "Net-(U10-A)") (class "Default")
      (node (ref "R145") (pin "1") (pinfunction "1_1") (pintype "unspecified"))
      (node (ref "U10") (pin "2") (pinfunction "A_2") (pintype "unspecified"))
    )
    (net (code "184") (name "Net-(U11-A)") (class "Default")
      (node (ref "R146") (pin "1") (pinfunction "1_1") (pintype "unspecified"))
      (node (ref "U11") (pin "2") (pinfunction "A_2") (pintype "unspecified"))
    )
    (net (code "185") (name "Net-(U12-A)") (class "Default")
      (node (ref "R9") (pin "1") (pinfunction "1_1") (pintype "unspecified"))
      (node (ref "U12") (pin "2") (pinfunction "A_2") (pintype "unspecified"))
    )
    (net (code "186") (name "Net-(U14-A)") (class "Default")
      (node (ref "R113") (pin "2") (pinfunction "2_2") (pintype "unspecified"))
      (node (ref "U14") (pin "2") (pinfunction "A_2") (pintype "unspecified"))
    )
    (net (code "187") (name "Net-(U16-A)") (class "Default")
      (node (ref "R85") (pin "2") (pinfunction "2_2") (pintype "unspecified"))
      (node (ref "U16") (pin "2") (pinfunction "A_2") (pintype "unspecified"))
    )
    (net (code "188") (name "Net-(U17-A)") (class "Default")
      (node (ref "R12") (pin "1") (pinfunction "1_1") (pintype "unspecified"))
      (node (ref "U17") (pin "2") (pinfunction "A_2") (pintype "unspecified"))
    )
    (net (code "189") (name "Net-(U18-A)") (class "Default")
      (node (ref "R14") (pin "1") (pinfunction "1_1") (pintype "unspecified"))
      (node (ref "U18") (pin "2") (pinfunction "A_2") (pintype "unspecified"))
    )
    (net (code "190") (name "Net-(U19-A)") (class "Default")
      (node (ref "R16") (pin "1") (pinfunction "1_1") (pintype "unspecified"))
      (node (ref "U19") (pin "2") (pinfunction "A_2") (pintype "unspecified"))
    )
    (net (code "191") (name "Net-(U20-A)") (class "Default")
      (node (ref "R18") (pin "1") (pinfunction "1_1") (pintype "unspecified"))
      (node (ref "U20") (pin "2") (pinfunction "A_2") (pintype "unspecified"))
    )
    (net (code "192") (name "Net-(U21-A)") (class "Default")
      (node (ref "R20") (pin "1") (pinfunction "1_1") (pintype "unspecified"))
      (node (ref "U21") (pin "2") (pinfunction "A_2") (pintype "unspecified"))
    )
    (net (code "193") (name "Net-(U22-A)") (class "Default")
      (node (ref "R32") (pin "1") (pinfunction "1_1") (pintype "unspecified"))
      (node (ref "U22") (pin "2") (pinfunction "A_2") (pintype "unspecified"))
    )
    (net (code "194") (name "Net-(U23-A)") (class "Default")
      (node (ref "R34") (pin "1") (pinfunction "1_1") (pintype "unspecified"))
      (node (ref "U23") (pin "2") (pinfunction "A_2") (pintype "unspecified"))
    )
    (net (code "195") (name "Net-(U24-A)") (class "Default")
      (node (ref "R147") (pin "1") (pinfunction "1_1") (pintype "unspecified"))
      (node (ref "U24") (pin "2") (pinfunction "A_2") (pintype "unspecified"))
    )
    (net (code "196") (name "Net-(U25-A)") (class "Default")
      (node (ref "R156") (pin "1") (pinfunction "1_1") (pintype "unspecified"))
      (node (ref "U25") (pin "2") (pinfunction "A_2") (pintype "unspecified"))
    )
    (net (code "197") (name "Net-(U26-A)") (class "Default")
      (node (ref "R71") (pin "2") (pinfunction "2_2") (pintype "unspecified"))
      (node (ref "U26") (pin "2") (pinfunction "A_2") (pintype "unspecified"))
    )
    (net (code "198") (name "Net-(U27-A)") (class "Default")
      (node (ref "R158") (pin "1") (pinfunction "1_1") (pintype "unspecified"))
      (node (ref "U27") (pin "2") (pinfunction "A_2") (pintype "unspecified"))
    )
    (net (code "199") (name "Net-(U28-A)") (class "Default")
      (node (ref "R159") (pin "1") (pinfunction "1_1") (pintype "unspecified"))
      (node (ref "U28") (pin "2") (pinfunction "A_2") (pintype "unspecified"))
    )
    (net (code "200") (name "Net-(U29-A)") (class "Default")
      (node (ref "R160") (pin "1") (pinfunction "1_1") (pintype "unspecified"))
      (node (ref "U29") (pin "2") (pinfunction "A_2") (pintype "unspecified"))
    )
    (net (code "201") (name "Net-(U34-Pad1)") (class "Default")
      (node (ref "U34") (pin "1") (pinfunction "1_1") (pintype "unspecified"))
      (node (ref "U35") (pin "2") (pinfunction "2_2") (pintype "unspecified"))
    )
    (net (code "202") (name "Net-(U37-VOUT)") (class "Default")
      (node (ref "R148") (pin "2") (pinfunction "2_2") (pintype "unspecified"))
      (node (ref "U37") (pin "3") (pinfunction "VOUT_3") (pintype "unspecified"))
    )
    (net (code "203") (name "Net-(U39-FB)") (class "Default")
      (node (ref "R80") (pin "2") (pinfunction "2_2") (pintype "unspecified"))
      (node (ref "R81") (pin "1") (pinfunction "1_1") (pintype "unspecified"))
      (node (ref "U39") (pin "4") (pinfunction "FB_4") (pintype "unspecified"))
    )
    (net (code "204") (name "Net-(U39-OUT)") (class "Default")
      (node (ref "U38") (pin "1") (pinfunction "1_1") (pintype "unspecified"))
      (node (ref "U39") (pin "2") (pinfunction "OUT_2") (pintype "unspecified"))
      (node (ref "U40") (pin "1") (pinfunction "C_1") (pintype "unspecified"))
    )
    (net (code "205") (name "Net-(U41-C)") (class "Default")
      (node (ref "SW1") (pin "1") (pinfunction "1_1") (pintype "unspecified"))
      (node (ref "U41") (pin "1") (pinfunction "C_1") (pintype "unspecified"))
    )
    (net (code "206") (name "Net-(U42-A1)") (class "Default")
      (node (ref "R179") (pin "2") (pinfunction "2_2") (pintype "unspecified"))
      (node (ref "U42") (pin "2") (pinfunction "A1_2") (pintype "unspecified"))
    )
    (net (code "207") (name "Net-(U42-A2)") (class "Default")
      (node (ref "R178") (pin "2") (pinfunction "2_2") (pintype "unspecified"))
      (node (ref "U42") (pin "3") (pinfunction "A2_3") (pintype "unspecified"))
    )
    (net (code "208") (name "Net-(U42-A3)") (class "Default")
      (node (ref "R177") (pin "2") (pinfunction "2_2") (pintype "unspecified"))
      (node (ref "U42") (pin "4") (pinfunction "A3_4") (pintype "unspecified"))
    )
    (net (code "209") (name "Net-(U42-A4)") (class "Default")
      (node (ref "R176") (pin "2") (pinfunction "2_2") (pintype "unspecified"))
      (node (ref "U42") (pin "5") (pinfunction "A4_5") (pintype "unspecified"))
    )
    (net (code "210") (name "Net-(U42-A5)") (class "Default")
      (node (ref "R129") (pin "2") (pinfunction "2_2") (pintype "unspecified"))
      (node (ref "U42") (pin "6") (pinfunction "A5_6") (pintype "unspecified"))
    )
    (net (code "211") (name "Net-(U42-A6)") (class "Default")
      (node (ref "R84") (pin "2") (pinfunction "2_2") (pintype "unspecified"))
      (node (ref "U42") (pin "7") (pinfunction "A6_7") (pintype "unspecified"))
    )
    (net (code "212") (name "Net-(U42-A7)") (class "Default")
      (node (ref "R83") (pin "2") (pinfunction "2_2") (pintype "unspecified"))
      (node (ref "U42") (pin "8") (pinfunction "A7_8") (pintype "unspecified"))
    )
    (net (code "213") (name "Net-(U42-A8)") (class "Default")
      (node (ref "R82") (pin "2") (pinfunction "2_2") (pintype "unspecified"))
      (node (ref "U42") (pin "9") (pinfunction "A8_9") (pintype "unspecified"))
    )
    (net (code "214") (name "Net-(U42-Y1)") (class "Default")
      (node (ref "R124") (pin "2") (pinfunction "2_2") (pintype "unspecified"))
      (node (ref "U42") (pin "18") (pinfunction "Y1_18") (pintype "unspecified"))
    )
    (net (code "215") (name "Net-(U42-Y2)") (class "Default")
      (node (ref "R125") (pin "2") (pinfunction "2_2") (pintype "unspecified"))
      (node (ref "U42") (pin "17") (pinfunction "Y2_17") (pintype "unspecified"))
    )
    (net (code "216") (name "Net-(U42-Y3)") (class "Default")
      (node (ref "R126") (pin "2") (pinfunction "2_2") (pintype "unspecified"))
      (node (ref "U42") (pin "16") (pinfunction "Y3_16") (pintype "unspecified"))
    )
    (net (code "217") (name "Net-(U42-Y4)") (class "Default")
      (node (ref "R127") (pin "2") (pinfunction "2_2") (pintype "unspecified"))
      (node (ref "U42") (pin "15") (pinfunction "Y4_15") (pintype "unspecified"))
    )
    (net (code "218") (name "Net-(U42-Y5)") (class "Default")
      (node (ref "R128") (pin "2") (pinfunction "2_2") (pintype "unspecified"))
      (node (ref "U42") (pin "14") (pinfunction "Y5_14") (pintype "unspecified"))
    )
    (net (code "219") (name "Net-(U42-Y6)") (class "Default")
      (node (ref "R142") (pin "2") (pinfunction "2_2") (pintype "unspecified"))
      (node (ref "U42") (pin "13") (pinfunction "Y6_13") (pintype "unspecified"))
    )
    (net (code "220") (name "Net-(U42-Y7)") (class "Default")
      (node (ref "R143") (pin "2") (pinfunction "2_2") (pintype "unspecified"))
      (node (ref "U42") (pin "12") (pinfunction "Y7_12") (pintype "unspecified"))
    )
    (net (code "221") (name "Net-(U42-Y8)") (class "Default")
      (node (ref "R144") (pin "2") (pinfunction "2_2") (pintype "unspecified"))
      (node (ref "U42") (pin "11") (pinfunction "Y8_11") (pintype "unspecified"))
    )
    (net (code "222") (name "Net-(U50-K)") (class "Default")
      (node (ref "R117") (pin "1") (pinfunction "1_1") (pintype "unspecified"))
      (node (ref "U50") (pin "1") (pinfunction "K_1") (pintype "unspecified"))
    )
    (net (code "223") (name "Net-(U52-RS)") (class "Default")
      (node (ref "R121") (pin "1") (pinfunction "1_1") (pintype "unspecified"))
      (node (ref "U52") (pin "8") (pinfunction "RS_8") (pintype "unspecified"))
    )
    (net (code "224") (name "Net-(U53-VCAP_1)") (class "Default")
      (node (ref "C35") (pin "2") (pinfunction "2_2") (pintype "input"))
      (node (ref "C61") (pin "2") (pinfunction "2_2") (pintype "input"))
      (node (ref "U53") (pin "49") (pinfunction "VCAP_1_49") (pintype "unspecified"))
    )
    (net (code "225") (name "Net-(U53-VCAP_2)") (class "Default")
      (node (ref "C65") (pin "1") (pinfunction "1_1") (pintype "input"))
      (node (ref "U53") (pin "73") (pinfunction "VCAP_2_73") (pintype "unspecified"))
    )
    (net (code "226") (name "Net-(U56-AVREF)") (class "Default")
      (node (ref "U56") (pin "12") (pinfunction "AVREF_12") (pintype "unspecified"))
      (node (ref "U56") (pin "13") (pinfunction "BVREF_13") (pintype "unspecified"))
      (node (ref "U57") (pin "2") (pinfunction "2_2") (pintype "input"))
    )
    (net (code "227") (name "Net-(U56-CP1)") (class "Default")
      (node (ref "C46") (pin "1") (pinfunction "1_1") (pintype "input"))
      (node (ref "U56") (pin "1") (pinfunction "CP1_1") (pintype "unspecified"))
    )
    (net (code "228") (name "Net-(U56-CP2)") (class "Default")
      (node (ref "C46") (pin "2") (pinfunction "2_2") (pintype "input"))
      (node (ref "U56") (pin "2") (pinfunction "CP2_2") (pintype "unspecified"))
    )
    (net (code "229") (name "Net-(U56-ISENA)") (class "Default")
      (node (ref "R133") (pin "2") (pinfunction "2_2") (pintype "unspecified"))
      (node (ref "U56") (pin "6") (pinfunction "ISENA_6") (pintype "unspecified"))
    )
    (net (code "230") (name "Net-(U56-ISENB)") (class "Default")
      (node (ref "R132") (pin "2") (pinfunction "2_2") (pintype "unspecified"))
      (node (ref "U56") (pin "9") (pinfunction "ISENB_9") (pintype "unspecified"))
    )
    (net (code "231") (name "Net-(U56-VCP)") (class "Default")
      (node (ref "C48") (pin "1") (pinfunction "1_1") (pintype "input"))
      (node (ref "U56") (pin "3") (pinfunction "VCP_3") (pintype "unspecified"))
    )
    (net (code "232") (name "Net-(U62-C)") (class "Default")
      (node (ref "U62") (pin "1") (pinfunction "C_1") (pintype "unspecified"))
      (node (ref "U63") (pin "2") (pinfunction "OUT_2") (pintype "unspecified"))
      (node (ref "U64") (pin "1") (pinfunction "1_1") (pintype "unspecified"))
    )
    (net (code "233") (name "Net-(U63-FB)") (class "Default")
      (node (ref "R76") (pin "1") (pinfunction "1_1") (pintype "unspecified"))
      (node (ref "R79") (pin "2") (pinfunction "2_2") (pintype "unspecified"))
      (node (ref "U63") (pin "4") (pinfunction "FB_4") (pintype "unspecified"))
    )
    (net (code "234") (name "Net-(USB1-D+)") (class "Default")
      (node (ref "R119") (pin "1") (pinfunction "1_1") (pintype "unspecified"))
      (node (ref "USB1") (pin "3") (pinfunction "D+_3") (pintype "input"))
    )
    (net (code "235") (name "Net-(USB1-D-)") (class "Default")
      (node (ref "R118") (pin "1") (pinfunction "1_1") (pintype "unspecified"))
      (node (ref "USB1") (pin "2") (pinfunction "D-_2") (pintype "input"))
    )
    (net (code "236") (name "O2-CPU-A8") (class "Default")
      (node (ref "C10") (pin "1") (pinfunction "1_1") (pintype "input"))
      (node (ref "D19") (pin "7") (pinfunction "IN_7") (pintype "unspecified"))
      (node (ref "R169") (pin "1") (pinfunction "1_1") (pintype "unspecified"))
      (node (ref "R21") (pin "1") (pinfunction "1_1") (pintype "unspecified"))
      (node (ref "U53") (pin "35") (pinfunction "PB0_35") (pintype "unspecified"))
    )
    (net (code "237") (name "OSC32_IN") (class "Default")
      (node (ref "C40") (pin "2") (pinfunction "2_2") (pintype "input"))
      (node (ref "U53") (pin "8") (pinfunction "PC14_8") (pintype "unspecified"))
      (node (ref "X3") (pin "2") (pinfunction "OSC2_2") (pintype "input"))
    )
    (net (code "238") (name "OSC32_OUT") (class "Default")
      (node (ref "C39") (pin "2") (pinfunction "2_2") (pintype "input"))
      (node (ref "U53") (pin "9") (pinfunction "PC15_9") (pintype "unspecified"))
      (node (ref "X3") (pin "1") (pinfunction "OSC1_1") (pintype "input"))
    )
    (net (code "239") (name "OSC_IN") (class "Default")
      (node (ref "C66") (pin "2") (pinfunction "2_2") (pintype "input"))
      (node (ref "R122") (pin "2") (pinfunction "2_2") (pintype "unspecified"))
      (node (ref "U53") (pin "12") (pinfunction "PH0_12") (pintype "unspecified"))
      (node (ref "X2") (pin "2") (pinfunction "OSC2_2") (pintype "input"))
    )
    (net (code "240") (name "OSC_OUT") (class "Default")
      (node (ref "C38") (pin "2") (pinfunction "2_2") (pintype "input"))
      (node (ref "R122") (pin "1") (pinfunction "1_1") (pintype "unspecified"))
      (node (ref "U53") (pin "13") (pinfunction "PH1_13") (pintype "unspecified"))
      (node (ref "X2") (pin "1") (pinfunction "OSC1_1") (pintype "input"))
    )
    (net (code "241") (name "RESET") (class "Default")
      (node (ref "3") (pin "2") (pinfunction "C_2") (pintype "bidirectional"))
      (node (ref "R40") (pin "1") (pinfunction "1_1") (pintype "unspecified"))
      (node (ref "R5") (pin "1") (pinfunction "1_1") (pintype "unspecified"))
      (node (ref "U53") (pin "14") (pinfunction "NRST_14") (pintype "unspecified"))
    )
    (net (code "242") (name "RX2") (class "Default")
      (node (ref "R35") (pin "2") (pinfunction "2_2") (pintype "unspecified"))
      (node (ref "U53") (pin "87") (pinfunction "PD6_87") (pintype "unspecified"))
    )
    (net (code "243") (name "RXCAN") (class "Default")
      (node (ref "U52") (pin "4") (pinfunction "RXD_4") (pintype "unspecified"))
      (node (ref "U53") (pin "81") (pinfunction "PD0_81") (pintype "unspecified"))
    )
    (net (code "244") (name "RXD1") (class "Default")
      (node (ref "D5") (pin "2") (pinfunction "A_2") (pintype "unspecified"))
      (node (ref "LED4") (pin "2") (pinfunction "C_2") (pintype "input"))
      (node (ref "R75") (pin "2") (pinfunction "2_2") (pintype "unspecified"))
      (node (ref "U53") (pin "69") (pinfunction "PA10_69") (pintype "unspecified"))
    )
    (net (code "245") (name "SD CS") (class "Default")
      (node (ref "U53") (pin "83") (pinfunction "PD2_83") (pintype "unspecified"))
    )
    (net (code "246") (name "SPI3 CLK") (class "Default")
      (node (ref "U53") (pin "78") (pinfunction "PC10_78") (pintype "unspecified"))
    )
    (net (code "247") (name "SPI3 MISO") (class "Default")
      (node (ref "U53") (pin "79") (pinfunction "PC11_79") (pintype "unspecified"))
    )
    (net (code "248") (name "SPI3 MOSI") (class "Default")
      (node (ref "U53") (pin "80") (pinfunction "PC12_80") (pintype "unspecified"))
    )
    (net (code "249") (name "STP-DIR-CPU-D16") (class "Default")
      (node (ref "U53") (pin "47") (pinfunction "PB10_47") (pintype "unspecified"))
      (node (ref "U56") (pin "20") (pinfunction "DIR_20") (pintype "unspecified"))
    )
    (net (code "250") (name "STP-E-CPU-D24") (class "Default")
      (node (ref "U53") (pin "77") (pinfunction "PA15_77") (pintype "unspecified"))
      (node (ref "U56") (pin "21") (pinfunction "NENBL_21") (pintype "unspecified"))
    )
    (net (code "251") (name "STP-STEP-CPU-D17") (class "Default")
      (node (ref "U53") (pin "48") (pinfunction "PB11_48") (pintype "unspecified"))
      (node (ref "U56") (pin "22") (pinfunction "STEP_22") (pintype "unspecified"))
    )
    (net (code "252") (name "SWCLK") (class "Default")
      (node (ref "R168") (pin "2") (pinfunction "2_2") (pintype "unspecified"))
      (node (ref "U36") (pin "2") (pinfunction "2_2") (pintype "unspecified"))
      (node (ref "U53") (pin "76") (pinfunction "PA14_76") (pintype "unspecified"))
    )
    (net (code "253") (name "SWDIO") (class "Default")
      (node (ref "R167") (pin "1") (pinfunction "1_1") (pintype "unspecified"))
      (node (ref "U36") (pin "3") (pinfunction "3_3") (pintype "unspecified"))
      (node (ref "U53") (pin "72") (pinfunction "PA13_72") (pintype "unspecified"))
    )
    (net (code "254") (name "Steper+3.3V") (class "Default")
      (node (ref "C51") (pin "1") (pinfunction "1_1") (pintype "input"))
      (node (ref "U56") (pin "15") (pinfunction "V3P3OUT_15") (pintype "unspecified"))
      (node (ref "U56") (pin "16") (pinfunction "nRESET_16") (pintype "unspecified"))
      (node (ref "U56") (pin "17") (pinfunction "nSLEEP_17") (pintype "unspecified"))
      (node (ref "U57") (pin "1") (pinfunction "1_1") (pintype "input"))
    )
    (net (code "255") (name "TACHO-CPU-D49") (class "Default")
      (node (ref "R115") (pin "1") (pinfunction "1_1") (pintype "unspecified"))
      (node (ref "R65") (pin "2") (pinfunction "2_2") (pintype "unspecified"))
      (node (ref "U53") (pin "39") (pinfunction "PE8_39") (pintype "unspecified"))
    )
    (net (code "256") (name "TPS-CPU-A2") (class "Default")
      (node (ref "C2") (pin "1") (pinfunction "1_1") (pintype "input"))
      (node (ref "D19") (pin "10") (pinfunction "IN_10") (pintype "unspecified"))
      (node (ref "R138") (pin "1") (pinfunction "1_1") (pintype "unspecified"))
      (node (ref "R6") (pin "1") (pinfunction "1_1") (pintype "unspecified"))
      (node (ref "U53") (pin "25") (pinfunction "PA2_25") (pintype "unspecified"))
    )
    (net (code "257") (name "TXCAN") (class "Default")
      (node (ref "U52") (pin "1") (pinfunction "TXD_1") (pintype "unspecified"))
      (node (ref "U53") (pin "82") (pinfunction "PD1_82") (pintype "unspecified"))
    )
    (net (code "258") (name "TXD1") (class "Default")
      (node (ref "LED5") (pin "2") (pinfunction "C_2") (pintype "input"))
      (node (ref "R74") (pin "2") (pinfunction "2_2") (pintype "unspecified"))
      (node (ref "U53") (pin "68") (pinfunction "PA9_68") (pintype "unspecified"))
      (node (ref "U6") (pin "1") (pinfunction "RXD_1") (pintype "input"))
    )
    (net (code "259") (name "TXD2") (class "Default")
      (node (ref "R3") (pin "2") (pinfunction "2_2") (pintype "unspecified"))
      (node (ref "U53") (pin "86") (pinfunction "PD5_86") (pintype "unspecified"))
    )
    (net (code "260") (name "VREF+") (class "Default")
      (node (ref "C11") (pin "1") (pinfunction "1_1") (pintype "input"))
      (node (ref "C26") (pin "1") (pinfunction "1_1") (pintype "input"))
      (node (ref "R130") (pin "1") (pinfunction "1_1") (pintype "unspecified"))
      (node (ref "R131") (pin "2") (pinfunction "2_2") (pintype "unspecified"))
      (node (ref "U53") (pin "21") (pinfunction "VREF+_21") (pintype "unspecified"))
    )
    (net (code "261") (name "VSS-CPU-D3") (class "Default")
      (node (ref "D19") (pin "14") (pinfunction "IN_14") (pintype "unspecified"))
      (node (ref "D23") (pin "1") (pinfunction "K_1") (pintype "unspecified"))
      (node (ref "R26") (pin "2") (pinfunction "2_2") (pintype "unspecified"))
      (node (ref "U53") (pin "92") (pinfunction "PB6_92") (pintype "unspecified"))
    )
    (net (code "262") (name "VVT-CPU-D4") (class "Default")
      (node (ref "R57") (pin "2") (pinfunction "2_2") (pintype "unspecified"))
      (node (ref "R70") (pin "1") (pinfunction "1_1") (pintype "unspecified"))
      (node (ref "U53") (pin "58") (pinfunction "PD11_58") (pintype "unspecified"))
    )
    (net (code "263") (name "VVT2-CPU-D28") (class "Default")
      (node (ref "R41") (pin "2") (pinfunction "2_2") (pintype "unspecified"))
      (node (ref "R72") (pin "1") (pinfunction "1_1") (pintype "unspecified"))
      (node (ref "U53") (pin "63") (pinfunction "PC6_63") (pintype "unspecified"))
    )
    (net (code "264") (name "unconnected-(CN4-Pad2)") (class "Default")
      (node (ref "CN4") (pin "2") (pinfunction "2_2") (pintype "unspecified+no_connect"))
    )
    (net (code "265") (name "unconnected-(D19-IN-Pad3)") (class "Default")
      (node (ref "D19") (pin "3") (pinfunction "IN_3") (pintype "unspecified+no_connect"))
    )
    (net (code "266") (name "unconnected-(D19-IN-Pad4)") (class "Default")
      (node (ref "D19") (pin "4") (pinfunction "IN_4") (pintype "unspecified+no_connect"))
    )
    (net (code "267") (name "unconnected-(D19-IN-Pad13)") (class "Default")
      (node (ref "D19") (pin "13") (pinfunction "IN_13") (pintype "unspecified+no_connect"))
    )
    (net (code "268") (name "unconnected-(IC1-D+-Pad12)") (class "Default")
      (node (ref "IC1") (pin "12") (pinfunction "D+_12") (pintype "unspecified+no_connect"))
    )
    (net (code "269") (name "unconnected-(IC1-D--Pad11)") (class "Default")
      (node (ref "IC1") (pin "11") (pinfunction "D-_11") (pintype "unspecified+no_connect"))
    )
    (net (code "270") (name "unconnected-(IC1-TXD-Pad15)") (class "Default")
      (node (ref "IC1") (pin "15") (pinfunction "TXD_15") (pintype "unspecified+no_connect"))
    )
    (net (code "271") (name "unconnected-(IC1-XI-Pad10)") (class "Default")
      (node (ref "IC1") (pin "10") (pinfunction "XI_10") (pintype "unspecified+no_connect"))
    )
    (net (code "272") (name "unconnected-(IC1-XO-Pad9)") (class "Default")
      (node (ref "IC1") (pin "9") (pinfunction "XO_9") (pintype "unspecified+no_connect"))
    )
    (net (code "273") (name "unconnected-(MICROSD1-CardDetect-Pad9)") (class "Default")
      (node (ref "MICROSD1") (pin "9") (pinfunction "CardDetect_9") (pintype "unspecified+no_connect"))
    )
    (net (code "274") (name "unconnected-(MICROSD1-DAT1-Pad8)") (class "Default")
      (node (ref "MICROSD1") (pin "8") (pinfunction "DAT1_8") (pintype "unspecified+no_connect"))
    )
    (net (code "275") (name "unconnected-(MICROSD1-DAT2-Pad1)") (class "Default")
      (node (ref "MICROSD1") (pin "1") (pinfunction "DAT2_1") (pintype "unspecified+no_connect"))
    )
    (net (code "276") (name "unconnected-(U37-GND{slash}CLK-Pad8)") (class "Default")
      (node (ref "U37") (pin "8") (pinfunction "GND/CLK_8") (pintype "unspecified+no_connect"))
    )
    (net (code "277") (name "unconnected-(U37-GND{slash}UP1-Pad5)") (class "Default")
      (node (ref "U37") (pin "5") (pinfunction "GND/UP1_5") (pintype "unspecified+no_connect"))
    )
    (net (code "278") (name "unconnected-(U37-GND{slash}UP2-Pad4)") (class "Default")
      (node (ref "U37") (pin "4") (pinfunction "GND/UP2_4") (pintype "unspecified+no_connect"))
    )
    (net (code "279") (name "unconnected-(U37-NC-Pad6)") (class "Default")
      (node (ref "U37") (pin "6") (pinfunction "NC_6") (pintype "unspecified+no_connect"))
    )
    (net (code "280") (name "unconnected-(U37-NC-Pad7)") (class "Default")
      (node (ref "U37") (pin "7") (pinfunction "NC_7") (pintype "unspecified+no_connect"))
    )
    (net (code "281") (name "unconnected-(U52-VREF-Pad5)") (class "Default")
      (node (ref "U52") (pin "5") (pinfunction "VREF_5") (pintype "unspecified+no_connect"))
    )
    (net (code "282") (name "unconnected-(U53-PA6-Pad31)") (class "Default")
      (node (ref "U53") (pin "31") (pinfunction "PA6_31") (pintype "unspecified+no_connect"))
    )
    (net (code "283") (name "unconnected-(U53-PA7-Pad32)") (class "Default")
      (node (ref "U53") (pin "32") (pinfunction "PA7_32") (pintype "unspecified+no_connect"))
    )
    (net (code "284") (name "unconnected-(U53-PB1-Pad36)") (class "Default")
      (node (ref "U53") (pin "36") (pinfunction "PB1_36") (pintype "unspecified+no_connect"))
    )
    (net (code "285") (name "unconnected-(U53-PB3-Pad89)") (class "Default")
      (node (ref "U53") (pin "89") (pinfunction "PB3_89") (pintype "unspecified+no_connect"))
    )
    (net (code "286") (name "unconnected-(U53-PB4-Pad90)") (class "Default")
      (node (ref "U53") (pin "90") (pinfunction "PB4_90") (pintype "unspecified+no_connect"))
    )
    (net (code "287") (name "unconnected-(U53-PB5-Pad91)") (class "Default")
      (node (ref "U53") (pin "91") (pinfunction "PB5_91") (pintype "unspecified+no_connect"))
    )
    (net (code "288") (name "unconnected-(U53-PC3-Pad18)") (class "Default")
      (node (ref "U53") (pin "18") (pinfunction "PC3_18") (pintype "unspecified+no_connect"))
    )
    (net (code "289") (name "unconnected-(U53-PC4-Pad33)") (class "Default")
      (node (ref "U53") (pin "33") (pinfunction "PC4_33") (pintype "unspecified+no_connect"))
    )
    (net (code "290") (name "unconnected-(U53-PC5-Pad34)") (class "Default")
      (node (ref "U53") (pin "34") (pinfunction "PC5_34") (pintype "unspecified+no_connect"))
    )
    (net (code "291") (name "unconnected-(U53-PC7-Pad64)") (class "Default")
      (node (ref "U53") (pin "64") (pinfunction "PC7_64") (pintype "unspecified+no_connect"))
    )
    (net (code "292") (name "unconnected-(U53-PD12-Pad59)") (class "Default")
      (node (ref "U53") (pin "59") (pinfunction "PD12_59") (pintype "unspecified+no_connect"))
    )
    (net (code "293") (name "unconnected-(U53-PE12-Pad43)") (class "Default")
      (node (ref "U53") (pin "43") (pinfunction "PE12_43") (pintype "unspecified+no_connect"))
    )
    (net (code "294") (name "unconnected-(U53-PE14-Pad45)") (class "Default")
      (node (ref "U53") (pin "45") (pinfunction "PE14_45") (pintype "unspecified+no_connect"))
    )
    (net (code "295") (name "unconnected-(U53-PE15-Pad46)") (class "Default")
      (node (ref "U53") (pin "46") (pinfunction "PE15_46") (pintype "unspecified+no_connect"))
    )
    (net (code "296") (name "unconnected-(U56-DECAY-Pad19)") (class "Default")
      (node (ref "U56") (pin "19") (pinfunction "DECAY_19") (pintype "unspecified+no_connect"))
    )
    (net (code "297") (name "unconnected-(U56-NC-Pad23)") (class "Default")
      (node (ref "U56") (pin "23") (pinfunction "NC_23") (pintype "unspecified+no_connect"))
    )
    (net (code "298") (name "unconnected-(U56-nFAULT-Pad18)") (class "Default")
      (node (ref "U56") (pin "18") (pinfunction "nFAULT_18") (pintype "unspecified+no_connect"))
    )
    (net (code "299") (name "unconnected-(U56-nHOME-Pad27)") (class "Default")
      (node (ref "U56") (pin "27") (pinfunction "nHOME_27") (pintype "unspecified+no_connect"))
    )
    (net (code "300") (name "unconnected-(X3-Pad3)") (class "Default")
      (node (ref "X3") (pin "3") (pinfunction "3_3") (pintype "input+no_connect"))
    )
  )
)
